# LEDPanel.net
KiCad netlist of a schematic drawn in EAGLE
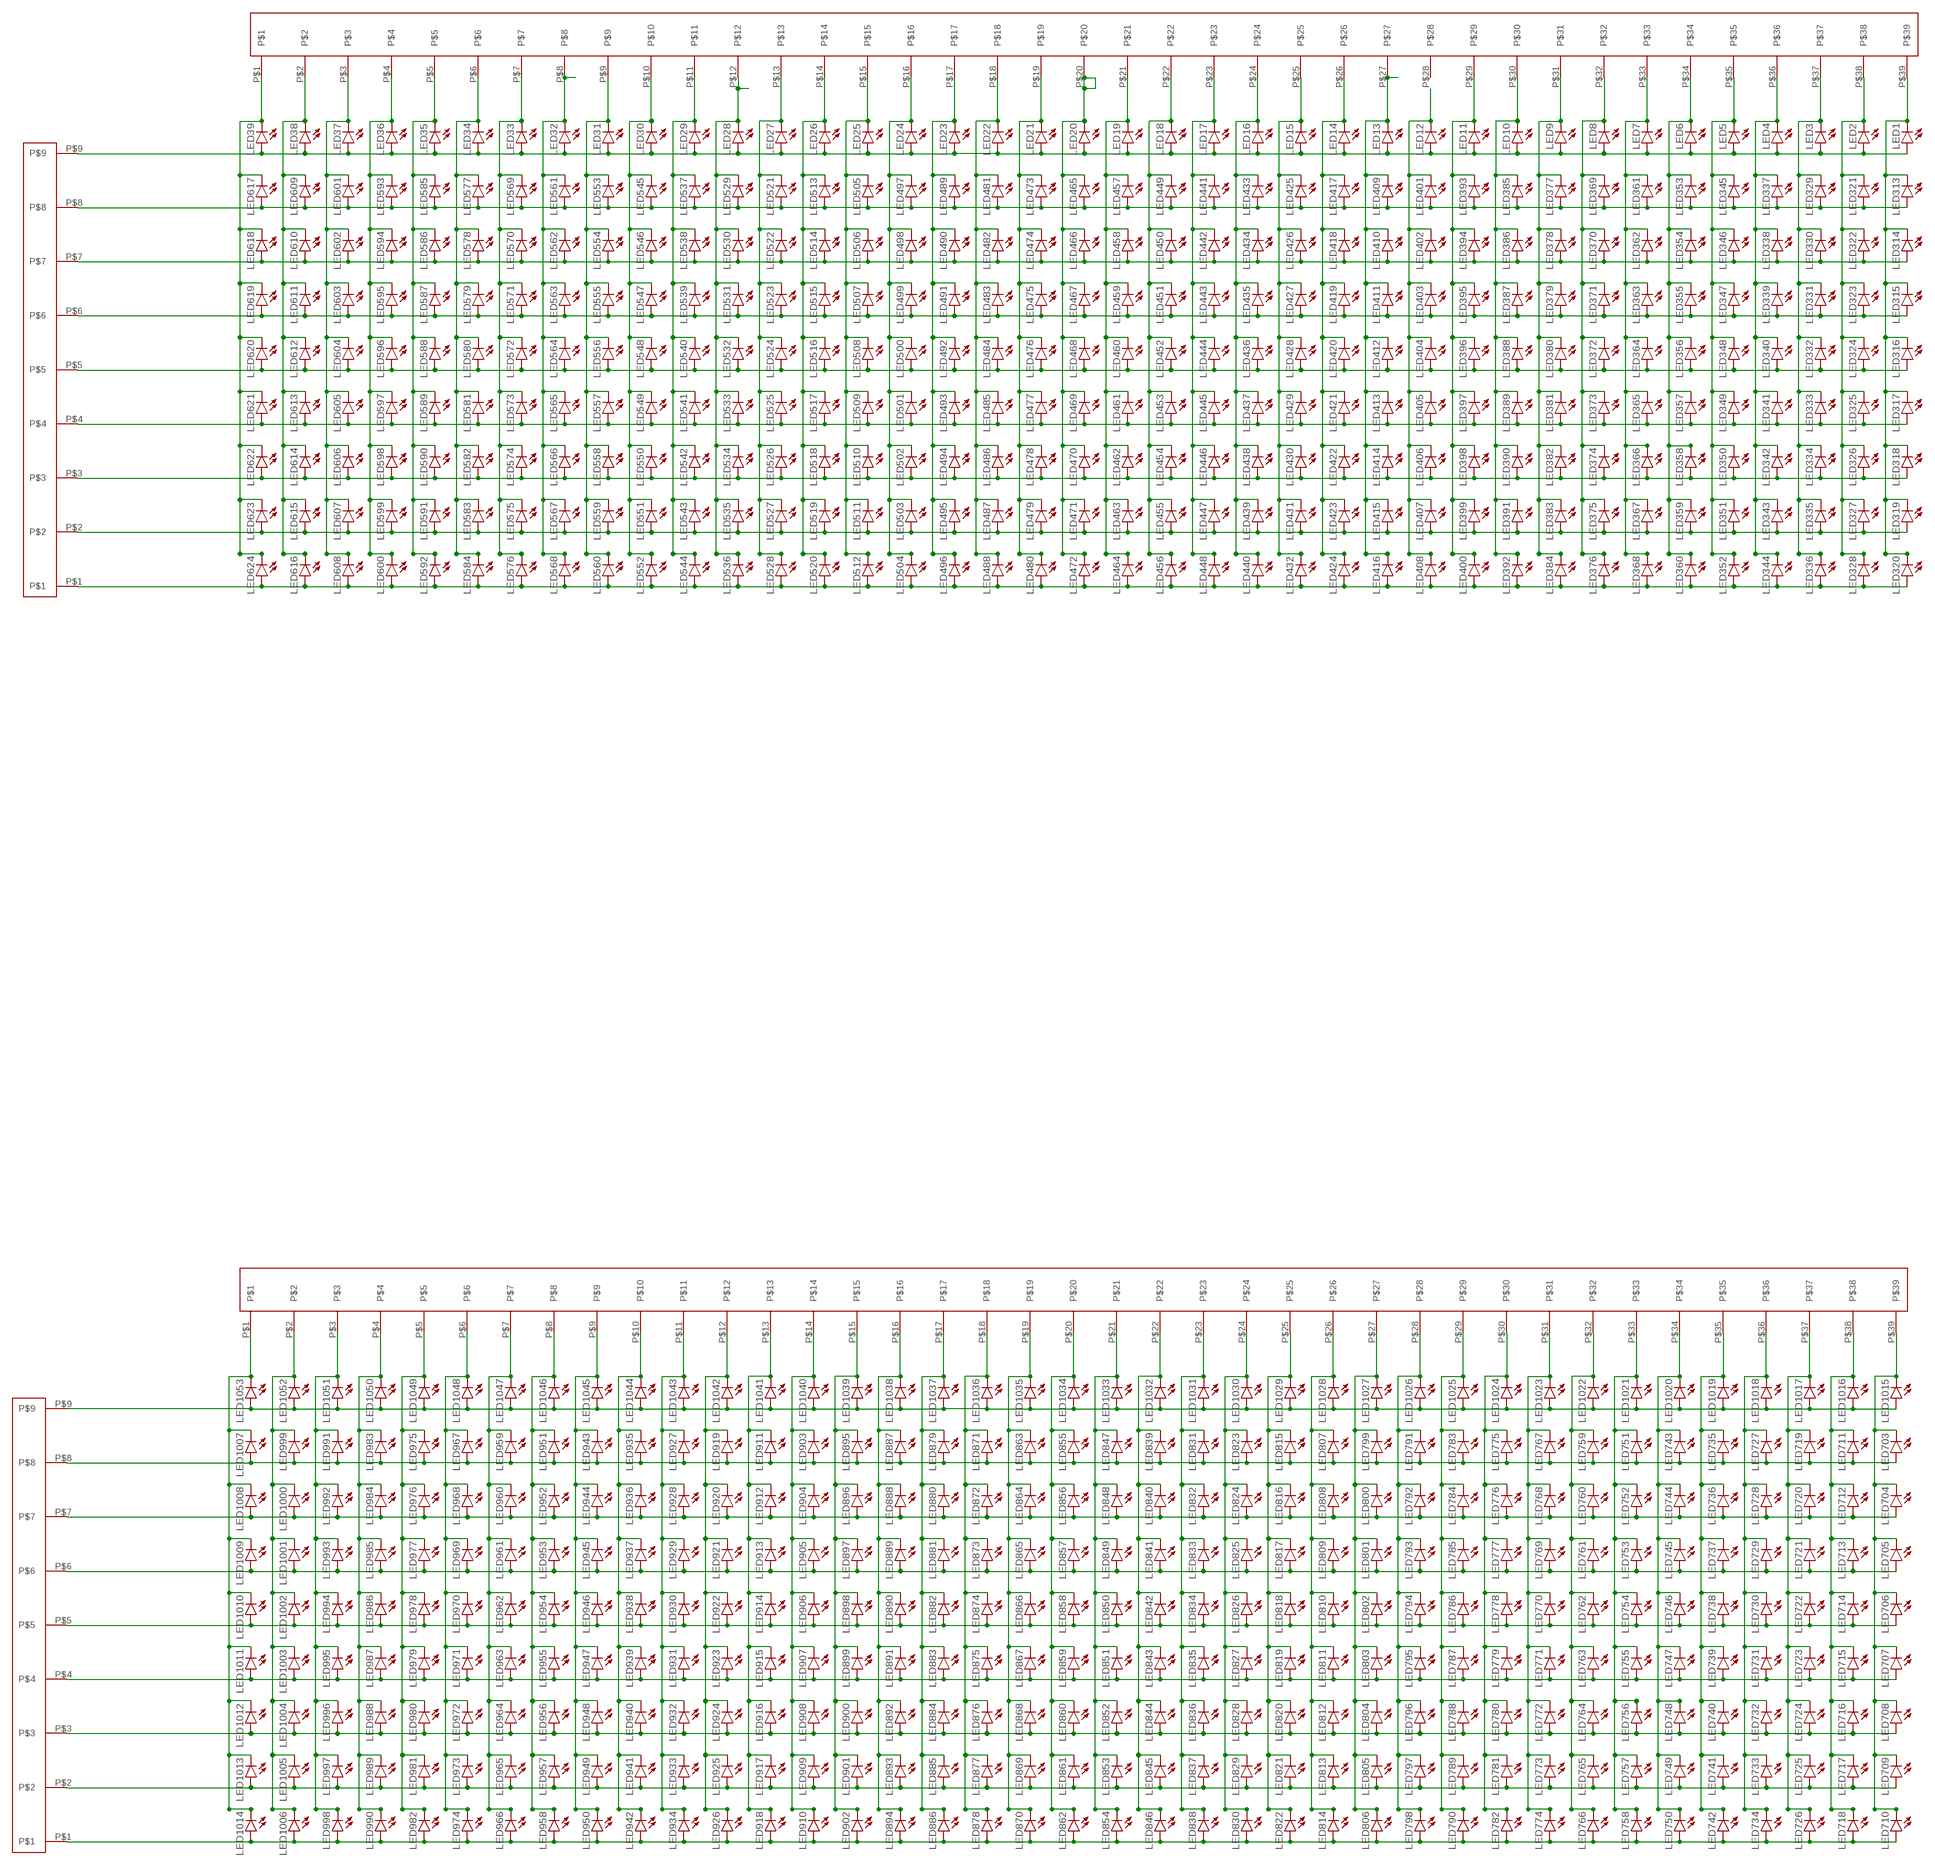
[diagram p0: schematic, sheet 1]

(export (version "E")
  (design (tool "Eeschema 10.0.6"))
  (components
    (comp (ref "LED1")
      (value "LED3MM")
      (footprint "eagle-import:LED_3MM")
      (libsource (lib "eagle-import") (part "LED3MM"))
    )
    (comp (ref "LED2")
      (value "LED3MM")
      (footprint "eagle-import:LED_3MM")
      (libsource (lib "eagle-import") (part "LED3MM"))
    )
    (comp (ref "LED3")
      (value "LED3MM")
      (footprint "eagle-import:LED_3MM")
      (libsource (lib "eagle-import") (part "LED3MM"))
    )
    (comp (ref "LED4")
      (value "LED3MM")
      (footprint "eagle-import:LED_3MM")
      (libsource (lib "eagle-import") (part "LED3MM"))
    )
    (comp (ref "LED5")
      (value "LED3MM")
      (footprint "eagle-import:LED_3MM")
      (libsource (lib "eagle-import") (part "LED3MM"))
    )
    (comp (ref "LED6")
      (value "LED3MM")
      (footprint "eagle-import:LED_3MM")
      (libsource (lib "eagle-import") (part "LED3MM"))
    )
    (comp (ref "LED7")
      (value "LED3MM")
      (footprint "eagle-import:LED_3MM")
      (libsource (lib "eagle-import") (part "LED3MM"))
    )
    (comp (ref "LED8")
      (value "LED3MM")
      (footprint "eagle-import:LED_3MM")
      (libsource (lib "eagle-import") (part "LED3MM"))
    )
    (comp (ref "LED9")
      (value "LED3MM")
      (footprint "eagle-import:LED_3MM")
      (libsource (lib "eagle-import") (part "LED3MM"))
    )
    (comp (ref "LED10")
      (value "LED3MM")
      (footprint "eagle-import:LED_3MM")
      (libsource (lib "eagle-import") (part "LED3MM"))
    )
    (comp (ref "LED11")
      (value "LED3MM")
      (footprint "eagle-import:LED_3MM")
      (libsource (lib "eagle-import") (part "LED3MM"))
    )
    (comp (ref "LED12")
      (value "LED3MM")
      (footprint "eagle-import:LED_3MM")
      (libsource (lib "eagle-import") (part "LED3MM"))
    )
    (comp (ref "LED13")
      (value "LED3MM")
      (footprint "eagle-import:LED_3MM")
      (libsource (lib "eagle-import") (part "LED3MM"))
    )
    (comp (ref "LED14")
      (value "LED3MM")
      (footprint "eagle-import:LED_3MM")
      (libsource (lib "eagle-import") (part "LED3MM"))
    )
    (comp (ref "LED15")
      (value "LED3MM")
      (footprint "eagle-import:LED_3MM")
      (libsource (lib "eagle-import") (part "LED3MM"))
    )
    (comp (ref "LED16")
      (value "LED3MM")
      (footprint "eagle-import:LED_3MM")
      (libsource (lib "eagle-import") (part "LED3MM"))
    )
    (comp (ref "LED17")
      (value "LED3MM")
      (footprint "eagle-import:LED_3MM")
      (libsource (lib "eagle-import") (part "LED3MM"))
    )
    (comp (ref "LED18")
      (value "LED3MM")
      (footprint "eagle-import:LED_3MM")
      (libsource (lib "eagle-import") (part "LED3MM"))
    )
    (comp (ref "LED19")
      (value "LED3MM")
      (footprint "eagle-import:LED_3MM")
      (libsource (lib "eagle-import") (part "LED3MM"))
    )
    (comp (ref "LED20")
      (value "LED3MM")
      (footprint "eagle-import:LED_3MM")
      (libsource (lib "eagle-import") (part "LED3MM"))
    )
    (comp (ref "LED21")
      (value "LED3MM")
      (footprint "eagle-import:LED_3MM")
      (libsource (lib "eagle-import") (part "LED3MM"))
    )
    (comp (ref "LED22")
      (value "LED3MM")
      (footprint "eagle-import:LED_3MM")
      (libsource (lib "eagle-import") (part "LED3MM"))
    )
    (comp (ref "LED23")
      (value "LED3MM")
      (footprint "eagle-import:LED_3MM")
      (libsource (lib "eagle-import") (part "LED3MM"))
    )
    (comp (ref "LED24")
      (value "LED3MM")
      (footprint "eagle-import:LED_3MM")
      (libsource (lib "eagle-import") (part "LED3MM"))
    )
    (comp (ref "LED25")
      (value "LED3MM")
      (footprint "eagle-import:LED_3MM")
      (libsource (lib "eagle-import") (part "LED3MM"))
    )
    (comp (ref "LED26")
      (value "LED3MM")
      (footprint "eagle-import:LED_3MM")
      (libsource (lib "eagle-import") (part "LED3MM"))
    )
    (comp (ref "LED27")
      (value "LED3MM")
      (footprint "eagle-import:LED_3MM")
      (libsource (lib "eagle-import") (part "LED3MM"))
    )
    (comp (ref "LED28")
      (value "LED3MM")
      (footprint "eagle-import:LED_3MM")
      (libsource (lib "eagle-import") (part "LED3MM"))
    )
    (comp (ref "LED29")
      (value "LED3MM")
      (footprint "eagle-import:LED_3MM")
      (libsource (lib "eagle-import") (part "LED3MM"))
    )
    (comp (ref "LED30")
      (value "LED3MM")
      (footprint "eagle-import:LED_3MM")
      (libsource (lib "eagle-import") (part "LED3MM"))
    )
    (comp (ref "LED31")
      (value "LED3MM")
      (footprint "eagle-import:LED_3MM")
      (libsource (lib "eagle-import") (part "LED3MM"))
    )
    (comp (ref "LED32")
      (value "LED3MM")
      (footprint "eagle-import:LED_3MM")
      (libsource (lib "eagle-import") (part "LED3MM"))
    )
    (comp (ref "LED33")
      (value "LED3MM")
      (footprint "eagle-import:LED_3MM")
      (libsource (lib "eagle-import") (part "LED3MM"))
    )
    (comp (ref "LED34")
      (value "LED3MM")
      (footprint "eagle-import:LED_3MM")
      (libsource (lib "eagle-import") (part "LED3MM"))
    )
    (comp (ref "LED35")
      (value "LED3MM")
      (footprint "eagle-import:LED_3MM")
      (libsource (lib "eagle-import") (part "LED3MM"))
    )
    (comp (ref "LED36")
      (value "LED3MM")
      (footprint "eagle-import:LED_3MM")
      (libsource (lib "eagle-import") (part "LED3MM"))
    )
    (comp (ref "LED37")
      (value "LED3MM")
      (footprint "eagle-import:LED_3MM")
      (libsource (lib "eagle-import") (part "LED3MM"))
    )
    (comp (ref "LED38")
      (value "LED3MM")
      (footprint "eagle-import:LED_3MM")
      (libsource (lib "eagle-import") (part "LED3MM"))
    )
    (comp (ref "LED39")
      (value "LED3MM")
      (footprint "eagle-import:LED_3MM")
      (libsource (lib "eagle-import") (part "LED3MM"))
    )
    (comp (ref "LED313")
      (value "LED3MM")
      (footprint "eagle-import:LED_3MM")
      (libsource (lib "eagle-import") (part "LED3MM"))
    )
    (comp (ref "LED314")
      (value "LED3MM")
      (footprint "eagle-import:LED_3MM")
      (libsource (lib "eagle-import") (part "LED3MM"))
    )
    (comp (ref "LED315")
      (value "LED3MM")
      (footprint "eagle-import:LED_3MM")
      (libsource (lib "eagle-import") (part "LED3MM"))
    )
    (comp (ref "LED316")
      (value "LED3MM")
      (footprint "eagle-import:LED_3MM")
      (libsource (lib "eagle-import") (part "LED3MM"))
    )
    (comp (ref "LED317")
      (value "LED3MM")
      (footprint "eagle-import:LED_3MM")
      (libsource (lib "eagle-import") (part "LED3MM"))
    )
    (comp (ref "LED318")
      (value "LED3MM")
      (footprint "eagle-import:LED_3MM")
      (libsource (lib "eagle-import") (part "LED3MM"))
    )
    (comp (ref "LED319")
      (value "LED3MM")
      (footprint "eagle-import:LED_3MM")
      (libsource (lib "eagle-import") (part "LED3MM"))
    )
    (comp (ref "LED320")
      (value "LED3MM")
      (footprint "eagle-import:LED_3MM")
      (libsource (lib "eagle-import") (part "LED3MM"))
    )
    (comp (ref "LED321")
      (value "LED3MM")
      (footprint "eagle-import:LED_3MM")
      (libsource (lib "eagle-import") (part "LED3MM"))
    )
    (comp (ref "LED322")
      (value "LED3MM")
      (footprint "eagle-import:LED_3MM")
      (libsource (lib "eagle-import") (part "LED3MM"))
    )
    (comp (ref "LED323")
      (value "LED3MM")
      (footprint "eagle-import:LED_3MM")
      (libsource (lib "eagle-import") (part "LED3MM"))
    )
    (comp (ref "LED324")
      (value "LED3MM")
      (footprint "eagle-import:LED_3MM")
      (libsource (lib "eagle-import") (part "LED3MM"))
    )
    (comp (ref "LED325")
      (value "LED3MM")
      (footprint "eagle-import:LED_3MM")
      (libsource (lib "eagle-import") (part "LED3MM"))
    )
    (comp (ref "LED326")
      (value "LED3MM")
      (footprint "eagle-import:LED_3MM")
      (libsource (lib "eagle-import") (part "LED3MM"))
    )
    (comp (ref "LED327")
      (value "LED3MM")
      (footprint "eagle-import:LED_3MM")
      (libsource (lib "eagle-import") (part "LED3MM"))
    )
    (comp (ref "LED328")
      (value "LED3MM")
      (footprint "eagle-import:LED_3MM")
      (libsource (lib "eagle-import") (part "LED3MM"))
    )
    (comp (ref "LED329")
      (value "LED3MM")
      (footprint "eagle-import:LED_3MM")
      (libsource (lib "eagle-import") (part "LED3MM"))
    )
    (comp (ref "LED330")
      (value "LED3MM")
      (footprint "eagle-import:LED_3MM")
      (libsource (lib "eagle-import") (part "LED3MM"))
    )
    (comp (ref "LED331")
      (value "LED3MM")
      (footprint "eagle-import:LED_3MM")
      (libsource (lib "eagle-import") (part "LED3MM"))
    )
    (comp (ref "LED332")
      (value "LED3MM")
      (footprint "eagle-import:LED_3MM")
      (libsource (lib "eagle-import") (part "LED3MM"))
    )
    (comp (ref "LED333")
      (value "LED3MM")
      (footprint "eagle-import:LED_3MM")
      (libsource (lib "eagle-import") (part "LED3MM"))
    )
    (comp (ref "LED334")
      (value "LED3MM")
      (footprint "eagle-import:LED_3MM")
      (libsource (lib "eagle-import") (part "LED3MM"))
    )
    (comp (ref "LED335")
      (value "LED3MM")
      (footprint "eagle-import:LED_3MM")
      (libsource (lib "eagle-import") (part "LED3MM"))
    )
    (comp (ref "LED336")
      (value "LED3MM")
      (footprint "eagle-import:LED_3MM")
      (libsource (lib "eagle-import") (part "LED3MM"))
    )
    (comp (ref "LED337")
      (value "LED3MM")
      (footprint "eagle-import:LED_3MM")
      (libsource (lib "eagle-import") (part "LED3MM"))
    )
    (comp (ref "LED338")
      (value "LED3MM")
      (footprint "eagle-import:LED_3MM")
      (libsource (lib "eagle-import") (part "LED3MM"))
    )
    (comp (ref "LED339")
      (value "LED3MM")
      (footprint "eagle-import:LED_3MM")
      (libsource (lib "eagle-import") (part "LED3MM"))
    )
    (comp (ref "LED340")
      (value "LED3MM")
      (footprint "eagle-import:LED_3MM")
      (libsource (lib "eagle-import") (part "LED3MM"))
    )
    (comp (ref "LED341")
      (value "LED3MM")
      (footprint "eagle-import:LED_3MM")
      (libsource (lib "eagle-import") (part "LED3MM"))
    )
    (comp (ref "LED342")
      (value "LED3MM")
      (footprint "eagle-import:LED_3MM")
      (libsource (lib "eagle-import") (part "LED3MM"))
    )
    (comp (ref "LED343")
      (value "LED3MM")
      (footprint "eagle-import:LED_3MM")
      (libsource (lib "eagle-import") (part "LED3MM"))
    )
    (comp (ref "LED344")
      (value "LED3MM")
      (footprint "eagle-import:LED_3MM")
      (libsource (lib "eagle-import") (part "LED3MM"))
    )
    (comp (ref "LED345")
      (value "LED3MM")
      (footprint "eagle-import:LED_3MM")
      (libsource (lib "eagle-import") (part "LED3MM"))
    )
    (comp (ref "LED346")
      (value "LED3MM")
      (footprint "eagle-import:LED_3MM")
      (libsource (lib "eagle-import") (part "LED3MM"))
    )
    (comp (ref "LED347")
      (value "LED3MM")
      (footprint "eagle-import:LED_3MM")
      (libsource (lib "eagle-import") (part "LED3MM"))
    )
    (comp (ref "LED348")
      (value "LED3MM")
      (footprint "eagle-import:LED_3MM")
      (libsource (lib "eagle-import") (part "LED3MM"))
    )
    (comp (ref "LED349")
      (value "LED3MM")
      (footprint "eagle-import:LED_3MM")
      (libsource (lib "eagle-import") (part "LED3MM"))
    )
    (comp (ref "LED350")
      (value "LED3MM")
      (footprint "eagle-import:LED_3MM")
      (libsource (lib "eagle-import") (part "LED3MM"))
    )
    (comp (ref "LED351")
      (value "LED3MM")
      (footprint "eagle-import:LED_3MM")
      (libsource (lib "eagle-import") (part "LED3MM"))
    )
    (comp (ref "LED352")
      (value "LED3MM")
      (footprint "eagle-import:LED_3MM")
      (libsource (lib "eagle-import") (part "LED3MM"))
    )
    (comp (ref "LED353")
      (value "LED3MM")
      (footprint "eagle-import:LED_3MM")
      (libsource (lib "eagle-import") (part "LED3MM"))
    )
    (comp (ref "LED354")
      (value "LED3MM")
      (footprint "eagle-import:LED_3MM")
      (libsource (lib "eagle-import") (part "LED3MM"))
    )
    (comp (ref "LED355")
      (value "LED3MM")
      (footprint "eagle-import:LED_3MM")
      (libsource (lib "eagle-import") (part "LED3MM"))
    )
    (comp (ref "LED356")
      (value "LED3MM")
      (footprint "eagle-import:LED_3MM")
      (libsource (lib "eagle-import") (part "LED3MM"))
    )
    (comp (ref "LED357")
      (value "LED3MM")
      (footprint "eagle-import:LED_3MM")
      (libsource (lib "eagle-import") (part "LED3MM"))
    )
    (comp (ref "LED358")
      (value "LED3MM")
      (footprint "eagle-import:LED_3MM")
      (libsource (lib "eagle-import") (part "LED3MM"))
    )
    (comp (ref "LED359")
      (value "LED3MM")
      (footprint "eagle-import:LED_3MM")
      (libsource (lib "eagle-import") (part "LED3MM"))
    )
    (comp (ref "LED360")
      (value "LED3MM")
      (footprint "eagle-import:LED_3MM")
      (libsource (lib "eagle-import") (part "LED3MM"))
    )
    (comp (ref "LED361")
      (value "LED3MM")
      (footprint "eagle-import:LED_3MM")
      (libsource (lib "eagle-import") (part "LED3MM"))
    )
    (comp (ref "LED362")
      (value "LED3MM")
      (footprint "eagle-import:LED_3MM")
      (libsource (lib "eagle-import") (part "LED3MM"))
    )
    (comp (ref "LED363")
      (value "LED3MM")
      (footprint "eagle-import:LED_3MM")
      (libsource (lib "eagle-import") (part "LED3MM"))
    )
    (comp (ref "LED364")
      (value "LED3MM")
      (footprint "eagle-import:LED_3MM")
      (libsource (lib "eagle-import") (part "LED3MM"))
    )
    (comp (ref "LED365")
      (value "LED3MM")
      (footprint "eagle-import:LED_3MM")
      (libsource (lib "eagle-import") (part "LED3MM"))
    )
    (comp (ref "LED366")
      (value "LED3MM")
      (footprint "eagle-import:LED_3MM")
      (libsource (lib "eagle-import") (part "LED3MM"))
    )
    (comp (ref "LED367")
      (value "LED3MM")
      (footprint "eagle-import:LED_3MM")
      (libsource (lib "eagle-import") (part "LED3MM"))
    )
    (comp (ref "LED368")
      (value "LED3MM")
      (footprint "eagle-import:LED_3MM")
      (libsource (lib "eagle-import") (part "LED3MM"))
    )
    (comp (ref "LED369")
      (value "LED3MM")
      (footprint "eagle-import:LED_3MM")
      (libsource (lib "eagle-import") (part "LED3MM"))
    )
    (comp (ref "LED370")
      (value "LED3MM")
      (footprint "eagle-import:LED_3MM")
      (libsource (lib "eagle-import") (part "LED3MM"))
    )
    (comp (ref "LED371")
      (value "LED3MM")
      (footprint "eagle-import:LED_3MM")
      (libsource (lib "eagle-import") (part "LED3MM"))
    )
    (comp (ref "LED372")
      (value "LED3MM")
      (footprint "eagle-import:LED_3MM")
      (libsource (lib "eagle-import") (part "LED3MM"))
    )
    (comp (ref "LED373")
      (value "LED3MM")
      (footprint "eagle-import:LED_3MM")
      (libsource (lib "eagle-import") (part "LED3MM"))
    )
    (comp (ref "LED374")
      (value "LED3MM")
      (footprint "eagle-import:LED_3MM")
      (libsource (lib "eagle-import") (part "LED3MM"))
    )
    (comp (ref "LED375")
      (value "LED3MM")
      (footprint "eagle-import:LED_3MM")
      (libsource (lib "eagle-import") (part "LED3MM"))
    )
    (comp (ref "LED376")
      (value "LED3MM")
      (footprint "eagle-import:LED_3MM")
      (libsource (lib "eagle-import") (part "LED3MM"))
    )
    (comp (ref "LED377")
      (value "LED3MM")
      (footprint "eagle-import:LED_3MM")
      (libsource (lib "eagle-import") (part "LED3MM"))
    )
    (comp (ref "LED378")
      (value "LED3MM")
      (footprint "eagle-import:LED_3MM")
      (libsource (lib "eagle-import") (part "LED3MM"))
    )
    (comp (ref "LED379")
      (value "LED3MM")
      (footprint "eagle-import:LED_3MM")
      (libsource (lib "eagle-import") (part "LED3MM"))
    )
    (comp (ref "LED380")
      (value "LED3MM")
      (footprint "eagle-import:LED_3MM")
      (libsource (lib "eagle-import") (part "LED3MM"))
    )
    (comp (ref "LED381")
      (value "LED3MM")
      (footprint "eagle-import:LED_3MM")
      (libsource (lib "eagle-import") (part "LED3MM"))
    )
    (comp (ref "LED382")
      (value "LED3MM")
      (footprint "eagle-import:LED_3MM")
      (libsource (lib "eagle-import") (part "LED3MM"))
    )
    (comp (ref "LED383")
      (value "LED3MM")
      (footprint "eagle-import:LED_3MM")
      (libsource (lib "eagle-import") (part "LED3MM"))
    )
    (comp (ref "LED384")
      (value "LED3MM")
      (footprint "eagle-import:LED_3MM")
      (libsource (lib "eagle-import") (part "LED3MM"))
    )
    (comp (ref "LED385")
      (value "LED3MM")
      (footprint "eagle-import:LED_3MM")
      (libsource (lib "eagle-import") (part "LED3MM"))
    )
    (comp (ref "LED386")
      (value "LED3MM")
      (footprint "eagle-import:LED_3MM")
      (libsource (lib "eagle-import") (part "LED3MM"))
    )
    (comp (ref "LED387")
      (value "LED3MM")
      (footprint "eagle-import:LED_3MM")
      (libsource (lib "eagle-import") (part "LED3MM"))
    )
    (comp (ref "LED388")
      (value "LED3MM")
      (footprint "eagle-import:LED_3MM")
      (libsource (lib "eagle-import") (part "LED3MM"))
    )
    (comp (ref "LED389")
      (value "LED3MM")
      (footprint "eagle-import:LED_3MM")
      (libsource (lib "eagle-import") (part "LED3MM"))
    )
    (comp (ref "LED390")
      (value "LED3MM")
      (footprint "eagle-import:LED_3MM")
      (libsource (lib "eagle-import") (part "LED3MM"))
    )
    (comp (ref "LED391")
      (value "LED3MM")
      (footprint "eagle-import:LED_3MM")
      (libsource (lib "eagle-import") (part "LED3MM"))
    )
    (comp (ref "LED392")
      (value "LED3MM")
      (footprint "eagle-import:LED_3MM")
      (libsource (lib "eagle-import") (part "LED3MM"))
    )
    (comp (ref "LED393")
      (value "LED3MM")
      (footprint "eagle-import:LED_3MM")
      (libsource (lib "eagle-import") (part "LED3MM"))
    )
    (comp (ref "LED394")
      (value "LED3MM")
      (footprint "eagle-import:LED_3MM")
      (libsource (lib "eagle-import") (part "LED3MM"))
    )
    (comp (ref "LED395")
      (value "LED3MM")
      (footprint "eagle-import:LED_3MM")
      (libsource (lib "eagle-import") (part "LED3MM"))
    )
    (comp (ref "LED396")
      (value "LED3MM")
      (footprint "eagle-import:LED_3MM")
      (libsource (lib "eagle-import") (part "LED3MM"))
    )
    (comp (ref "LED397")
      (value "LED3MM")
      (footprint "eagle-import:LED_3MM")
      (libsource (lib "eagle-import") (part "LED3MM"))
    )
    (comp (ref "LED398")
      (value "LED3MM")
      (footprint "eagle-import:LED_3MM")
      (libsource (lib "eagle-import") (part "LED3MM"))
    )
    (comp (ref "LED399")
      (value "LED3MM")
      (footprint "eagle-import:LED_3MM")
      (libsource (lib "eagle-import") (part "LED3MM"))
    )
    (comp (ref "LED400")
      (value "LED3MM")
      (footprint "eagle-import:LED_3MM")
      (libsource (lib "eagle-import") (part "LED3MM"))
    )
    (comp (ref "LED401")
      (value "LED3MM")
      (footprint "eagle-import:LED_3MM")
      (libsource (lib "eagle-import") (part "LED3MM"))
    )
    (comp (ref "LED402")
      (value "LED3MM")
      (footprint "eagle-import:LED_3MM")
      (libsource (lib "eagle-import") (part "LED3MM"))
    )
    (comp (ref "LED403")
      (value "LED3MM")
      (footprint "eagle-import:LED_3MM")
      (libsource (lib "eagle-import") (part "LED3MM"))
    )
    (comp (ref "LED404")
      (value "LED3MM")
      (footprint "eagle-import:LED_3MM")
      (libsource (lib "eagle-import") (part "LED3MM"))
    )
    (comp (ref "LED405")
      (value "LED3MM")
      (footprint "eagle-import:LED_3MM")
      (libsource (lib "eagle-import") (part "LED3MM"))
    )
    (comp (ref "LED406")
      (value "LED3MM")
      (footprint "eagle-import:LED_3MM")
      (libsource (lib "eagle-import") (part "LED3MM"))
    )
    (comp (ref "LED407")
      (value "LED3MM")
      (footprint "eagle-import:LED_3MM")
      (libsource (lib "eagle-import") (part "LED3MM"))
    )
    (comp (ref "LED408")
      (value "LED3MM")
      (footprint "eagle-import:LED_3MM")
      (libsource (lib "eagle-import") (part "LED3MM"))
    )
    (comp (ref "LED409")
      (value "LED3MM")
      (footprint "eagle-import:LED_3MM")
      (libsource (lib "eagle-import") (part "LED3MM"))
    )
    (comp (ref "LED410")
      (value "LED3MM")
      (footprint "eagle-import:LED_3MM")
      (libsource (lib "eagle-import") (part "LED3MM"))
    )
    (comp (ref "LED411")
      (value "LED3MM")
      (footprint "eagle-import:LED_3MM")
      (libsource (lib "eagle-import") (part "LED3MM"))
    )
    (comp (ref "LED412")
      (value "LED3MM")
      (footprint "eagle-import:LED_3MM")
      (libsource (lib "eagle-import") (part "LED3MM"))
    )
    (comp (ref "LED413")
      (value "LED3MM")
      (footprint "eagle-import:LED_3MM")
      (libsource (lib "eagle-import") (part "LED3MM"))
    )
    (comp (ref "LED414")
      (value "LED3MM")
      (footprint "eagle-import:LED_3MM")
      (libsource (lib "eagle-import") (part "LED3MM"))
    )
    (comp (ref "LED415")
      (value "LED3MM")
      (footprint "eagle-import:LED_3MM")
      (libsource (lib "eagle-import") (part "LED3MM"))
    )
    (comp (ref "LED416")
      (value "LED3MM")
      (footprint "eagle-import:LED_3MM")
      (libsource (lib "eagle-import") (part "LED3MM"))
    )
    (comp (ref "LED417")
      (value "LED3MM")
      (footprint "eagle-import:LED_3MM")
      (libsource (lib "eagle-import") (part "LED3MM"))
    )
    (comp (ref "LED418")
      (value "LED3MM")
      (footprint "eagle-import:LED_3MM")
      (libsource (lib "eagle-import") (part "LED3MM"))
    )
    (comp (ref "LED419")
      (value "LED3MM")
      (footprint "eagle-import:LED_3MM")
      (libsource (lib "eagle-import") (part "LED3MM"))
    )
    (comp (ref "LED420")
      (value "LED3MM")
      (footprint "eagle-import:LED_3MM")
      (libsource (lib "eagle-import") (part "LED3MM"))
    )
    (comp (ref "LED421")
      (value "LED3MM")
      (footprint "eagle-import:LED_3MM")
      (libsource (lib "eagle-import") (part "LED3MM"))
    )
    (comp (ref "LED422")
      (value "LED3MM")
      (footprint "eagle-import:LED_3MM")
      (libsource (lib "eagle-import") (part "LED3MM"))
    )
    (comp (ref "LED423")
      (value "LED3MM")
      (footprint "eagle-import:LED_3MM")
      (libsource (lib "eagle-import") (part "LED3MM"))
    )
    (comp (ref "LED424")
      (value "LED3MM")
      (footprint "eagle-import:LED_3MM")
      (libsource (lib "eagle-import") (part "LED3MM"))
    )
    (comp (ref "LED425")
      (value "LED3MM")
      (footprint "eagle-import:LED_3MM")
      (libsource (lib "eagle-import") (part "LED3MM"))
    )
    (comp (ref "LED426")
      (value "LED3MM")
      (footprint "eagle-import:LED_3MM")
      (libsource (lib "eagle-import") (part "LED3MM"))
    )
    (comp (ref "LED427")
      (value "LED3MM")
      (footprint "eagle-import:LED_3MM")
      (libsource (lib "eagle-import") (part "LED3MM"))
    )
    (comp (ref "LED428")
      (value "LED3MM")
      (footprint "eagle-import:LED_3MM")
      (libsource (lib "eagle-import") (part "LED3MM"))
    )
    (comp (ref "LED429")
      (value "LED3MM")
      (footprint "eagle-import:LED_3MM")
      (libsource (lib "eagle-import") (part "LED3MM"))
    )
    (comp (ref "LED430")
      (value "LED3MM")
      (footprint "eagle-import:LED_3MM")
      (libsource (lib "eagle-import") (part "LED3MM"))
    )
    (comp (ref "LED431")
      (value "LED3MM")
      (footprint "eagle-import:LED_3MM")
      (libsource (lib "eagle-import") (part "LED3MM"))
    )
    (comp (ref "LED432")
      (value "LED3MM")
      (footprint "eagle-import:LED_3MM")
      (libsource (lib "eagle-import") (part "LED3MM"))
    )
    (comp (ref "LED433")
      (value "LED3MM")
      (footprint "eagle-import:LED_3MM")
      (libsource (lib "eagle-import") (part "LED3MM"))
    )
    (comp (ref "LED434")
      (value "LED3MM")
      (footprint "eagle-import:LED_3MM")
      (libsource (lib "eagle-import") (part "LED3MM"))
    )
    (comp (ref "LED435")
      (value "LED3MM")
      (footprint "eagle-import:LED_3MM")
      (libsource (lib "eagle-import") (part "LED3MM"))
    )
    (comp (ref "LED436")
      (value "LED3MM")
      (footprint "eagle-import:LED_3MM")
      (libsource (lib "eagle-import") (part "LED3MM"))
    )
    (comp (ref "LED437")
      (value "LED3MM")
      (footprint "eagle-import:LED_3MM")
      (libsource (lib "eagle-import") (part "LED3MM"))
    )
    (comp (ref "LED438")
      (value "LED3MM")
      (footprint "eagle-import:LED_3MM")
      (libsource (lib "eagle-import") (part "LED3MM"))
    )
    (comp (ref "LED439")
      (value "LED3MM")
      (footprint "eagle-import:LED_3MM")
      (libsource (lib "eagle-import") (part "LED3MM"))
    )
    (comp (ref "LED440")
      (value "LED3MM")
      (footprint "eagle-import:LED_3MM")
      (libsource (lib "eagle-import") (part "LED3MM"))
    )
    (comp (ref "LED441")
      (value "LED3MM")
      (footprint "eagle-import:LED_3MM")
      (libsource (lib "eagle-import") (part "LED3MM"))
    )
    (comp (ref "LED442")
      (value "LED3MM")
      (footprint "eagle-import:LED_3MM")
      (libsource (lib "eagle-import") (part "LED3MM"))
    )
    (comp (ref "LED443")
      (value "LED3MM")
      (footprint "eagle-import:LED_3MM")
      (libsource (lib "eagle-import") (part "LED3MM"))
    )
    (comp (ref "LED444")
      (value "LED3MM")
      (footprint "eagle-import:LED_3MM")
      (libsource (lib "eagle-import") (part "LED3MM"))
    )
    (comp (ref "LED445")
      (value "LED3MM")
      (footprint "eagle-import:LED_3MM")
      (libsource (lib "eagle-import") (part "LED3MM"))
    )
    (comp (ref "LED446")
      (value "LED3MM")
      (footprint "eagle-import:LED_3MM")
      (libsource (lib "eagle-import") (part "LED3MM"))
    )
    (comp (ref "LED447")
      (value "LED3MM")
      (footprint "eagle-import:LED_3MM")
      (libsource (lib "eagle-import") (part "LED3MM"))
    )
    (comp (ref "LED448")
      (value "LED3MM")
      (footprint "eagle-import:LED_3MM")
      (libsource (lib "eagle-import") (part "LED3MM"))
    )
    (comp (ref "LED449")
      (value "LED3MM")
      (footprint "eagle-import:LED_3MM")
      (libsource (lib "eagle-import") (part "LED3MM"))
    )
    (comp (ref "LED450")
      (value "LED3MM")
      (footprint "eagle-import:LED_3MM")
      (libsource (lib "eagle-import") (part "LED3MM"))
    )
    (comp (ref "LED451")
      (value "LED3MM")
      (footprint "eagle-import:LED_3MM")
      (libsource (lib "eagle-import") (part "LED3MM"))
    )
    (comp (ref "LED452")
      (value "LED3MM")
      (footprint "eagle-import:LED_3MM")
      (libsource (lib "eagle-import") (part "LED3MM"))
    )
    (comp (ref "LED453")
      (value "LED3MM")
      (footprint "eagle-import:LED_3MM")
      (libsource (lib "eagle-import") (part "LED3MM"))
    )
    (comp (ref "LED454")
      (value "LED3MM")
      (footprint "eagle-import:LED_3MM")
      (libsource (lib "eagle-import") (part "LED3MM"))
    )
    (comp (ref "LED455")
      (value "LED3MM")
      (footprint "eagle-import:LED_3MM")
      (libsource (lib "eagle-import") (part "LED3MM"))
    )
    (comp (ref "LED456")
      (value "LED3MM")
      (footprint "eagle-import:LED_3MM")
      (libsource (lib "eagle-import") (part "LED3MM"))
    )
    (comp (ref "LED457")
      (value "LED3MM")
      (footprint "eagle-import:LED_3MM")
      (libsource (lib "eagle-import") (part "LED3MM"))
    )
    (comp (ref "LED458")
      (value "LED3MM")
      (footprint "eagle-import:LED_3MM")
      (libsource (lib "eagle-import") (part "LED3MM"))
    )
    (comp (ref "LED459")
      (value "LED3MM")
      (footprint "eagle-import:LED_3MM")
      (libsource (lib "eagle-import") (part "LED3MM"))
    )
    (comp (ref "LED460")
      (value "LED3MM")
      (footprint "eagle-import:LED_3MM")
      (libsource (lib "eagle-import") (part "LED3MM"))
    )
    (comp (ref "LED461")
      (value "LED3MM")
      (footprint "eagle-import:LED_3MM")
      (libsource (lib "eagle-import") (part "LED3MM"))
    )
    (comp (ref "LED462")
      (value "LED3MM")
      (footprint "eagle-import:LED_3MM")
      (libsource (lib "eagle-import") (part "LED3MM"))
    )
    (comp (ref "LED463")
      (value "LED3MM")
      (footprint "eagle-import:LED_3MM")
      (libsource (lib "eagle-import") (part "LED3MM"))
    )
    (comp (ref "LED464")
      (value "LED3MM")
      (footprint "eagle-import:LED_3MM")
      (libsource (lib "eagle-import") (part "LED3MM"))
    )
    (comp (ref "LED465")
      (value "LED3MM")
      (footprint "eagle-import:LED_3MM")
      (libsource (lib "eagle-import") (part "LED3MM"))
    )
    (comp (ref "LED466")
      (value "LED3MM")
      (footprint "eagle-import:LED_3MM")
      (libsource (lib "eagle-import") (part "LED3MM"))
    )
    (comp (ref "LED467")
      (value "LED3MM")
      (footprint "eagle-import:LED_3MM")
      (libsource (lib "eagle-import") (part "LED3MM"))
    )
    (comp (ref "LED468")
      (value "LED3MM")
      (footprint "eagle-import:LED_3MM")
      (libsource (lib "eagle-import") (part "LED3MM"))
    )
    (comp (ref "LED469")
      (value "LED3MM")
      (footprint "eagle-import:LED_3MM")
      (libsource (lib "eagle-import") (part "LED3MM"))
    )
    (comp (ref "LED470")
      (value "LED3MM")
      (footprint "eagle-import:LED_3MM")
      (libsource (lib "eagle-import") (part "LED3MM"))
    )
    (comp (ref "LED471")
      (value "LED3MM")
      (footprint "eagle-import:LED_3MM")
      (libsource (lib "eagle-import") (part "LED3MM"))
    )
    (comp (ref "LED472")
      (value "LED3MM")
      (footprint "eagle-import:LED_3MM")
      (libsource (lib "eagle-import") (part "LED3MM"))
    )
    (comp (ref "LED473")
      (value "LED3MM")
      (footprint "eagle-import:LED_3MM")
      (libsource (lib "eagle-import") (part "LED3MM"))
    )
    (comp (ref "LED474")
      (value "LED3MM")
      (footprint "eagle-import:LED_3MM")
      (libsource (lib "eagle-import") (part "LED3MM"))
    )
    (comp (ref "LED475")
      (value "LED3MM")
      (footprint "eagle-import:LED_3MM")
      (libsource (lib "eagle-import") (part "LED3MM"))
    )
    (comp (ref "LED476")
      (value "LED3MM")
      (footprint "eagle-import:LED_3MM")
      (libsource (lib "eagle-import") (part "LED3MM"))
    )
    (comp (ref "LED477")
      (value "LED3MM")
      (footprint "eagle-import:LED_3MM")
      (libsource (lib "eagle-import") (part "LED3MM"))
    )
    (comp (ref "LED478")
      (value "LED3MM")
      (footprint "eagle-import:LED_3MM")
      (libsource (lib "eagle-import") (part "LED3MM"))
    )
    (comp (ref "LED479")
      (value "LED3MM")
      (footprint "eagle-import:LED_3MM")
      (libsource (lib "eagle-import") (part "LED3MM"))
    )
    (comp (ref "LED480")
      (value "LED3MM")
      (footprint "eagle-import:LED_3MM")
      (libsource (lib "eagle-import") (part "LED3MM"))
    )
    (comp (ref "LED481")
      (value "LED3MM")
      (footprint "eagle-import:LED_3MM")
      (libsource (lib "eagle-import") (part "LED3MM"))
    )
    (comp (ref "LED482")
      (value "LED3MM")
      (footprint "eagle-import:LED_3MM")
      (libsource (lib "eagle-import") (part "LED3MM"))
    )
    (comp (ref "LED483")
      (value "LED3MM")
      (footprint "eagle-import:LED_3MM")
      (libsource (lib "eagle-import") (part "LED3MM"))
    )
    (comp (ref "LED484")
      (value "LED3MM")
      (footprint "eagle-import:LED_3MM")
      (libsource (lib "eagle-import") (part "LED3MM"))
    )
    (comp (ref "LED485")
      (value "LED3MM")
      (footprint "eagle-import:LED_3MM")
      (libsource (lib "eagle-import") (part "LED3MM"))
    )
    (comp (ref "LED486")
      (value "LED3MM")
      (footprint "eagle-import:LED_3MM")
      (libsource (lib "eagle-import") (part "LED3MM"))
    )
    (comp (ref "LED487")
      (value "LED3MM")
      (footprint "eagle-import:LED_3MM")
      (libsource (lib "eagle-import") (part "LED3MM"))
    )
    (comp (ref "LED488")
      (value "LED3MM")
      (footprint "eagle-import:LED_3MM")
      (libsource (lib "eagle-import") (part "LED3MM"))
    )
    (comp (ref "LED489")
      (value "LED3MM")
      (footprint "eagle-import:LED_3MM")
      (libsource (lib "eagle-import") (part "LED3MM"))
    )
    (comp (ref "LED490")
      (value "LED3MM")
      (footprint "eagle-import:LED_3MM")
      (libsource (lib "eagle-import") (part "LED3MM"))
    )
    (comp (ref "LED491")
      (value "LED3MM")
      (footprint "eagle-import:LED_3MM")
      (libsource (lib "eagle-import") (part "LED3MM"))
    )
    (comp (ref "LED492")
      (value "LED3MM")
      (footprint "eagle-import:LED_3MM")
      (libsource (lib "eagle-import") (part "LED3MM"))
    )
    (comp (ref "LED493")
      (value "LED3MM")
      (footprint "eagle-import:LED_3MM")
      (libsource (lib "eagle-import") (part "LED3MM"))
    )
    (comp (ref "LED494")
      (value "LED3MM")
      (footprint "eagle-import:LED_3MM")
      (libsource (lib "eagle-import") (part "LED3MM"))
    )
    (comp (ref "LED495")
      (value "LED3MM")
      (footprint "eagle-import:LED_3MM")
      (libsource (lib "eagle-import") (part "LED3MM"))
    )
    (comp (ref "LED496")
      (value "LED3MM")
      (footprint "eagle-import:LED_3MM")
      (libsource (lib "eagle-import") (part "LED3MM"))
    )
    (comp (ref "LED497")
      (value "LED3MM")
      (footprint "eagle-import:LED_3MM")
      (libsource (lib "eagle-import") (part "LED3MM"))
    )
    (comp (ref "LED498")
      (value "LED3MM")
      (footprint "eagle-import:LED_3MM")
      (libsource (lib "eagle-import") (part "LED3MM"))
    )
    (comp (ref "LED499")
      (value "LED3MM")
      (footprint "eagle-import:LED_3MM")
      (libsource (lib "eagle-import") (part "LED3MM"))
    )
    (comp (ref "LED500")
      (value "LED3MM")
      (footprint "eagle-import:LED_3MM")
      (libsource (lib "eagle-import") (part "LED3MM"))
    )
    (comp (ref "LED501")
      (value "LED3MM")
      (footprint "eagle-import:LED_3MM")
      (libsource (lib "eagle-import") (part "LED3MM"))
    )
    (comp (ref "LED502")
      (value "LED3MM")
      (footprint "eagle-import:LED_3MM")
      (libsource (lib "eagle-import") (part "LED3MM"))
    )
    (comp (ref "LED503")
      (value "LED3MM")
      (footprint "eagle-import:LED_3MM")
      (libsource (lib "eagle-import") (part "LED3MM"))
    )
    (comp (ref "LED504")
      (value "LED3MM")
      (footprint "eagle-import:LED_3MM")
      (libsource (lib "eagle-import") (part "LED3MM"))
    )
    (comp (ref "LED505")
      (value "LED3MM")
      (footprint "eagle-import:LED_3MM")
      (libsource (lib "eagle-import") (part "LED3MM"))
    )
    (comp (ref "LED506")
      (value "LED3MM")
      (footprint "eagle-import:LED_3MM")
      (libsource (lib "eagle-import") (part "LED3MM"))
    )
    (comp (ref "LED507")
      (value "LED3MM")
      (footprint "eagle-import:LED_3MM")
      (libsource (lib "eagle-import") (part "LED3MM"))
    )
    (comp (ref "LED508")
      (value "LED3MM")
      (footprint "eagle-import:LED_3MM")
      (libsource (lib "eagle-import") (part "LED3MM"))
    )
    (comp (ref "LED509")
      (value "LED3MM")
      (footprint "eagle-import:LED_3MM")
      (libsource (lib "eagle-import") (part "LED3MM"))
    )
    (comp (ref "LED510")
      (value "LED3MM")
      (footprint "eagle-import:LED_3MM")
      (libsource (lib "eagle-import") (part "LED3MM"))
    )
    (comp (ref "LED511")
      (value "LED3MM")
      (footprint "eagle-import:LED_3MM")
      (libsource (lib "eagle-import") (part "LED3MM"))
    )
    (comp (ref "LED512")
      (value "LED3MM")
      (footprint "eagle-import:LED_3MM")
      (libsource (lib "eagle-import") (part "LED3MM"))
    )
    (comp (ref "LED513")
      (value "LED3MM")
      (footprint "eagle-import:LED_3MM")
      (libsource (lib "eagle-import") (part "LED3MM"))
    )
    (comp (ref "LED514")
      (value "LED3MM")
      (footprint "eagle-import:LED_3MM")
      (libsource (lib "eagle-import") (part "LED3MM"))
    )
    (comp (ref "LED515")
      (value "LED3MM")
      (footprint "eagle-import:LED_3MM")
      (libsource (lib "eagle-import") (part "LED3MM"))
    )
    (comp (ref "LED516")
      (value "LED3MM")
      (footprint "eagle-import:LED_3MM")
      (libsource (lib "eagle-import") (part "LED3MM"))
    )
    (comp (ref "LED517")
      (value "LED3MM")
      (footprint "eagle-import:LED_3MM")
      (libsource (lib "eagle-import") (part "LED3MM"))
    )
    (comp (ref "LED518")
      (value "LED3MM")
      (footprint "eagle-import:LED_3MM")
      (libsource (lib "eagle-import") (part "LED3MM"))
    )
    (comp (ref "LED519")
      (value "LED3MM")
      (footprint "eagle-import:LED_3MM")
      (libsource (lib "eagle-import") (part "LED3MM"))
    )
    (comp (ref "LED520")
      (value "LED3MM")
      (footprint "eagle-import:LED_3MM")
      (libsource (lib "eagle-import") (part "LED3MM"))
    )
    (comp (ref "LED521")
      (value "LED3MM")
      (footprint "eagle-import:LED_3MM")
      (libsource (lib "eagle-import") (part "LED3MM"))
    )
    (comp (ref "LED522")
      (value "LED3MM")
      (footprint "eagle-import:LED_3MM")
      (libsource (lib "eagle-import") (part "LED3MM"))
    )
    (comp (ref "LED523")
      (value "LED3MM")
      (footprint "eagle-import:LED_3MM")
      (libsource (lib "eagle-import") (part "LED3MM"))
    )
    (comp (ref "LED524")
      (value "LED3MM")
      (footprint "eagle-import:LED_3MM")
      (libsource (lib "eagle-import") (part "LED3MM"))
    )
    (comp (ref "LED525")
      (value "LED3MM")
      (footprint "eagle-import:LED_3MM")
      (libsource (lib "eagle-import") (part "LED3MM"))
    )
    (comp (ref "LED526")
      (value "LED3MM")
      (footprint "eagle-import:LED_3MM")
      (libsource (lib "eagle-import") (part "LED3MM"))
    )
    (comp (ref "LED527")
      (value "LED3MM")
      (footprint "eagle-import:LED_3MM")
      (libsource (lib "eagle-import") (part "LED3MM"))
    )
    (comp (ref "LED528")
      (value "LED3MM")
      (footprint "eagle-import:LED_3MM")
      (libsource (lib "eagle-import") (part "LED3MM"))
    )
    (comp (ref "LED529")
      (value "LED3MM")
      (footprint "eagle-import:LED_3MM")
      (libsource (lib "eagle-import") (part "LED3MM"))
    )
    (comp (ref "LED530")
      (value "LED3MM")
      (footprint "eagle-import:LED_3MM")
      (libsource (lib "eagle-import") (part "LED3MM"))
    )
    (comp (ref "LED531")
      (value "LED3MM")
      (footprint "eagle-import:LED_3MM")
      (libsource (lib "eagle-import") (part "LED3MM"))
    )
    (comp (ref "LED532")
      (value "LED3MM")
      (footprint "eagle-import:LED_3MM")
      (libsource (lib "eagle-import") (part "LED3MM"))
    )
    (comp (ref "LED533")
      (value "LED3MM")
      (footprint "eagle-import:LED_3MM")
      (libsource (lib "eagle-import") (part "LED3MM"))
    )
    (comp (ref "LED534")
      (value "LED3MM")
      (footprint "eagle-import:LED_3MM")
      (libsource (lib "eagle-import") (part "LED3MM"))
    )
    (comp (ref "LED535")
      (value "LED3MM")
      (footprint "eagle-import:LED_3MM")
      (libsource (lib "eagle-import") (part "LED3MM"))
    )
    (comp (ref "LED536")
      (value "LED3MM")
      (footprint "eagle-import:LED_3MM")
      (libsource (lib "eagle-import") (part "LED3MM"))
    )
    (comp (ref "LED537")
      (value "LED3MM")
      (footprint "eagle-import:LED_3MM")
      (libsource (lib "eagle-import") (part "LED3MM"))
    )
    (comp (ref "LED538")
      (value "LED3MM")
      (footprint "eagle-import:LED_3MM")
      (libsource (lib "eagle-import") (part "LED3MM"))
    )
    (comp (ref "LED539")
      (value "LED3MM")
      (footprint "eagle-import:LED_3MM")
      (libsource (lib "eagle-import") (part "LED3MM"))
    )
    (comp (ref "LED540")
      (value "LED3MM")
      (footprint "eagle-import:LED_3MM")
      (libsource (lib "eagle-import") (part "LED3MM"))
    )
    (comp (ref "LED541")
      (value "LED3MM")
      (footprint "eagle-import:LED_3MM")
      (libsource (lib "eagle-import") (part "LED3MM"))
    )
    (comp (ref "LED542")
      (value "LED3MM")
      (footprint "eagle-import:LED_3MM")
      (libsource (lib "eagle-import") (part "LED3MM"))
    )
    (comp (ref "LED543")
      (value "LED3MM")
      (footprint "eagle-import:LED_3MM")
      (libsource (lib "eagle-import") (part "LED3MM"))
    )
    (comp (ref "LED544")
      (value "LED3MM")
      (footprint "eagle-import:LED_3MM")
      (libsource (lib "eagle-import") (part "LED3MM"))
    )
    (comp (ref "LED545")
      (value "LED3MM")
      (footprint "eagle-import:LED_3MM")
      (libsource (lib "eagle-import") (part "LED3MM"))
    )
    (comp (ref "LED546")
      (value "LED3MM")
      (footprint "eagle-import:LED_3MM")
      (libsource (lib "eagle-import") (part "LED3MM"))
    )
    (comp (ref "LED547")
      (value "LED3MM")
      (footprint "eagle-import:LED_3MM")
      (libsource (lib "eagle-import") (part "LED3MM"))
    )
    (comp (ref "LED548")
      (value "LED3MM")
      (footprint "eagle-import:LED_3MM")
      (libsource (lib "eagle-import") (part "LED3MM"))
    )
    (comp (ref "LED549")
      (value "LED3MM")
      (footprint "eagle-import:LED_3MM")
      (libsource (lib "eagle-import") (part "LED3MM"))
    )
    (comp (ref "LED550")
      (value "LED3MM")
      (footprint "eagle-import:LED_3MM")
      (libsource (lib "eagle-import") (part "LED3MM"))
    )
    (comp (ref "LED551")
      (value "LED3MM")
      (footprint "eagle-import:LED_3MM")
      (libsource (lib "eagle-import") (part "LED3MM"))
    )
    (comp (ref "LED552")
      (value "LED3MM")
      (footprint "eagle-import:LED_3MM")
      (libsource (lib "eagle-import") (part "LED3MM"))
    )
    (comp (ref "LED553")
      (value "LED3MM")
      (footprint "eagle-import:LED_3MM")
      (libsource (lib "eagle-import") (part "LED3MM"))
    )
    (comp (ref "LED554")
      (value "LED3MM")
      (footprint "eagle-import:LED_3MM")
      (libsource (lib "eagle-import") (part "LED3MM"))
    )
    (comp (ref "LED555")
      (value "LED3MM")
      (footprint "eagle-import:LED_3MM")
      (libsource (lib "eagle-import") (part "LED3MM"))
    )
    (comp (ref "LED556")
      (value "LED3MM")
      (footprint "eagle-import:LED_3MM")
      (libsource (lib "eagle-import") (part "LED3MM"))
    )
    (comp (ref "LED557")
      (value "LED3MM")
      (footprint "eagle-import:LED_3MM")
      (libsource (lib "eagle-import") (part "LED3MM"))
    )
    (comp (ref "LED558")
      (value "LED3MM")
      (footprint "eagle-import:LED_3MM")
      (libsource (lib "eagle-import") (part "LED3MM"))
    )
    (comp (ref "LED559")
      (value "LED3MM")
      (footprint "eagle-import:LED_3MM")
      (libsource (lib "eagle-import") (part "LED3MM"))
    )
    (comp (ref "LED560")
      (value "LED3MM")
      (footprint "eagle-import:LED_3MM")
      (libsource (lib "eagle-import") (part "LED3MM"))
    )
    (comp (ref "LED561")
      (value "LED3MM")
      (footprint "eagle-import:LED_3MM")
      (libsource (lib "eagle-import") (part "LED3MM"))
    )
    (comp (ref "LED562")
      (value "LED3MM")
      (footprint "eagle-import:LED_3MM")
      (libsource (lib "eagle-import") (part "LED3MM"))
    )
    (comp (ref "LED563")
      (value "LED3MM")
      (footprint "eagle-import:LED_3MM")
      (libsource (lib "eagle-import") (part "LED3MM"))
    )
    (comp (ref "LED564")
      (value "LED3MM")
      (footprint "eagle-import:LED_3MM")
      (libsource (lib "eagle-import") (part "LED3MM"))
    )
    (comp (ref "LED565")
      (value "LED3MM")
      (footprint "eagle-import:LED_3MM")
      (libsource (lib "eagle-import") (part "LED3MM"))
    )
    (comp (ref "LED566")
      (value "LED3MM")
      (footprint "eagle-import:LED_3MM")
      (libsource (lib "eagle-import") (part "LED3MM"))
    )
    (comp (ref "LED567")
      (value "LED3MM")
      (footprint "eagle-import:LED_3MM")
      (libsource (lib "eagle-import") (part "LED3MM"))
    )
    (comp (ref "LED568")
      (value "LED3MM")
      (footprint "eagle-import:LED_3MM")
      (libsource (lib "eagle-import") (part "LED3MM"))
    )
    (comp (ref "LED569")
      (value "LED3MM")
      (footprint "eagle-import:LED_3MM")
      (libsource (lib "eagle-import") (part "LED3MM"))
    )
    (comp (ref "LED570")
      (value "LED3MM")
      (footprint "eagle-import:LED_3MM")
      (libsource (lib "eagle-import") (part "LED3MM"))
    )
    (comp (ref "LED571")
      (value "LED3MM")
      (footprint "eagle-import:LED_3MM")
      (libsource (lib "eagle-import") (part "LED3MM"))
    )
    (comp (ref "LED572")
      (value "LED3MM")
      (footprint "eagle-import:LED_3MM")
      (libsource (lib "eagle-import") (part "LED3MM"))
    )
    (comp (ref "LED573")
      (value "LED3MM")
      (footprint "eagle-import:LED_3MM")
      (libsource (lib "eagle-import") (part "LED3MM"))
    )
    (comp (ref "LED574")
      (value "LED3MM")
      (footprint "eagle-import:LED_3MM")
      (libsource (lib "eagle-import") (part "LED3MM"))
    )
    (comp (ref "LED575")
      (value "LED3MM")
      (footprint "eagle-import:LED_3MM")
      (libsource (lib "eagle-import") (part "LED3MM"))
    )
    (comp (ref "LED576")
      (value "LED3MM")
      (footprint "eagle-import:LED_3MM")
      (libsource (lib "eagle-import") (part "LED3MM"))
    )
    (comp (ref "LED577")
      (value "LED3MM")
      (footprint "eagle-import:LED_3MM")
      (libsource (lib "eagle-import") (part "LED3MM"))
    )
    (comp (ref "LED578")
      (value "LED3MM")
      (footprint "eagle-import:LED_3MM")
      (libsource (lib "eagle-import") (part "LED3MM"))
    )
    (comp (ref "LED579")
      (value "LED3MM")
      (footprint "eagle-import:LED_3MM")
      (libsource (lib "eagle-import") (part "LED3MM"))
    )
    (comp (ref "LED580")
      (value "LED3MM")
      (footprint "eagle-import:LED_3MM")
      (libsource (lib "eagle-import") (part "LED3MM"))
    )
    (comp (ref "LED581")
      (value "LED3MM")
      (footprint "eagle-import:LED_3MM")
      (libsource (lib "eagle-import") (part "LED3MM"))
    )
    (comp (ref "LED582")
      (value "LED3MM")
      (footprint "eagle-import:LED_3MM")
      (libsource (lib "eagle-import") (part "LED3MM"))
    )
    (comp (ref "LED583")
      (value "LED3MM")
      (footprint "eagle-import:LED_3MM")
      (libsource (lib "eagle-import") (part "LED3MM"))
    )
    (comp (ref "LED584")
      (value "LED3MM")
      (footprint "eagle-import:LED_3MM")
      (libsource (lib "eagle-import") (part "LED3MM"))
    )
    (comp (ref "LED585")
      (value "LED3MM")
      (footprint "eagle-import:LED_3MM")
      (libsource (lib "eagle-import") (part "LED3MM"))
    )
    (comp (ref "LED586")
      (value "LED3MM")
      (footprint "eagle-import:LED_3MM")
      (libsource (lib "eagle-import") (part "LED3MM"))
    )
    (comp (ref "LED587")
      (value "LED3MM")
      (footprint "eagle-import:LED_3MM")
      (libsource (lib "eagle-import") (part "LED3MM"))
    )
    (comp (ref "LED588")
      (value "LED3MM")
      (footprint "eagle-import:LED_3MM")
      (libsource (lib "eagle-import") (part "LED3MM"))
    )
    (comp (ref "LED589")
      (value "LED3MM")
      (footprint "eagle-import:LED_3MM")
      (libsource (lib "eagle-import") (part "LED3MM"))
    )
    (comp (ref "LED590")
      (value "LED3MM")
      (footprint "eagle-import:LED_3MM")
      (libsource (lib "eagle-import") (part "LED3MM"))
    )
    (comp (ref "LED591")
      (value "LED3MM")
      (footprint "eagle-import:LED_3MM")
      (libsource (lib "eagle-import") (part "LED3MM"))
    )
    (comp (ref "LED592")
      (value "LED3MM")
      (footprint "eagle-import:LED_3MM")
      (libsource (lib "eagle-import") (part "LED3MM"))
    )
    (comp (ref "LED593")
      (value "LED3MM")
      (footprint "eagle-import:LED_3MM")
      (libsource (lib "eagle-import") (part "LED3MM"))
    )
    (comp (ref "LED594")
      (value "LED3MM")
      (footprint "eagle-import:LED_3MM")
      (libsource (lib "eagle-import") (part "LED3MM"))
    )
    (comp (ref "LED595")
      (value "LED3MM")
      (footprint "eagle-import:LED_3MM")
      (libsource (lib "eagle-import") (part "LED3MM"))
    )
    (comp (ref "LED596")
      (value "LED3MM")
      (footprint "eagle-import:LED_3MM")
      (libsource (lib "eagle-import") (part "LED3MM"))
    )
    (comp (ref "LED597")
      (value "LED3MM")
      (footprint "eagle-import:LED_3MM")
      (libsource (lib "eagle-import") (part "LED3MM"))
    )
    (comp (ref "LED598")
      (value "LED3MM")
      (footprint "eagle-import:LED_3MM")
      (libsource (lib "eagle-import") (part "LED3MM"))
    )
    (comp (ref "LED599")
      (value "LED3MM")
      (footprint "eagle-import:LED_3MM")
      (libsource (lib "eagle-import") (part "LED3MM"))
    )
    (comp (ref "LED600")
      (value "LED3MM")
      (footprint "eagle-import:LED_3MM")
      (libsource (lib "eagle-import") (part "LED3MM"))
    )
    (comp (ref "LED601")
      (value "LED3MM")
      (footprint "eagle-import:LED_3MM")
      (libsource (lib "eagle-import") (part "LED3MM"))
    )
    (comp (ref "LED602")
      (value "LED3MM")
      (footprint "eagle-import:LED_3MM")
      (libsource (lib "eagle-import") (part "LED3MM"))
    )
    (comp (ref "LED603")
      (value "LED3MM")
      (footprint "eagle-import:LED_3MM")
      (libsource (lib "eagle-import") (part "LED3MM"))
    )
    (comp (ref "LED604")
      (value "LED3MM")
      (footprint "eagle-import:LED_3MM")
      (libsource (lib "eagle-import") (part "LED3MM"))
    )
    (comp (ref "LED605")
      (value "LED3MM")
      (footprint "eagle-import:LED_3MM")
      (libsource (lib "eagle-import") (part "LED3MM"))
    )
    (comp (ref "LED606")
      (value "LED3MM")
      (footprint "eagle-import:LED_3MM")
      (libsource (lib "eagle-import") (part "LED3MM"))
    )
    (comp (ref "LED607")
      (value "LED3MM")
      (footprint "eagle-import:LED_3MM")
      (libsource (lib "eagle-import") (part "LED3MM"))
    )
    (comp (ref "LED608")
      (value "LED3MM")
      (footprint "eagle-import:LED_3MM")
      (libsource (lib "eagle-import") (part "LED3MM"))
    )
    (comp (ref "LED609")
      (value "LED3MM")
      (footprint "eagle-import:LED_3MM")
      (libsource (lib "eagle-import") (part "LED3MM"))
    )
    (comp (ref "LED610")
      (value "LED3MM")
      (footprint "eagle-import:LED_3MM")
      (libsource (lib "eagle-import") (part "LED3MM"))
    )
    (comp (ref "LED611")
      (value "LED3MM")
      (footprint "eagle-import:LED_3MM")
      (libsource (lib "eagle-import") (part "LED3MM"))
    )
    (comp (ref "LED612")
      (value "LED3MM")
      (footprint "eagle-import:LED_3MM")
      (libsource (lib "eagle-import") (part "LED3MM"))
    )
    (comp (ref "LED613")
      (value "LED3MM")
      (footprint "eagle-import:LED_3MM")
      (libsource (lib "eagle-import") (part "LED3MM"))
    )
    (comp (ref "LED614")
      (value "LED3MM")
      (footprint "eagle-import:LED_3MM")
      (libsource (lib "eagle-import") (part "LED3MM"))
    )
    (comp (ref "LED615")
      (value "LED3MM")
      (footprint "eagle-import:LED_3MM")
      (libsource (lib "eagle-import") (part "LED3MM"))
    )
    (comp (ref "LED616")
      (value "LED3MM")
      (footprint "eagle-import:LED_3MM")
      (libsource (lib "eagle-import") (part "LED3MM"))
    )
    (comp (ref "LED617")
      (value "LED3MM")
      (footprint "eagle-import:LED_3MM")
      (libsource (lib "eagle-import") (part "LED3MM"))
    )
    (comp (ref "LED618")
      (value "LED3MM")
      (footprint "eagle-import:LED_3MM")
      (libsource (lib "eagle-import") (part "LED3MM"))
    )
    (comp (ref "LED619")
      (value "LED3MM")
      (footprint "eagle-import:LED_3MM")
      (libsource (lib "eagle-import") (part "LED3MM"))
    )
    (comp (ref "LED620")
      (value "LED3MM")
      (footprint "eagle-import:LED_3MM")
      (libsource (lib "eagle-import") (part "LED3MM"))
    )
    (comp (ref "LED621")
      (value "LED3MM")
      (footprint "eagle-import:LED_3MM")
      (libsource (lib "eagle-import") (part "LED3MM"))
    )
    (comp (ref "LED622")
      (value "LED3MM")
      (footprint "eagle-import:LED_3MM")
      (libsource (lib "eagle-import") (part "LED3MM"))
    )
    (comp (ref "LED623")
      (value "LED3MM")
      (footprint "eagle-import:LED_3MM")
      (libsource (lib "eagle-import") (part "LED3MM"))
    )
    (comp (ref "LED624")
      (value "LED3MM")
      (footprint "eagle-import:LED_3MM")
      (libsource (lib "eagle-import") (part "LED3MM"))
    )
    (comp (ref "LED703")
      (value "LED3MM")
      (footprint "eagle-import:LED_3MM")
      (libsource (lib "eagle-import") (part "LED3MM"))
    )
    (comp (ref "LED704")
      (value "LED3MM")
      (footprint "eagle-import:LED_3MM")
      (libsource (lib "eagle-import") (part "LED3MM"))
    )
    (comp (ref "LED705")
      (value "LED3MM")
      (footprint "eagle-import:LED_3MM")
      (libsource (lib "eagle-import") (part "LED3MM"))
    )
    (comp (ref "LED706")
      (value "LED3MM")
      (footprint "eagle-import:LED_3MM")
      (libsource (lib "eagle-import") (part "LED3MM"))
    )
    (comp (ref "LED707")
      (value "LED3MM")
      (footprint "eagle-import:LED_3MM")
      (libsource (lib "eagle-import") (part "LED3MM"))
    )
    (comp (ref "LED708")
      (value "LED3MM")
      (footprint "eagle-import:LED_3MM")
      (libsource (lib "eagle-import") (part "LED3MM"))
    )
    (comp (ref "LED709")
      (value "LED3MM")
      (footprint "eagle-import:LED_3MM")
      (libsource (lib "eagle-import") (part "LED3MM"))
    )
    (comp (ref "LED710")
      (value "LED3MM")
      (footprint "eagle-import:LED_3MM")
      (libsource (lib "eagle-import") (part "LED3MM"))
    )
    (comp (ref "LED711")
      (value "LED3MM")
      (footprint "eagle-import:LED_3MM")
      (libsource (lib "eagle-import") (part "LED3MM"))
    )
    (comp (ref "LED712")
      (value "LED3MM")
      (footprint "eagle-import:LED_3MM")
      (libsource (lib "eagle-import") (part "LED3MM"))
    )
    (comp (ref "LED713")
      (value "LED3MM")
      (footprint "eagle-import:LED_3MM")
      (libsource (lib "eagle-import") (part "LED3MM"))
    )
    (comp (ref "LED714")
      (value "LED3MM")
      (footprint "eagle-import:LED_3MM")
      (libsource (lib "eagle-import") (part "LED3MM"))
    )
    (comp (ref "LED715")
      (value "LED3MM")
      (footprint "eagle-import:LED_3MM")
      (libsource (lib "eagle-import") (part "LED3MM"))
    )
    (comp (ref "LED716")
      (value "LED3MM")
      (footprint "eagle-import:LED_3MM")
      (libsource (lib "eagle-import") (part "LED3MM"))
    )
    (comp (ref "LED717")
      (value "LED3MM")
      (footprint "eagle-import:LED_3MM")
      (libsource (lib "eagle-import") (part "LED3MM"))
    )
    (comp (ref "LED718")
      (value "LED3MM")
      (footprint "eagle-import:LED_3MM")
      (libsource (lib "eagle-import") (part "LED3MM"))
    )
    (comp (ref "LED719")
      (value "LED3MM")
      (footprint "eagle-import:LED_3MM")
      (libsource (lib "eagle-import") (part "LED3MM"))
    )
    (comp (ref "LED720")
      (value "LED3MM")
      (footprint "eagle-import:LED_3MM")
      (libsource (lib "eagle-import") (part "LED3MM"))
    )
    (comp (ref "LED721")
      (value "LED3MM")
      (footprint "eagle-import:LED_3MM")
      (libsource (lib "eagle-import") (part "LED3MM"))
    )
    (comp (ref "LED722")
      (value "LED3MM")
      (footprint "eagle-import:LED_3MM")
      (libsource (lib "eagle-import") (part "LED3MM"))
    )
    (comp (ref "LED723")
      (value "LED3MM")
      (footprint "eagle-import:LED_3MM")
      (libsource (lib "eagle-import") (part "LED3MM"))
    )
    (comp (ref "LED724")
      (value "LED3MM")
      (footprint "eagle-import:LED_3MM")
      (libsource (lib "eagle-import") (part "LED3MM"))
    )
    (comp (ref "LED725")
      (value "LED3MM")
      (footprint "eagle-import:LED_3MM")
      (libsource (lib "eagle-import") (part "LED3MM"))
    )
    (comp (ref "LED726")
      (value "LED3MM")
      (footprint "eagle-import:LED_3MM")
      (libsource (lib "eagle-import") (part "LED3MM"))
    )
    (comp (ref "LED727")
      (value "LED3MM")
      (footprint "eagle-import:LED_3MM")
      (libsource (lib "eagle-import") (part "LED3MM"))
    )
    (comp (ref "LED728")
      (value "LED3MM")
      (footprint "eagle-import:LED_3MM")
      (libsource (lib "eagle-import") (part "LED3MM"))
    )
    (comp (ref "LED729")
      (value "LED3MM")
      (footprint "eagle-import:LED_3MM")
      (libsource (lib "eagle-import") (part "LED3MM"))
    )
    (comp (ref "LED730")
      (value "LED3MM")
      (footprint "eagle-import:LED_3MM")
      (libsource (lib "eagle-import") (part "LED3MM"))
    )
    (comp (ref "LED731")
      (value "LED3MM")
      (footprint "eagle-import:LED_3MM")
      (libsource (lib "eagle-import") (part "LED3MM"))
    )
    (comp (ref "LED732")
      (value "LED3MM")
      (footprint "eagle-import:LED_3MM")
      (libsource (lib "eagle-import") (part "LED3MM"))
    )
    (comp (ref "LED733")
      (value "LED3MM")
      (footprint "eagle-import:LED_3MM")
      (libsource (lib "eagle-import") (part "LED3MM"))
    )
    (comp (ref "LED734")
      (value "LED3MM")
      (footprint "eagle-import:LED_3MM")
      (libsource (lib "eagle-import") (part "LED3MM"))
    )
    (comp (ref "LED735")
      (value "LED3MM")
      (footprint "eagle-import:LED_3MM")
      (libsource (lib "eagle-import") (part "LED3MM"))
    )
    (comp (ref "LED736")
      (value "LED3MM")
      (footprint "eagle-import:LED_3MM")
      (libsource (lib "eagle-import") (part "LED3MM"))
    )
    (comp (ref "LED737")
      (value "LED3MM")
      (footprint "eagle-import:LED_3MM")
      (libsource (lib "eagle-import") (part "LED3MM"))
    )
    (comp (ref "LED738")
      (value "LED3MM")
      (footprint "eagle-import:LED_3MM")
      (libsource (lib "eagle-import") (part "LED3MM"))
    )
    (comp (ref "LED739")
      (value "LED3MM")
      (footprint "eagle-import:LED_3MM")
      (libsource (lib "eagle-import") (part "LED3MM"))
    )
    (comp (ref "LED740")
      (value "LED3MM")
      (footprint "eagle-import:LED_3MM")
      (libsource (lib "eagle-import") (part "LED3MM"))
    )
    (comp (ref "LED741")
      (value "LED3MM")
      (footprint "eagle-import:LED_3MM")
      (libsource (lib "eagle-import") (part "LED3MM"))
    )
    (comp (ref "LED742")
      (value "LED3MM")
      (footprint "eagle-import:LED_3MM")
      (libsource (lib "eagle-import") (part "LED3MM"))
    )
    (comp (ref "LED743")
      (value "LED3MM")
      (footprint "eagle-import:LED_3MM")
      (libsource (lib "eagle-import") (part "LED3MM"))
    )
    (comp (ref "LED744")
      (value "LED3MM")
      (footprint "eagle-import:LED_3MM")
      (libsource (lib "eagle-import") (part "LED3MM"))
    )
    (comp (ref "LED745")
      (value "LED3MM")
      (footprint "eagle-import:LED_3MM")
      (libsource (lib "eagle-import") (part "LED3MM"))
    )
    (comp (ref "LED746")
      (value "LED3MM")
      (footprint "eagle-import:LED_3MM")
      (libsource (lib "eagle-import") (part "LED3MM"))
    )
    (comp (ref "LED747")
      (value "LED3MM")
      (footprint "eagle-import:LED_3MM")
      (libsource (lib "eagle-import") (part "LED3MM"))
    )
    (comp (ref "LED748")
      (value "LED3MM")
      (footprint "eagle-import:LED_3MM")
      (libsource (lib "eagle-import") (part "LED3MM"))
    )
    (comp (ref "LED749")
      (value "LED3MM")
      (footprint "eagle-import:LED_3MM")
      (libsource (lib "eagle-import") (part "LED3MM"))
    )
    (comp (ref "LED750")
      (value "LED3MM")
      (footprint "eagle-import:LED_3MM")
      (libsource (lib "eagle-import") (part "LED3MM"))
    )
    (comp (ref "LED751")
      (value "LED3MM")
      (footprint "eagle-import:LED_3MM")
      (libsource (lib "eagle-import") (part "LED3MM"))
    )
    (comp (ref "LED752")
      (value "LED3MM")
      (footprint "eagle-import:LED_3MM")
      (libsource (lib "eagle-import") (part "LED3MM"))
    )
    (comp (ref "LED753")
      (value "LED3MM")
      (footprint "eagle-import:LED_3MM")
      (libsource (lib "eagle-import") (part "LED3MM"))
    )
    (comp (ref "LED754")
      (value "LED3MM")
      (footprint "eagle-import:LED_3MM")
      (libsource (lib "eagle-import") (part "LED3MM"))
    )
    (comp (ref "LED755")
      (value "LED3MM")
      (footprint "eagle-import:LED_3MM")
      (libsource (lib "eagle-import") (part "LED3MM"))
    )
    (comp (ref "LED756")
      (value "LED3MM")
      (footprint "eagle-import:LED_3MM")
      (libsource (lib "eagle-import") (part "LED3MM"))
    )
    (comp (ref "LED757")
      (value "LED3MM")
      (footprint "eagle-import:LED_3MM")
      (libsource (lib "eagle-import") (part "LED3MM"))
    )
    (comp (ref "LED758")
      (value "LED3MM")
      (footprint "eagle-import:LED_3MM")
      (libsource (lib "eagle-import") (part "LED3MM"))
    )
    (comp (ref "LED759")
      (value "LED3MM")
      (footprint "eagle-import:LED_3MM")
      (libsource (lib "eagle-import") (part "LED3MM"))
    )
    (comp (ref "LED760")
      (value "LED3MM")
      (footprint "eagle-import:LED_3MM")
      (libsource (lib "eagle-import") (part "LED3MM"))
    )
    (comp (ref "LED761")
      (value "LED3MM")
      (footprint "eagle-import:LED_3MM")
      (libsource (lib "eagle-import") (part "LED3MM"))
    )
    (comp (ref "LED762")
      (value "LED3MM")
      (footprint "eagle-import:LED_3MM")
      (libsource (lib "eagle-import") (part "LED3MM"))
    )
    (comp (ref "LED763")
      (value "LED3MM")
      (footprint "eagle-import:LED_3MM")
      (libsource (lib "eagle-import") (part "LED3MM"))
    )
    (comp (ref "LED764")
      (value "LED3MM")
      (footprint "eagle-import:LED_3MM")
      (libsource (lib "eagle-import") (part "LED3MM"))
    )
    (comp (ref "LED765")
      (value "LED3MM")
      (footprint "eagle-import:LED_3MM")
      (libsource (lib "eagle-import") (part "LED3MM"))
    )
    (comp (ref "LED766")
      (value "LED3MM")
      (footprint "eagle-import:LED_3MM")
      (libsource (lib "eagle-import") (part "LED3MM"))
    )
    (comp (ref "LED767")
      (value "LED3MM")
      (footprint "eagle-import:LED_3MM")
      (libsource (lib "eagle-import") (part "LED3MM"))
    )
    (comp (ref "LED768")
      (value "LED3MM")
      (footprint "eagle-import:LED_3MM")
      (libsource (lib "eagle-import") (part "LED3MM"))
    )
    (comp (ref "LED769")
      (value "LED3MM")
      (footprint "eagle-import:LED_3MM")
      (libsource (lib "eagle-import") (part "LED3MM"))
    )
    (comp (ref "LED770")
      (value "LED3MM")
      (footprint "eagle-import:LED_3MM")
      (libsource (lib "eagle-import") (part "LED3MM"))
    )
    (comp (ref "LED771")
      (value "LED3MM")
      (footprint "eagle-import:LED_3MM")
      (libsource (lib "eagle-import") (part "LED3MM"))
    )
    (comp (ref "LED772")
      (value "LED3MM")
      (footprint "eagle-import:LED_3MM")
      (libsource (lib "eagle-import") (part "LED3MM"))
    )
    (comp (ref "LED773")
      (value "LED3MM")
      (footprint "eagle-import:LED_3MM")
      (libsource (lib "eagle-import") (part "LED3MM"))
    )
    (comp (ref "LED774")
      (value "LED3MM")
      (footprint "eagle-import:LED_3MM")
      (libsource (lib "eagle-import") (part "LED3MM"))
    )
    (comp (ref "LED775")
      (value "LED3MM")
      (footprint "eagle-import:LED_3MM")
      (libsource (lib "eagle-import") (part "LED3MM"))
    )
    (comp (ref "LED776")
      (value "LED3MM")
      (footprint "eagle-import:LED_3MM")
      (libsource (lib "eagle-import") (part "LED3MM"))
    )
    (comp (ref "LED777")
      (value "LED3MM")
      (footprint "eagle-import:LED_3MM")
      (libsource (lib "eagle-import") (part "LED3MM"))
    )
    (comp (ref "LED778")
      (value "LED3MM")
      (footprint "eagle-import:LED_3MM")
      (libsource (lib "eagle-import") (part "LED3MM"))
    )
    (comp (ref "LED779")
      (value "LED3MM")
      (footprint "eagle-import:LED_3MM")
      (libsource (lib "eagle-import") (part "LED3MM"))
    )
    (comp (ref "LED780")
      (value "LED3MM")
      (footprint "eagle-import:LED_3MM")
      (libsource (lib "eagle-import") (part "LED3MM"))
    )
    (comp (ref "LED781")
      (value "LED3MM")
      (footprint "eagle-import:LED_3MM")
      (libsource (lib "eagle-import") (part "LED3MM"))
    )
    (comp (ref "LED782")
      (value "LED3MM")
      (footprint "eagle-import:LED_3MM")
      (libsource (lib "eagle-import") (part "LED3MM"))
    )
    (comp (ref "LED783")
      (value "LED3MM")
      (footprint "eagle-import:LED_3MM")
      (libsource (lib "eagle-import") (part "LED3MM"))
    )
    (comp (ref "LED784")
      (value "LED3MM")
      (footprint "eagle-import:LED_3MM")
      (libsource (lib "eagle-import") (part "LED3MM"))
    )
    (comp (ref "LED785")
      (value "LED3MM")
      (footprint "eagle-import:LED_3MM")
      (libsource (lib "eagle-import") (part "LED3MM"))
    )
    (comp (ref "LED786")
      (value "LED3MM")
      (footprint "eagle-import:LED_3MM")
      (libsource (lib "eagle-import") (part "LED3MM"))
    )
    (comp (ref "LED787")
      (value "LED3MM")
      (footprint "eagle-import:LED_3MM")
      (libsource (lib "eagle-import") (part "LED3MM"))
    )
    (comp (ref "LED788")
      (value "LED3MM")
      (footprint "eagle-import:LED_3MM")
      (libsource (lib "eagle-import") (part "LED3MM"))
    )
    (comp (ref "LED789")
      (value "LED3MM")
      (footprint "eagle-import:LED_3MM")
      (libsource (lib "eagle-import") (part "LED3MM"))
    )
    (comp (ref "LED790")
      (value "LED3MM")
      (footprint "eagle-import:LED_3MM")
      (libsource (lib "eagle-import") (part "LED3MM"))
    )
    (comp (ref "LED791")
      (value "LED3MM")
      (footprint "eagle-import:LED_3MM")
      (libsource (lib "eagle-import") (part "LED3MM"))
    )
    (comp (ref "LED792")
      (value "LED3MM")
      (footprint "eagle-import:LED_3MM")
      (libsource (lib "eagle-import") (part "LED3MM"))
    )
    (comp (ref "LED793")
      (value "LED3MM")
      (footprint "eagle-import:LED_3MM")
      (libsource (lib "eagle-import") (part "LED3MM"))
    )
    (comp (ref "LED794")
      (value "LED3MM")
      (footprint "eagle-import:LED_3MM")
      (libsource (lib "eagle-import") (part "LED3MM"))
    )
    (comp (ref "LED795")
      (value "LED3MM")
      (footprint "eagle-import:LED_3MM")
      (libsource (lib "eagle-import") (part "LED3MM"))
    )
    (comp (ref "LED796")
      (value "LED3MM")
      (footprint "eagle-import:LED_3MM")
      (libsource (lib "eagle-import") (part "LED3MM"))
    )
    (comp (ref "LED797")
      (value "LED3MM")
      (footprint "eagle-import:LED_3MM")
      (libsource (lib "eagle-import") (part "LED3MM"))
    )
    (comp (ref "LED798")
      (value "LED3MM")
      (footprint "eagle-import:LED_3MM")
      (libsource (lib "eagle-import") (part "LED3MM"))
    )
    (comp (ref "LED799")
      (value "LED3MM")
      (footprint "eagle-import:LED_3MM")
      (libsource (lib "eagle-import") (part "LED3MM"))
    )
    (comp (ref "LED800")
      (value "LED3MM")
      (footprint "eagle-import:LED_3MM")
      (libsource (lib "eagle-import") (part "LED3MM"))
    )
    (comp (ref "LED801")
      (value "LED3MM")
      (footprint "eagle-import:LED_3MM")
      (libsource (lib "eagle-import") (part "LED3MM"))
    )
    (comp (ref "LED802")
      (value "LED3MM")
      (footprint "eagle-import:LED_3MM")
      (libsource (lib "eagle-import") (part "LED3MM"))
    )
    (comp (ref "LED803")
      (value "LED3MM")
      (footprint "eagle-import:LED_3MM")
      (libsource (lib "eagle-import") (part "LED3MM"))
    )
    (comp (ref "LED804")
      (value "LED3MM")
      (footprint "eagle-import:LED_3MM")
      (libsource (lib "eagle-import") (part "LED3MM"))
    )
    (comp (ref "LED805")
      (value "LED3MM")
      (footprint "eagle-import:LED_3MM")
      (libsource (lib "eagle-import") (part "LED3MM"))
    )
    (comp (ref "LED806")
      (value "LED3MM")
      (footprint "eagle-import:LED_3MM")
      (libsource (lib "eagle-import") (part "LED3MM"))
    )
    (comp (ref "LED807")
      (value "LED3MM")
      (footprint "eagle-import:LED_3MM")
      (libsource (lib "eagle-import") (part "LED3MM"))
    )
    (comp (ref "LED808")
      (value "LED3MM")
      (footprint "eagle-import:LED_3MM")
      (libsource (lib "eagle-import") (part "LED3MM"))
    )
    (comp (ref "LED809")
      (value "LED3MM")
      (footprint "eagle-import:LED_3MM")
      (libsource (lib "eagle-import") (part "LED3MM"))
    )
    (comp (ref "LED810")
      (value "LED3MM")
      (footprint "eagle-import:LED_3MM")
      (libsource (lib "eagle-import") (part "LED3MM"))
    )
    (comp (ref "LED811")
      (value "LED3MM")
      (footprint "eagle-import:LED_3MM")
      (libsource (lib "eagle-import") (part "LED3MM"))
    )
    (comp (ref "LED812")
      (value "LED3MM")
      (footprint "eagle-import:LED_3MM")
      (libsource (lib "eagle-import") (part "LED3MM"))
    )
    (comp (ref "LED813")
      (value "LED3MM")
      (footprint "eagle-import:LED_3MM")
      (libsource (lib "eagle-import") (part "LED3MM"))
    )
    (comp (ref "LED814")
      (value "LED3MM")
      (footprint "eagle-import:LED_3MM")
      (libsource (lib "eagle-import") (part "LED3MM"))
    )
    (comp (ref "LED815")
      (value "LED3MM")
      (footprint "eagle-import:LED_3MM")
      (libsource (lib "eagle-import") (part "LED3MM"))
    )
    (comp (ref "LED816")
      (value "LED3MM")
      (footprint "eagle-import:LED_3MM")
      (libsource (lib "eagle-import") (part "LED3MM"))
    )
    (comp (ref "LED817")
      (value "LED3MM")
      (footprint "eagle-import:LED_3MM")
      (libsource (lib "eagle-import") (part "LED3MM"))
    )
    (comp (ref "LED818")
      (value "LED3MM")
      (footprint "eagle-import:LED_3MM")
      (libsource (lib "eagle-import") (part "LED3MM"))
    )
    (comp (ref "LED819")
      (value "LED3MM")
      (footprint "eagle-import:LED_3MM")
      (libsource (lib "eagle-import") (part "LED3MM"))
    )
    (comp (ref "LED820")
      (value "LED3MM")
      (footprint "eagle-import:LED_3MM")
      (libsource (lib "eagle-import") (part "LED3MM"))
    )
    (comp (ref "LED821")
      (value "LED3MM")
      (footprint "eagle-import:LED_3MM")
      (libsource (lib "eagle-import") (part "LED3MM"))
    )
    (comp (ref "LED822")
      (value "LED3MM")
      (footprint "eagle-import:LED_3MM")
      (libsource (lib "eagle-import") (part "LED3MM"))
    )
    (comp (ref "LED823")
      (value "LED3MM")
      (footprint "eagle-import:LED_3MM")
      (libsource (lib "eagle-import") (part "LED3MM"))
    )
    (comp (ref "LED824")
      (value "LED3MM")
      (footprint "eagle-import:LED_3MM")
      (libsource (lib "eagle-import") (part "LED3MM"))
    )
    (comp (ref "LED825")
      (value "LED3MM")
      (footprint "eagle-import:LED_3MM")
      (libsource (lib "eagle-import") (part "LED3MM"))
    )
    (comp (ref "LED826")
      (value "LED3MM")
      (footprint "eagle-import:LED_3MM")
      (libsource (lib "eagle-import") (part "LED3MM"))
    )
    (comp (ref "LED827")
      (value "LED3MM")
      (footprint "eagle-import:LED_3MM")
      (libsource (lib "eagle-import") (part "LED3MM"))
    )
    (comp (ref "LED828")
      (value "LED3MM")
      (footprint "eagle-import:LED_3MM")
      (libsource (lib "eagle-import") (part "LED3MM"))
    )
    (comp (ref "LED829")
      (value "LED3MM")
      (footprint "eagle-import:LED_3MM")
      (libsource (lib "eagle-import") (part "LED3MM"))
    )
    (comp (ref "LED830")
      (value "LED3MM")
      (footprint "eagle-import:LED_3MM")
      (libsource (lib "eagle-import") (part "LED3MM"))
    )
    (comp (ref "LED831")
      (value "LED3MM")
      (footprint "eagle-import:LED_3MM")
      (libsource (lib "eagle-import") (part "LED3MM"))
    )
    (comp (ref "LED832")
      (value "LED3MM")
      (footprint "eagle-import:LED_3MM")
      (libsource (lib "eagle-import") (part "LED3MM"))
    )
    (comp (ref "LED833")
      (value "LED3MM")
      (footprint "eagle-import:LED_3MM")
      (libsource (lib "eagle-import") (part "LED3MM"))
    )
    (comp (ref "LED834")
      (value "LED3MM")
      (footprint "eagle-import:LED_3MM")
      (libsource (lib "eagle-import") (part "LED3MM"))
    )
    (comp (ref "LED835")
      (value "LED3MM")
      (footprint "eagle-import:LED_3MM")
      (libsource (lib "eagle-import") (part "LED3MM"))
    )
    (comp (ref "LED836")
      (value "LED3MM")
      (footprint "eagle-import:LED_3MM")
      (libsource (lib "eagle-import") (part "LED3MM"))
    )
    (comp (ref "LED837")
      (value "LED3MM")
      (footprint "eagle-import:LED_3MM")
      (libsource (lib "eagle-import") (part "LED3MM"))
    )
    (comp (ref "LED838")
      (value "LED3MM")
      (footprint "eagle-import:LED_3MM")
      (libsource (lib "eagle-import") (part "LED3MM"))
    )
    (comp (ref "LED839")
      (value "LED3MM")
      (footprint "eagle-import:LED_3MM")
      (libsource (lib "eagle-import") (part "LED3MM"))
    )
    (comp (ref "LED840")
      (value "LED3MM")
      (footprint "eagle-import:LED_3MM")
      (libsource (lib "eagle-import") (part "LED3MM"))
    )
    (comp (ref "LED841")
      (value "LED3MM")
      (footprint "eagle-import:LED_3MM")
      (libsource (lib "eagle-import") (part "LED3MM"))
    )
    (comp (ref "LED842")
      (value "LED3MM")
      (footprint "eagle-import:LED_3MM")
      (libsource (lib "eagle-import") (part "LED3MM"))
    )
    (comp (ref "LED843")
      (value "LED3MM")
      (footprint "eagle-import:LED_3MM")
      (libsource (lib "eagle-import") (part "LED3MM"))
    )
    (comp (ref "LED844")
      (value "LED3MM")
      (footprint "eagle-import:LED_3MM")
      (libsource (lib "eagle-import") (part "LED3MM"))
    )
    (comp (ref "LED845")
      (value "LED3MM")
      (footprint "eagle-import:LED_3MM")
      (libsource (lib "eagle-import") (part "LED3MM"))
    )
    (comp (ref "LED846")
      (value "LED3MM")
      (footprint "eagle-import:LED_3MM")
      (libsource (lib "eagle-import") (part "LED3MM"))
    )
    (comp (ref "LED847")
      (value "LED3MM")
      (footprint "eagle-import:LED_3MM")
      (libsource (lib "eagle-import") (part "LED3MM"))
    )
    (comp (ref "LED848")
      (value "LED3MM")
      (footprint "eagle-import:LED_3MM")
      (libsource (lib "eagle-import") (part "LED3MM"))
    )
    (comp (ref "LED849")
      (value "LED3MM")
      (footprint "eagle-import:LED_3MM")
      (libsource (lib "eagle-import") (part "LED3MM"))
    )
    (comp (ref "LED850")
      (value "LED3MM")
      (footprint "eagle-import:LED_3MM")
      (libsource (lib "eagle-import") (part "LED3MM"))
    )
    (comp (ref "LED851")
      (value "LED3MM")
      (footprint "eagle-import:LED_3MM")
      (libsource (lib "eagle-import") (part "LED3MM"))
    )
    (comp (ref "LED852")
      (value "LED3MM")
      (footprint "eagle-import:LED_3MM")
      (libsource (lib "eagle-import") (part "LED3MM"))
    )
    (comp (ref "LED853")
      (value "LED3MM")
      (footprint "eagle-import:LED_3MM")
      (libsource (lib "eagle-import") (part "LED3MM"))
    )
    (comp (ref "LED854")
      (value "LED3MM")
      (footprint "eagle-import:LED_3MM")
      (libsource (lib "eagle-import") (part "LED3MM"))
    )
    (comp (ref "LED855")
      (value "LED3MM")
      (footprint "eagle-import:LED_3MM")
      (libsource (lib "eagle-import") (part "LED3MM"))
    )
    (comp (ref "LED856")
      (value "LED3MM")
      (footprint "eagle-import:LED_3MM")
      (libsource (lib "eagle-import") (part "LED3MM"))
    )
    (comp (ref "LED857")
      (value "LED3MM")
      (footprint "eagle-import:LED_3MM")
      (libsource (lib "eagle-import") (part "LED3MM"))
    )
    (comp (ref "LED858")
      (value "LED3MM")
      (footprint "eagle-import:LED_3MM")
      (libsource (lib "eagle-import") (part "LED3MM"))
    )
    (comp (ref "LED859")
      (value "LED3MM")
      (footprint "eagle-import:LED_3MM")
      (libsource (lib "eagle-import") (part "LED3MM"))
    )
    (comp (ref "LED860")
      (value "LED3MM")
      (footprint "eagle-import:LED_3MM")
      (libsource (lib "eagle-import") (part "LED3MM"))
    )
    (comp (ref "LED861")
      (value "LED3MM")
      (footprint "eagle-import:LED_3MM")
      (libsource (lib "eagle-import") (part "LED3MM"))
    )
    (comp (ref "LED862")
      (value "LED3MM")
      (footprint "eagle-import:LED_3MM")
      (libsource (lib "eagle-import") (part "LED3MM"))
    )
    (comp (ref "LED863")
      (value "LED3MM")
      (footprint "eagle-import:LED_3MM")
      (libsource (lib "eagle-import") (part "LED3MM"))
    )
    (comp (ref "LED864")
      (value "LED3MM")
      (footprint "eagle-import:LED_3MM")
      (libsource (lib "eagle-import") (part "LED3MM"))
    )
    (comp (ref "LED865")
      (value "LED3MM")
      (footprint "eagle-import:LED_3MM")
      (libsource (lib "eagle-import") (part "LED3MM"))
    )
    (comp (ref "LED866")
      (value "LED3MM")
      (footprint "eagle-import:LED_3MM")
      (libsource (lib "eagle-import") (part "LED3MM"))
    )
    (comp (ref "LED867")
      (value "LED3MM")
      (footprint "eagle-import:LED_3MM")
      (libsource (lib "eagle-import") (part "LED3MM"))
    )
    (comp (ref "LED868")
      (value "LED3MM")
      (footprint "eagle-import:LED_3MM")
      (libsource (lib "eagle-import") (part "LED3MM"))
    )
    (comp (ref "LED869")
      (value "LED3MM")
      (footprint "eagle-import:LED_3MM")
      (libsource (lib "eagle-import") (part "LED3MM"))
    )
    (comp (ref "LED870")
      (value "LED3MM")
      (footprint "eagle-import:LED_3MM")
      (libsource (lib "eagle-import") (part "LED3MM"))
    )
    (comp (ref "LED871")
      (value "LED3MM")
      (footprint "eagle-import:LED_3MM")
      (libsource (lib "eagle-import") (part "LED3MM"))
    )
    (comp (ref "LED872")
      (value "LED3MM")
      (footprint "eagle-import:LED_3MM")
      (libsource (lib "eagle-import") (part "LED3MM"))
    )
    (comp (ref "LED873")
      (value "LED3MM")
      (footprint "eagle-import:LED_3MM")
      (libsource (lib "eagle-import") (part "LED3MM"))
    )
    (comp (ref "LED874")
      (value "LED3MM")
      (footprint "eagle-import:LED_3MM")
      (libsource (lib "eagle-import") (part "LED3MM"))
    )
    (comp (ref "LED875")
      (value "LED3MM")
      (footprint "eagle-import:LED_3MM")
      (libsource (lib "eagle-import") (part "LED3MM"))
    )
    (comp (ref "LED876")
      (value "LED3MM")
      (footprint "eagle-import:LED_3MM")
      (libsource (lib "eagle-import") (part "LED3MM"))
    )
    (comp (ref "LED877")
      (value "LED3MM")
      (footprint "eagle-import:LED_3MM")
      (libsource (lib "eagle-import") (part "LED3MM"))
    )
    (comp (ref "LED878")
      (value "LED3MM")
      (footprint "eagle-import:LED_3MM")
      (libsource (lib "eagle-import") (part "LED3MM"))
    )
    (comp (ref "LED879")
      (value "LED3MM")
      (footprint "eagle-import:LED_3MM")
      (libsource (lib "eagle-import") (part "LED3MM"))
    )
    (comp (ref "LED880")
      (value "LED3MM")
      (footprint "eagle-import:LED_3MM")
      (libsource (lib "eagle-import") (part "LED3MM"))
    )
    (comp (ref "LED881")
      (value "LED3MM")
      (footprint "eagle-import:LED_3MM")
      (libsource (lib "eagle-import") (part "LED3MM"))
    )
    (comp (ref "LED882")
      (value "LED3MM")
      (footprint "eagle-import:LED_3MM")
      (libsource (lib "eagle-import") (part "LED3MM"))
    )
    (comp (ref "LED883")
      (value "LED3MM")
      (footprint "eagle-import:LED_3MM")
      (libsource (lib "eagle-import") (part "LED3MM"))
    )
    (comp (ref "LED884")
      (value "LED3MM")
      (footprint "eagle-import:LED_3MM")
      (libsource (lib "eagle-import") (part "LED3MM"))
    )
    (comp (ref "LED885")
      (value "LED3MM")
      (footprint "eagle-import:LED_3MM")
      (libsource (lib "eagle-import") (part "LED3MM"))
    )
    (comp (ref "LED886")
      (value "LED3MM")
      (footprint "eagle-import:LED_3MM")
      (libsource (lib "eagle-import") (part "LED3MM"))
    )
    (comp (ref "LED887")
      (value "LED3MM")
      (footprint "eagle-import:LED_3MM")
      (libsource (lib "eagle-import") (part "LED3MM"))
    )
    (comp (ref "LED888")
      (value "LED3MM")
      (footprint "eagle-import:LED_3MM")
      (libsource (lib "eagle-import") (part "LED3MM"))
    )
    (comp (ref "LED889")
      (value "LED3MM")
      (footprint "eagle-import:LED_3MM")
      (libsource (lib "eagle-import") (part "LED3MM"))
    )
    (comp (ref "LED890")
      (value "LED3MM")
      (footprint "eagle-import:LED_3MM")
      (libsource (lib "eagle-import") (part "LED3MM"))
    )
    (comp (ref "LED891")
      (value "LED3MM")
      (footprint "eagle-import:LED_3MM")
      (libsource (lib "eagle-import") (part "LED3MM"))
    )
    (comp (ref "LED892")
      (value "LED3MM")
      (footprint "eagle-import:LED_3MM")
      (libsource (lib "eagle-import") (part "LED3MM"))
    )
    (comp (ref "LED893")
      (value "LED3MM")
      (footprint "eagle-import:LED_3MM")
      (libsource (lib "eagle-import") (part "LED3MM"))
    )
    (comp (ref "LED894")
      (value "LED3MM")
      (footprint "eagle-import:LED_3MM")
      (libsource (lib "eagle-import") (part "LED3MM"))
    )
    (comp (ref "LED895")
      (value "LED3MM")
      (footprint "eagle-import:LED_3MM")
      (libsource (lib "eagle-import") (part "LED3MM"))
    )
    (comp (ref "LED896")
      (value "LED3MM")
      (footprint "eagle-import:LED_3MM")
      (libsource (lib "eagle-import") (part "LED3MM"))
    )
    (comp (ref "LED897")
      (value "LED3MM")
      (footprint "eagle-import:LED_3MM")
      (libsource (lib "eagle-import") (part "LED3MM"))
    )
    (comp (ref "LED898")
      (value "LED3MM")
      (footprint "eagle-import:LED_3MM")
      (libsource (lib "eagle-import") (part "LED3MM"))
    )
    (comp (ref "LED899")
      (value "LED3MM")
      (footprint "eagle-import:LED_3MM")
      (libsource (lib "eagle-import") (part "LED3MM"))
    )
    (comp (ref "LED900")
      (value "LED3MM")
      (footprint "eagle-import:LED_3MM")
      (libsource (lib "eagle-import") (part "LED3MM"))
    )
    (comp (ref "LED901")
      (value "LED3MM")
      (footprint "eagle-import:LED_3MM")
      (libsource (lib "eagle-import") (part "LED3MM"))
    )
    (comp (ref "LED902")
      (value "LED3MM")
      (footprint "eagle-import:LED_3MM")
      (libsource (lib "eagle-import") (part "LED3MM"))
    )
    (comp (ref "LED903")
      (value "LED3MM")
      (footprint "eagle-import:LED_3MM")
      (libsource (lib "eagle-import") (part "LED3MM"))
    )
    (comp (ref "LED904")
      (value "LED3MM")
      (footprint "eagle-import:LED_3MM")
      (libsource (lib "eagle-import") (part "LED3MM"))
    )
    (comp (ref "LED905")
      (value "LED3MM")
      (footprint "eagle-import:LED_3MM")
      (libsource (lib "eagle-import") (part "LED3MM"))
    )
    (comp (ref "LED906")
      (value "LED3MM")
      (footprint "eagle-import:LED_3MM")
      (libsource (lib "eagle-import") (part "LED3MM"))
    )
    (comp (ref "LED907")
      (value "LED3MM")
      (footprint "eagle-import:LED_3MM")
      (libsource (lib "eagle-import") (part "LED3MM"))
    )
    (comp (ref "LED908")
      (value "LED3MM")
      (footprint "eagle-import:LED_3MM")
      (libsource (lib "eagle-import") (part "LED3MM"))
    )
    (comp (ref "LED909")
      (value "LED3MM")
      (footprint "eagle-import:LED_3MM")
      (libsource (lib "eagle-import") (part "LED3MM"))
    )
    (comp (ref "LED910")
      (value "LED3MM")
      (footprint "eagle-import:LED_3MM")
      (libsource (lib "eagle-import") (part "LED3MM"))
    )
    (comp (ref "LED911")
      (value "LED3MM")
      (footprint "eagle-import:LED_3MM")
      (libsource (lib "eagle-import") (part "LED3MM"))
    )
    (comp (ref "LED912")
      (value "LED3MM")
      (footprint "eagle-import:LED_3MM")
      (libsource (lib "eagle-import") (part "LED3MM"))
    )
    (comp (ref "LED913")
      (value "LED3MM")
      (footprint "eagle-import:LED_3MM")
      (libsource (lib "eagle-import") (part "LED3MM"))
    )
    (comp (ref "LED914")
      (value "LED3MM")
      (footprint "eagle-import:LED_3MM")
      (libsource (lib "eagle-import") (part "LED3MM"))
    )
    (comp (ref "LED915")
      (value "LED3MM")
      (footprint "eagle-import:LED_3MM")
      (libsource (lib "eagle-import") (part "LED3MM"))
    )
    (comp (ref "LED916")
      (value "LED3MM")
      (footprint "eagle-import:LED_3MM")
      (libsource (lib "eagle-import") (part "LED3MM"))
    )
    (comp (ref "LED917")
      (value "LED3MM")
      (footprint "eagle-import:LED_3MM")
      (libsource (lib "eagle-import") (part "LED3MM"))
    )
    (comp (ref "LED918")
      (value "LED3MM")
      (footprint "eagle-import:LED_3MM")
      (libsource (lib "eagle-import") (part "LED3MM"))
    )
    (comp (ref "LED919")
      (value "LED3MM")
      (footprint "eagle-import:LED_3MM")
      (libsource (lib "eagle-import") (part "LED3MM"))
    )
    (comp (ref "LED920")
      (value "LED3MM")
      (footprint "eagle-import:LED_3MM")
      (libsource (lib "eagle-import") (part "LED3MM"))
    )
    (comp (ref "LED921")
      (value "LED3MM")
      (footprint "eagle-import:LED_3MM")
      (libsource (lib "eagle-import") (part "LED3MM"))
    )
    (comp (ref "LED922")
      (value "LED3MM")
      (footprint "eagle-import:LED_3MM")
      (libsource (lib "eagle-import") (part "LED3MM"))
    )
    (comp (ref "LED923")
      (value "LED3MM")
      (footprint "eagle-import:LED_3MM")
      (libsource (lib "eagle-import") (part "LED3MM"))
    )
    (comp (ref "LED924")
      (value "LED3MM")
      (footprint "eagle-import:LED_3MM")
      (libsource (lib "eagle-import") (part "LED3MM"))
    )
    (comp (ref "LED925")
      (value "LED3MM")
      (footprint "eagle-import:LED_3MM")
      (libsource (lib "eagle-import") (part "LED3MM"))
    )
    (comp (ref "LED926")
      (value "LED3MM")
      (footprint "eagle-import:LED_3MM")
      (libsource (lib "eagle-import") (part "LED3MM"))
    )
    (comp (ref "LED927")
      (value "LED3MM")
      (footprint "eagle-import:LED_3MM")
      (libsource (lib "eagle-import") (part "LED3MM"))
    )
    (comp (ref "LED928")
      (value "LED3MM")
      (footprint "eagle-import:LED_3MM")
      (libsource (lib "eagle-import") (part "LED3MM"))
    )
    (comp (ref "LED929")
      (value "LED3MM")
      (footprint "eagle-import:LED_3MM")
      (libsource (lib "eagle-import") (part "LED3MM"))
    )
    (comp (ref "LED930")
      (value "LED3MM")
      (footprint "eagle-import:LED_3MM")
      (libsource (lib "eagle-import") (part "LED3MM"))
    )
    (comp (ref "LED931")
      (value "LED3MM")
      (footprint "eagle-import:LED_3MM")
      (libsource (lib "eagle-import") (part "LED3MM"))
    )
    (comp (ref "LED932")
      (value "LED3MM")
      (footprint "eagle-import:LED_3MM")
      (libsource (lib "eagle-import") (part "LED3MM"))
    )
    (comp (ref "LED933")
      (value "LED3MM")
      (footprint "eagle-import:LED_3MM")
      (libsource (lib "eagle-import") (part "LED3MM"))
    )
    (comp (ref "LED934")
      (value "LED3MM")
      (footprint "eagle-import:LED_3MM")
      (libsource (lib "eagle-import") (part "LED3MM"))
    )
    (comp (ref "LED935")
      (value "LED3MM")
      (footprint "eagle-import:LED_3MM")
      (libsource (lib "eagle-import") (part "LED3MM"))
    )
    (comp (ref "LED936")
      (value "LED3MM")
      (footprint "eagle-import:LED_3MM")
      (libsource (lib "eagle-import") (part "LED3MM"))
    )
    (comp (ref "LED937")
      (value "LED3MM")
      (footprint "eagle-import:LED_3MM")
      (libsource (lib "eagle-import") (part "LED3MM"))
    )
    (comp (ref "LED938")
      (value "LED3MM")
      (footprint "eagle-import:LED_3MM")
      (libsource (lib "eagle-import") (part "LED3MM"))
    )
    (comp (ref "LED939")
      (value "LED3MM")
      (footprint "eagle-import:LED_3MM")
      (libsource (lib "eagle-import") (part "LED3MM"))
    )
    (comp (ref "LED940")
      (value "LED3MM")
      (footprint "eagle-import:LED_3MM")
      (libsource (lib "eagle-import") (part "LED3MM"))
    )
    (comp (ref "LED941")
      (value "LED3MM")
      (footprint "eagle-import:LED_3MM")
      (libsource (lib "eagle-import") (part "LED3MM"))
    )
    (comp (ref "LED942")
      (value "LED3MM")
      (footprint "eagle-import:LED_3MM")
      (libsource (lib "eagle-import") (part "LED3MM"))
    )
    (comp (ref "LED943")
      (value "LED3MM")
      (footprint "eagle-import:LED_3MM")
      (libsource (lib "eagle-import") (part "LED3MM"))
    )
    (comp (ref "LED944")
      (value "LED3MM")
      (footprint "eagle-import:LED_3MM")
      (libsource (lib "eagle-import") (part "LED3MM"))
    )
    (comp (ref "LED945")
      (value "LED3MM")
      (footprint "eagle-import:LED_3MM")
      (libsource (lib "eagle-import") (part "LED3MM"))
    )
    (comp (ref "LED946")
      (value "LED3MM")
      (footprint "eagle-import:LED_3MM")
      (libsource (lib "eagle-import") (part "LED3MM"))
    )
    (comp (ref "LED947")
      (value "LED3MM")
      (footprint "eagle-import:LED_3MM")
      (libsource (lib "eagle-import") (part "LED3MM"))
    )
    (comp (ref "LED948")
      (value "LED3MM")
      (footprint "eagle-import:LED_3MM")
      (libsource (lib "eagle-import") (part "LED3MM"))
    )
    (comp (ref "LED949")
      (value "LED3MM")
      (footprint "eagle-import:LED_3MM")
      (libsource (lib "eagle-import") (part "LED3MM"))
    )
    (comp (ref "LED950")
      (value "LED3MM")
      (footprint "eagle-import:LED_3MM")
      (libsource (lib "eagle-import") (part "LED3MM"))
    )
    (comp (ref "LED951")
      (value "LED3MM")
      (footprint "eagle-import:LED_3MM")
      (libsource (lib "eagle-import") (part "LED3MM"))
    )
    (comp (ref "LED952")
      (value "LED3MM")
      (footprint "eagle-import:LED_3MM")
      (libsource (lib "eagle-import") (part "LED3MM"))
    )
    (comp (ref "LED953")
      (value "LED3MM")
      (footprint "eagle-import:LED_3MM")
      (libsource (lib "eagle-import") (part "LED3MM"))
    )
    (comp (ref "LED954")
      (value "LED3MM")
      (footprint "eagle-import:LED_3MM")
      (libsource (lib "eagle-import") (part "LED3MM"))
    )
    (comp (ref "LED955")
      (value "LED3MM")
      (footprint "eagle-import:LED_3MM")
      (libsource (lib "eagle-import") (part "LED3MM"))
    )
    (comp (ref "LED956")
      (value "LED3MM")
      (footprint "eagle-import:LED_3MM")
      (libsource (lib "eagle-import") (part "LED3MM"))
    )
    (comp (ref "LED957")
      (value "LED3MM")
      (footprint "eagle-import:LED_3MM")
      (libsource (lib "eagle-import") (part "LED3MM"))
    )
    (comp (ref "LED958")
      (value "LED3MM")
      (footprint "eagle-import:LED_3MM")
      (libsource (lib "eagle-import") (part "LED3MM"))
    )
    (comp (ref "LED959")
      (value "LED3MM")
      (footprint "eagle-import:LED_3MM")
      (libsource (lib "eagle-import") (part "LED3MM"))
    )
    (comp (ref "LED960")
      (value "LED3MM")
      (footprint "eagle-import:LED_3MM")
      (libsource (lib "eagle-import") (part "LED3MM"))
    )
    (comp (ref "LED961")
      (value "LED3MM")
      (footprint "eagle-import:LED_3MM")
      (libsource (lib "eagle-import") (part "LED3MM"))
    )
    (comp (ref "LED962")
      (value "LED3MM")
      (footprint "eagle-import:LED_3MM")
      (libsource (lib "eagle-import") (part "LED3MM"))
    )
    (comp (ref "LED963")
      (value "LED3MM")
      (footprint "eagle-import:LED_3MM")
      (libsource (lib "eagle-import") (part "LED3MM"))
    )
    (comp (ref "LED964")
      (value "LED3MM")
      (footprint "eagle-import:LED_3MM")
      (libsource (lib "eagle-import") (part "LED3MM"))
    )
    (comp (ref "LED965")
      (value "LED3MM")
      (footprint "eagle-import:LED_3MM")
      (libsource (lib "eagle-import") (part "LED3MM"))
    )
    (comp (ref "LED966")
      (value "LED3MM")
      (footprint "eagle-import:LED_3MM")
      (libsource (lib "eagle-import") (part "LED3MM"))
    )
    (comp (ref "LED967")
      (value "LED3MM")
      (footprint "eagle-import:LED_3MM")
      (libsource (lib "eagle-import") (part "LED3MM"))
    )
    (comp (ref "LED968")
      (value "LED3MM")
      (footprint "eagle-import:LED_3MM")
      (libsource (lib "eagle-import") (part "LED3MM"))
    )
    (comp (ref "LED969")
      (value "LED3MM")
      (footprint "eagle-import:LED_3MM")
      (libsource (lib "eagle-import") (part "LED3MM"))
    )
    (comp (ref "LED970")
      (value "LED3MM")
      (footprint "eagle-import:LED_3MM")
      (libsource (lib "eagle-import") (part "LED3MM"))
    )
    (comp (ref "LED971")
      (value "LED3MM")
      (footprint "eagle-import:LED_3MM")
      (libsource (lib "eagle-import") (part "LED3MM"))
    )
    (comp (ref "LED972")
      (value "LED3MM")
      (footprint "eagle-import:LED_3MM")
      (libsource (lib "eagle-import") (part "LED3MM"))
    )
    (comp (ref "LED973")
      (value "LED3MM")
      (footprint "eagle-import:LED_3MM")
      (libsource (lib "eagle-import") (part "LED3MM"))
    )
    (comp (ref "LED974")
      (value "LED3MM")
      (footprint "eagle-import:LED_3MM")
      (libsource (lib "eagle-import") (part "LED3MM"))
    )
    (comp (ref "LED975")
      (value "LED3MM")
      (footprint "eagle-import:LED_3MM")
      (libsource (lib "eagle-import") (part "LED3MM"))
    )
    (comp (ref "LED976")
      (value "LED3MM")
      (footprint "eagle-import:LED_3MM")
      (libsource (lib "eagle-import") (part "LED3MM"))
    )
    (comp (ref "LED977")
      (value "LED3MM")
      (footprint "eagle-import:LED_3MM")
      (libsource (lib "eagle-import") (part "LED3MM"))
    )
    (comp (ref "LED978")
      (value "LED3MM")
      (footprint "eagle-import:LED_3MM")
      (libsource (lib "eagle-import") (part "LED3MM"))
    )
    (comp (ref "LED979")
      (value "LED3MM")
      (footprint "eagle-import:LED_3MM")
      (libsource (lib "eagle-import") (part "LED3MM"))
    )
    (comp (ref "LED980")
      (value "LED3MM")
      (footprint "eagle-import:LED_3MM")
      (libsource (lib "eagle-import") (part "LED3MM"))
    )
    (comp (ref "LED981")
      (value "LED3MM")
      (footprint "eagle-import:LED_3MM")
      (libsource (lib "eagle-import") (part "LED3MM"))
    )
    (comp (ref "LED982")
      (value "LED3MM")
      (footprint "eagle-import:LED_3MM")
      (libsource (lib "eagle-import") (part "LED3MM"))
    )
    (comp (ref "LED983")
      (value "LED3MM")
      (footprint "eagle-import:LED_3MM")
      (libsource (lib "eagle-import") (part "LED3MM"))
    )
    (comp (ref "LED984")
      (value "LED3MM")
      (footprint "eagle-import:LED_3MM")
      (libsource (lib "eagle-import") (part "LED3MM"))
    )
    (comp (ref "LED985")
      (value "LED3MM")
      (footprint "eagle-import:LED_3MM")
      (libsource (lib "eagle-import") (part "LED3MM"))
    )
    (comp (ref "LED986")
      (value "LED3MM")
      (footprint "eagle-import:LED_3MM")
      (libsource (lib "eagle-import") (part "LED3MM"))
    )
    (comp (ref "LED987")
      (value "LED3MM")
      (footprint "eagle-import:LED_3MM")
      (libsource (lib "eagle-import") (part "LED3MM"))
    )
    (comp (ref "LED988")
      (value "LED3MM")
      (footprint "eagle-import:LED_3MM")
      (libsource (lib "eagle-import") (part "LED3MM"))
    )
    (comp (ref "LED989")
      (value "LED3MM")
      (footprint "eagle-import:LED_3MM")
      (libsource (lib "eagle-import") (part "LED3MM"))
    )
    (comp (ref "LED990")
      (value "LED3MM")
      (footprint "eagle-import:LED_3MM")
      (libsource (lib "eagle-import") (part "LED3MM"))
    )
    (comp (ref "LED991")
      (value "LED3MM")
      (footprint "eagle-import:LED_3MM")
      (libsource (lib "eagle-import") (part "LED3MM"))
    )
    (comp (ref "LED992")
      (value "LED3MM")
      (footprint "eagle-import:LED_3MM")
      (libsource (lib "eagle-import") (part "LED3MM"))
    )
    (comp (ref "LED993")
      (value "LED3MM")
      (footprint "eagle-import:LED_3MM")
      (libsource (lib "eagle-import") (part "LED3MM"))
    )
    (comp (ref "LED994")
      (value "LED3MM")
      (footprint "eagle-import:LED_3MM")
      (libsource (lib "eagle-import") (part "LED3MM"))
    )
    (comp (ref "LED995")
      (value "LED3MM")
      (footprint "eagle-import:LED_3MM")
      (libsource (lib "eagle-import") (part "LED3MM"))
    )
    (comp (ref "LED996")
      (value "LED3MM")
      (footprint "eagle-import:LED_3MM")
      (libsource (lib "eagle-import") (part "LED3MM"))
    )
    (comp (ref "LED997")
      (value "LED3MM")
      (footprint "eagle-import:LED_3MM")
      (libsource (lib "eagle-import") (part "LED3MM"))
    )
    (comp (ref "LED998")
      (value "LED3MM")
      (footprint "eagle-import:LED_3MM")
      (libsource (lib "eagle-import") (part "LED3MM"))
    )
    (comp (ref "LED999")
      (value "LED3MM")
      (footprint "eagle-import:LED_3MM")
      (libsource (lib "eagle-import") (part "LED3MM"))
    )
    (comp (ref "LED1000")
      (value "LED3MM")
      (footprint "eagle-import:LED_3MM")
      (libsource (lib "eagle-import") (part "LED3MM"))
    )
    (comp (ref "LED1001")
      (value "LED3MM")
      (footprint "eagle-import:LED_3MM")
      (libsource (lib "eagle-import") (part "LED3MM"))
    )
    (comp (ref "LED1002")
      (value "LED3MM")
      (footprint "eagle-import:LED_3MM")
      (libsource (lib "eagle-import") (part "LED3MM"))
    )
    (comp (ref "LED1003")
      (value "LED3MM")
      (footprint "eagle-import:LED_3MM")
      (libsource (lib "eagle-import") (part "LED3MM"))
    )
    (comp (ref "LED1004")
      (value "LED3MM")
      (footprint "eagle-import:LED_3MM")
      (libsource (lib "eagle-import") (part "LED3MM"))
    )
    (comp (ref "LED1005")
      (value "LED3MM")
      (footprint "eagle-import:LED_3MM")
      (libsource (lib "eagle-import") (part "LED3MM"))
    )
    (comp (ref "LED1006")
      (value "LED3MM")
      (footprint "eagle-import:LED_3MM")
      (libsource (lib "eagle-import") (part "LED3MM"))
    )
    (comp (ref "LED1007")
      (value "LED3MM")
      (footprint "eagle-import:LED_3MM")
      (libsource (lib "eagle-import") (part "LED3MM"))
    )
    (comp (ref "LED1008")
      (value "LED3MM")
      (footprint "eagle-import:LED_3MM")
      (libsource (lib "eagle-import") (part "LED3MM"))
    )
    (comp (ref "LED1009")
      (value "LED3MM")
      (footprint "eagle-import:LED_3MM")
      (libsource (lib "eagle-import") (part "LED3MM"))
    )
    (comp (ref "LED1010")
      (value "LED3MM")
      (footprint "eagle-import:LED_3MM")
      (libsource (lib "eagle-import") (part "LED3MM"))
    )
    (comp (ref "LED1011")
      (value "LED3MM")
      (footprint "eagle-import:LED_3MM")
      (libsource (lib "eagle-import") (part "LED3MM"))
    )
    (comp (ref "LED1012")
      (value "LED3MM")
      (footprint "eagle-import:LED_3MM")
      (libsource (lib "eagle-import") (part "LED3MM"))
    )
    (comp (ref "LED1013")
      (value "LED3MM")
      (footprint "eagle-import:LED_3MM")
      (libsource (lib "eagle-import") (part "LED3MM"))
    )
    (comp (ref "LED1014")
      (value "LED3MM")
      (footprint "eagle-import:LED_3MM")
      (libsource (lib "eagle-import") (part "LED3MM"))
    )
    (comp (ref "LED1015")
      (value "LED3MM")
      (footprint "eagle-import:LED_3MM")
      (libsource (lib "eagle-import") (part "LED3MM"))
    )
    (comp (ref "LED1016")
      (value "LED3MM")
      (footprint "eagle-import:LED_3MM")
      (libsource (lib "eagle-import") (part "LED3MM"))
    )
    (comp (ref "LED1017")
      (value "LED3MM")
      (footprint "eagle-import:LED_3MM")
      (libsource (lib "eagle-import") (part "LED3MM"))
    )
    (comp (ref "LED1018")
      (value "LED3MM")
      (footprint "eagle-import:LED_3MM")
      (libsource (lib "eagle-import") (part "LED3MM"))
    )
    (comp (ref "LED1019")
      (value "LED3MM")
      (footprint "eagle-import:LED_3MM")
      (libsource (lib "eagle-import") (part "LED3MM"))
    )
    (comp (ref "LED1020")
      (value "LED3MM")
      (footprint "eagle-import:LED_3MM")
      (libsource (lib "eagle-import") (part "LED3MM"))
    )
    (comp (ref "LED1021")
      (value "LED3MM")
      (footprint "eagle-import:LED_3MM")
      (libsource (lib "eagle-import") (part "LED3MM"))
    )
    (comp (ref "LED1022")
      (value "LED3MM")
      (footprint "eagle-import:LED_3MM")
      (libsource (lib "eagle-import") (part "LED3MM"))
    )
    (comp (ref "LED1023")
      (value "LED3MM")
      (footprint "eagle-import:LED_3MM")
      (libsource (lib "eagle-import") (part "LED3MM"))
    )
    (comp (ref "LED1024")
      (value "LED3MM")
      (footprint "eagle-import:LED_3MM")
      (libsource (lib "eagle-import") (part "LED3MM"))
    )
    (comp (ref "LED1025")
      (value "LED3MM")
      (footprint "eagle-import:LED_3MM")
      (libsource (lib "eagle-import") (part "LED3MM"))
    )
    (comp (ref "LED1026")
      (value "LED3MM")
      (footprint "eagle-import:LED_3MM")
      (libsource (lib "eagle-import") (part "LED3MM"))
    )
    (comp (ref "LED1027")
      (value "LED3MM")
      (footprint "eagle-import:LED_3MM")
      (libsource (lib "eagle-import") (part "LED3MM"))
    )
    (comp (ref "LED1028")
      (value "LED3MM")
      (footprint "eagle-import:LED_3MM")
      (libsource (lib "eagle-import") (part "LED3MM"))
    )
    (comp (ref "LED1029")
      (value "LED3MM")
      (footprint "eagle-import:LED_3MM")
      (libsource (lib "eagle-import") (part "LED3MM"))
    )
    (comp (ref "LED1030")
      (value "LED3MM")
      (footprint "eagle-import:LED_3MM")
      (libsource (lib "eagle-import") (part "LED3MM"))
    )
    (comp (ref "LED1031")
      (value "LED3MM")
      (footprint "eagle-import:LED_3MM")
      (libsource (lib "eagle-import") (part "LED3MM"))
    )
    (comp (ref "LED1032")
      (value "LED3MM")
      (footprint "eagle-import:LED_3MM")
      (libsource (lib "eagle-import") (part "LED3MM"))
    )
    (comp (ref "LED1033")
      (value "LED3MM")
      (footprint "eagle-import:LED_3MM")
      (libsource (lib "eagle-import") (part "LED3MM"))
    )
    (comp (ref "LED1034")
      (value "LED3MM")
      (footprint "eagle-import:LED_3MM")
      (libsource (lib "eagle-import") (part "LED3MM"))
    )
    (comp (ref "LED1035")
      (value "LED3MM")
      (footprint "eagle-import:LED_3MM")
      (libsource (lib "eagle-import") (part "LED3MM"))
    )
    (comp (ref "LED1036")
      (value "LED3MM")
      (footprint "eagle-import:LED_3MM")
      (libsource (lib "eagle-import") (part "LED3MM"))
    )
    (comp (ref "LED1037")
      (value "LED3MM")
      (footprint "eagle-import:LED_3MM")
      (libsource (lib "eagle-import") (part "LED3MM"))
    )
    (comp (ref "LED1038")
      (value "LED3MM")
      (footprint "eagle-import:LED_3MM")
      (libsource (lib "eagle-import") (part "LED3MM"))
    )
    (comp (ref "LED1039")
      (value "LED3MM")
      (footprint "eagle-import:LED_3MM")
      (libsource (lib "eagle-import") (part "LED3MM"))
    )
    (comp (ref "LED1040")
      (value "LED3MM")
      (footprint "eagle-import:LED_3MM")
      (libsource (lib "eagle-import") (part "LED3MM"))
    )
    (comp (ref "LED1041")
      (value "LED3MM")
      (footprint "eagle-import:LED_3MM")
      (libsource (lib "eagle-import") (part "LED3MM"))
    )
    (comp (ref "LED1042")
      (value "LED3MM")
      (footprint "eagle-import:LED_3MM")
      (libsource (lib "eagle-import") (part "LED3MM"))
    )
    (comp (ref "LED1043")
      (value "LED3MM")
      (footprint "eagle-import:LED_3MM")
      (libsource (lib "eagle-import") (part "LED3MM"))
    )
    (comp (ref "LED1044")
      (value "LED3MM")
      (footprint "eagle-import:LED_3MM")
      (libsource (lib "eagle-import") (part "LED3MM"))
    )
    (comp (ref "LED1045")
      (value "LED3MM")
      (footprint "eagle-import:LED_3MM")
      (libsource (lib "eagle-import") (part "LED3MM"))
    )
    (comp (ref "LED1046")
      (value "LED3MM")
      (footprint "eagle-import:LED_3MM")
      (libsource (lib "eagle-import") (part "LED3MM"))
    )
    (comp (ref "LED1047")
      (value "LED3MM")
      (footprint "eagle-import:LED_3MM")
      (libsource (lib "eagle-import") (part "LED3MM"))
    )
    (comp (ref "LED1048")
      (value "LED3MM")
      (footprint "eagle-import:LED_3MM")
      (libsource (lib "eagle-import") (part "LED3MM"))
    )
    (comp (ref "LED1049")
      (value "LED3MM")
      (footprint "eagle-import:LED_3MM")
      (libsource (lib "eagle-import") (part "LED3MM"))
    )
    (comp (ref "LED1050")
      (value "LED3MM")
      (footprint "eagle-import:LED_3MM")
      (libsource (lib "eagle-import") (part "LED3MM"))
    )
    (comp (ref "LED1051")
      (value "LED3MM")
      (footprint "eagle-import:LED_3MM")
      (libsource (lib "eagle-import") (part "LED3MM"))
    )
    (comp (ref "LED1052")
      (value "LED3MM")
      (footprint "eagle-import:LED_3MM")
      (libsource (lib "eagle-import") (part "LED3MM"))
    )
    (comp (ref "LED1053")
      (value "LED3MM")
      (footprint "eagle-import:LED_3MM")
      (libsource (lib "eagle-import") (part "LED3MM"))
    )
    (comp (ref "U$1")
      (value "39COLUMN")
      (footprint "eagle-import:COLUMNS")
      (libsource (lib "eagle-import") (part "39COLUMN"))
    )
    (comp (ref "U$2")
      (value "39COLUMN")
      (footprint "eagle-import:COLUMNS")
      (libsource (lib "eagle-import") (part "39COLUMN"))
    )
    (comp (ref "U$3")
      (value "9ROW")
      (footprint "eagle-import:ROWS")
      (libsource (lib "eagle-import") (part "9ROW"))
    )
    (comp (ref "U$4")
      (value "9ROW")
      (footprint "eagle-import:ROWS")
      (libsource (lib "eagle-import") (part "9ROW"))
    )
  )
  (nets
    (net (code "1") (name "Net-(LED1-C)") (class "Default")
      (node (ref "LED1") (pin "K") (pinfunction "C_K") (pintype "passive"))
      (node (ref "LED313") (pin "K") (pinfunction "C_K") (pintype "passive"))
      (node (ref "LED314") (pin "K") (pinfunction "C_K") (pintype "passive"))
      (node (ref "LED315") (pin "K") (pinfunction "C_K") (pintype "passive"))
      (node (ref "LED316") (pin "K") (pinfunction "C_K") (pintype "passive"))
      (node (ref "LED317") (pin "K") (pinfunction "C_K") (pintype "passive"))
      (node (ref "LED318") (pin "K") (pinfunction "C_K") (pintype "passive"))
      (node (ref "LED319") (pin "K") (pinfunction "C_K") (pintype "passive"))
      (node (ref "LED320") (pin "K") (pinfunction "C_K") (pintype "passive"))
      (node (ref "U$1") (pin "P$39") (pinfunction "P$39_P$39") (pintype "bidirectional"))
    )
    (net (code "2") (name "Net-(LED1-PadA)") (class "Default")
      (node (ref "LED1") (pin "A") (pinfunction "A_A") (pintype "passive"))
      (node (ref "LED10") (pin "A") (pinfunction "A_A") (pintype "passive"))
      (node (ref "LED11") (pin "A") (pinfunction "A_A") (pintype "passive"))
      (node (ref "LED12") (pin "A") (pinfunction "A_A") (pintype "passive"))
      (node (ref "LED13") (pin "A") (pinfunction "A_A") (pintype "passive"))
      (node (ref "LED14") (pin "A") (pinfunction "A_A") (pintype "passive"))
      (node (ref "LED15") (pin "A") (pinfunction "A_A") (pintype "passive"))
      (node (ref "LED16") (pin "A") (pinfunction "A_A") (pintype "passive"))
      (node (ref "LED17") (pin "A") (pinfunction "A_A") (pintype "passive"))
      (node (ref "LED18") (pin "A") (pinfunction "A_A") (pintype "passive"))
      (node (ref "LED19") (pin "A") (pinfunction "A_A") (pintype "passive"))
      (node (ref "LED2") (pin "A") (pinfunction "A_A") (pintype "passive"))
      (node (ref "LED20") (pin "A") (pinfunction "A_A") (pintype "passive"))
      (node (ref "LED21") (pin "A") (pinfunction "A_A") (pintype "passive"))
      (node (ref "LED22") (pin "A") (pinfunction "A_A") (pintype "passive"))
      (node (ref "LED23") (pin "A") (pinfunction "A_A") (pintype "passive"))
      (node (ref "LED24") (pin "A") (pinfunction "A_A") (pintype "passive"))
      (node (ref "LED25") (pin "A") (pinfunction "A_A") (pintype "passive"))
      (node (ref "LED26") (pin "A") (pinfunction "A_A") (pintype "passive"))
      (node (ref "LED27") (pin "A") (pinfunction "A_A") (pintype "passive"))
      (node (ref "LED28") (pin "A") (pinfunction "A_A") (pintype "passive"))
      (node (ref "LED29") (pin "A") (pinfunction "A_A") (pintype "passive"))
      (node (ref "LED3") (pin "A") (pinfunction "A_A") (pintype "passive"))
      (node (ref "LED30") (pin "A") (pinfunction "A_A") (pintype "passive"))
      (node (ref "LED31") (pin "A") (pinfunction "A_A") (pintype "passive"))
      (node (ref "LED32") (pin "A") (pinfunction "A_A") (pintype "passive"))
      (node (ref "LED33") (pin "A") (pinfunction "A_A") (pintype "passive"))
      (node (ref "LED34") (pin "A") (pinfunction "A_A") (pintype "passive"))
      (node (ref "LED35") (pin "A") (pinfunction "A_A") (pintype "passive"))
      (node (ref "LED36") (pin "A") (pinfunction "A_A") (pintype "passive"))
      (node (ref "LED37") (pin "A") (pinfunction "A_A") (pintype "passive"))
      (node (ref "LED38") (pin "A") (pinfunction "A_A") (pintype "passive"))
      (node (ref "LED39") (pin "A") (pinfunction "A_A") (pintype "passive"))
      (node (ref "LED4") (pin "A") (pinfunction "A_A") (pintype "passive"))
      (node (ref "LED5") (pin "A") (pinfunction "A_A") (pintype "passive"))
      (node (ref "LED6") (pin "A") (pinfunction "A_A") (pintype "passive"))
      (node (ref "LED7") (pin "A") (pinfunction "A_A") (pintype "passive"))
      (node (ref "LED8") (pin "A") (pinfunction "A_A") (pintype "passive"))
      (node (ref "LED9") (pin "A") (pinfunction "A_A") (pintype "passive"))
      (node (ref "U$4") (pin "P$9") (pinfunction "P$9_P$9") (pintype "bidirectional"))
    )
    (net (code "3") (name "Net-(LED2-C)") (class "Default")
      (node (ref "LED2") (pin "K") (pinfunction "C_K") (pintype "passive"))
      (node (ref "LED321") (pin "K") (pinfunction "C_K") (pintype "passive"))
      (node (ref "LED322") (pin "K") (pinfunction "C_K") (pintype "passive"))
      (node (ref "LED323") (pin "K") (pinfunction "C_K") (pintype "passive"))
      (node (ref "LED324") (pin "K") (pinfunction "C_K") (pintype "passive"))
      (node (ref "LED325") (pin "K") (pinfunction "C_K") (pintype "passive"))
      (node (ref "LED326") (pin "K") (pinfunction "C_K") (pintype "passive"))
      (node (ref "LED327") (pin "K") (pinfunction "C_K") (pintype "passive"))
      (node (ref "LED328") (pin "K") (pinfunction "C_K") (pintype "passive"))
      (node (ref "U$1") (pin "P$38") (pinfunction "P$38_P$38") (pintype "bidirectional"))
    )
    (net (code "4") (name "Net-(LED3-C)") (class "Default")
      (node (ref "LED3") (pin "K") (pinfunction "C_K") (pintype "passive"))
      (node (ref "LED329") (pin "K") (pinfunction "C_K") (pintype "passive"))
      (node (ref "LED330") (pin "K") (pinfunction "C_K") (pintype "passive"))
      (node (ref "LED331") (pin "K") (pinfunction "C_K") (pintype "passive"))
      (node (ref "LED332") (pin "K") (pinfunction "C_K") (pintype "passive"))
      (node (ref "LED333") (pin "K") (pinfunction "C_K") (pintype "passive"))
      (node (ref "LED334") (pin "K") (pinfunction "C_K") (pintype "passive"))
      (node (ref "LED335") (pin "K") (pinfunction "C_K") (pintype "passive"))
      (node (ref "LED336") (pin "K") (pinfunction "C_K") (pintype "passive"))
      (node (ref "U$1") (pin "P$37") (pinfunction "P$37_P$37") (pintype "bidirectional"))
    )
    (net (code "5") (name "Net-(LED10-C)") (class "Default")
      (node (ref "LED10") (pin "K") (pinfunction "C_K") (pintype "passive"))
      (node (ref "LED385") (pin "K") (pinfunction "C_K") (pintype "passive"))
      (node (ref "LED386") (pin "K") (pinfunction "C_K") (pintype "passive"))
      (node (ref "LED387") (pin "K") (pinfunction "C_K") (pintype "passive"))
      (node (ref "LED388") (pin "K") (pinfunction "C_K") (pintype "passive"))
      (node (ref "LED389") (pin "K") (pinfunction "C_K") (pintype "passive"))
      (node (ref "LED390") (pin "K") (pinfunction "C_K") (pintype "passive"))
      (node (ref "LED391") (pin "K") (pinfunction "C_K") (pintype "passive"))
      (node (ref "LED392") (pin "K") (pinfunction "C_K") (pintype "passive"))
      (node (ref "U$1") (pin "P$30") (pinfunction "P$30_P$30") (pintype "bidirectional"))
    )
    (net (code "6") (name "Net-(LED11-C)") (class "Default")
      (node (ref "LED11") (pin "K") (pinfunction "C_K") (pintype "passive"))
      (node (ref "LED393") (pin "K") (pinfunction "C_K") (pintype "passive"))
      (node (ref "LED394") (pin "K") (pinfunction "C_K") (pintype "passive"))
      (node (ref "LED395") (pin "K") (pinfunction "C_K") (pintype "passive"))
      (node (ref "LED396") (pin "K") (pinfunction "C_K") (pintype "passive"))
      (node (ref "LED397") (pin "K") (pinfunction "C_K") (pintype "passive"))
      (node (ref "LED398") (pin "K") (pinfunction "C_K") (pintype "passive"))
      (node (ref "LED399") (pin "K") (pinfunction "C_K") (pintype "passive"))
      (node (ref "LED400") (pin "K") (pinfunction "C_K") (pintype "passive"))
      (node (ref "U$1") (pin "P$29") (pinfunction "P$29_P$29") (pintype "bidirectional"))
    )
    (net (code "7") (name "Net-(LED12-C)") (class "Default")
      (node (ref "LED12") (pin "K") (pinfunction "C_K") (pintype "passive"))
      (node (ref "LED401") (pin "K") (pinfunction "C_K") (pintype "passive"))
      (node (ref "LED402") (pin "K") (pinfunction "C_K") (pintype "passive"))
      (node (ref "LED403") (pin "K") (pinfunction "C_K") (pintype "passive"))
      (node (ref "LED404") (pin "K") (pinfunction "C_K") (pintype "passive"))
      (node (ref "LED405") (pin "K") (pinfunction "C_K") (pintype "passive"))
      (node (ref "LED406") (pin "K") (pinfunction "C_K") (pintype "passive"))
      (node (ref "LED407") (pin "K") (pinfunction "C_K") (pintype "passive"))
      (node (ref "LED408") (pin "K") (pinfunction "C_K") (pintype "passive"))
    )
    (net (code "8") (name "Net-(LED13-C)") (class "Default")
      (node (ref "LED13") (pin "K") (pinfunction "C_K") (pintype "passive"))
      (node (ref "LED409") (pin "K") (pinfunction "C_K") (pintype "passive"))
      (node (ref "LED410") (pin "K") (pinfunction "C_K") (pintype "passive"))
      (node (ref "LED411") (pin "K") (pinfunction "C_K") (pintype "passive"))
      (node (ref "LED412") (pin "K") (pinfunction "C_K") (pintype "passive"))
      (node (ref "LED413") (pin "K") (pinfunction "C_K") (pintype "passive"))
      (node (ref "LED414") (pin "K") (pinfunction "C_K") (pintype "passive"))
      (node (ref "LED415") (pin "K") (pinfunction "C_K") (pintype "passive"))
      (node (ref "LED416") (pin "K") (pinfunction "C_K") (pintype "passive"))
      (node (ref "U$1") (pin "P$27") (pinfunction "P$27_P$27") (pintype "bidirectional"))
    )
    (net (code "9") (name "Net-(LED14-C)") (class "Default")
      (node (ref "LED14") (pin "K") (pinfunction "C_K") (pintype "passive"))
      (node (ref "LED417") (pin "K") (pinfunction "C_K") (pintype "passive"))
      (node (ref "LED418") (pin "K") (pinfunction "C_K") (pintype "passive"))
      (node (ref "LED419") (pin "K") (pinfunction "C_K") (pintype "passive"))
      (node (ref "LED420") (pin "K") (pinfunction "C_K") (pintype "passive"))
      (node (ref "LED421") (pin "K") (pinfunction "C_K") (pintype "passive"))
      (node (ref "LED422") (pin "K") (pinfunction "C_K") (pintype "passive"))
      (node (ref "LED423") (pin "K") (pinfunction "C_K") (pintype "passive"))
      (node (ref "LED424") (pin "K") (pinfunction "C_K") (pintype "passive"))
      (node (ref "U$1") (pin "P$26") (pinfunction "P$26_P$26") (pintype "bidirectional"))
    )
    (net (code "10") (name "Net-(LED15-C)") (class "Default")
      (node (ref "LED15") (pin "K") (pinfunction "C_K") (pintype "passive"))
      (node (ref "LED425") (pin "K") (pinfunction "C_K") (pintype "passive"))
      (node (ref "LED426") (pin "K") (pinfunction "C_K") (pintype "passive"))
      (node (ref "LED427") (pin "K") (pinfunction "C_K") (pintype "passive"))
      (node (ref "LED428") (pin "K") (pinfunction "C_K") (pintype "passive"))
      (node (ref "LED429") (pin "K") (pinfunction "C_K") (pintype "passive"))
      (node (ref "LED430") (pin "K") (pinfunction "C_K") (pintype "passive"))
      (node (ref "LED431") (pin "K") (pinfunction "C_K") (pintype "passive"))
      (node (ref "LED432") (pin "K") (pinfunction "C_K") (pintype "passive"))
      (node (ref "U$1") (pin "P$25") (pinfunction "P$25_P$25") (pintype "bidirectional"))
    )
    (net (code "11") (name "Net-(LED16-C)") (class "Default")
      (node (ref "LED16") (pin "K") (pinfunction "C_K") (pintype "passive"))
      (node (ref "LED433") (pin "K") (pinfunction "C_K") (pintype "passive"))
      (node (ref "LED434") (pin "K") (pinfunction "C_K") (pintype "passive"))
      (node (ref "LED435") (pin "K") (pinfunction "C_K") (pintype "passive"))
      (node (ref "LED436") (pin "K") (pinfunction "C_K") (pintype "passive"))
      (node (ref "LED437") (pin "K") (pinfunction "C_K") (pintype "passive"))
      (node (ref "LED438") (pin "K") (pinfunction "C_K") (pintype "passive"))
      (node (ref "LED439") (pin "K") (pinfunction "C_K") (pintype "passive"))
      (node (ref "LED440") (pin "K") (pinfunction "C_K") (pintype "passive"))
      (node (ref "U$1") (pin "P$24") (pinfunction "P$24_P$24") (pintype "bidirectional"))
    )
    (net (code "12") (name "Net-(LED17-C)") (class "Default")
      (node (ref "LED17") (pin "K") (pinfunction "C_K") (pintype "passive"))
      (node (ref "LED441") (pin "K") (pinfunction "C_K") (pintype "passive"))
      (node (ref "LED442") (pin "K") (pinfunction "C_K") (pintype "passive"))
      (node (ref "LED443") (pin "K") (pinfunction "C_K") (pintype "passive"))
      (node (ref "LED444") (pin "K") (pinfunction "C_K") (pintype "passive"))
      (node (ref "LED445") (pin "K") (pinfunction "C_K") (pintype "passive"))
      (node (ref "LED446") (pin "K") (pinfunction "C_K") (pintype "passive"))
      (node (ref "LED447") (pin "K") (pinfunction "C_K") (pintype "passive"))
      (node (ref "LED448") (pin "K") (pinfunction "C_K") (pintype "passive"))
      (node (ref "U$1") (pin "P$23") (pinfunction "P$23_P$23") (pintype "bidirectional"))
    )
    (net (code "13") (name "Net-(LED18-C)") (class "Default")
      (node (ref "LED18") (pin "K") (pinfunction "C_K") (pintype "passive"))
      (node (ref "LED449") (pin "K") (pinfunction "C_K") (pintype "passive"))
      (node (ref "LED450") (pin "K") (pinfunction "C_K") (pintype "passive"))
      (node (ref "LED451") (pin "K") (pinfunction "C_K") (pintype "passive"))
      (node (ref "LED452") (pin "K") (pinfunction "C_K") (pintype "passive"))
      (node (ref "LED453") (pin "K") (pinfunction "C_K") (pintype "passive"))
      (node (ref "LED454") (pin "K") (pinfunction "C_K") (pintype "passive"))
      (node (ref "LED455") (pin "K") (pinfunction "C_K") (pintype "passive"))
      (node (ref "LED456") (pin "K") (pinfunction "C_K") (pintype "passive"))
      (node (ref "U$1") (pin "P$22") (pinfunction "P$22_P$22") (pintype "bidirectional"))
    )
    (net (code "14") (name "Net-(LED19-C)") (class "Default")
      (node (ref "LED19") (pin "K") (pinfunction "C_K") (pintype "passive"))
      (node (ref "LED457") (pin "K") (pinfunction "C_K") (pintype "passive"))
      (node (ref "LED458") (pin "K") (pinfunction "C_K") (pintype "passive"))
      (node (ref "LED459") (pin "K") (pinfunction "C_K") (pintype "passive"))
      (node (ref "LED460") (pin "K") (pinfunction "C_K") (pintype "passive"))
      (node (ref "LED461") (pin "K") (pinfunction "C_K") (pintype "passive"))
      (node (ref "LED462") (pin "K") (pinfunction "C_K") (pintype "passive"))
      (node (ref "LED463") (pin "K") (pinfunction "C_K") (pintype "passive"))
      (node (ref "LED464") (pin "K") (pinfunction "C_K") (pintype "passive"))
      (node (ref "U$1") (pin "P$21") (pinfunction "P$21_P$21") (pintype "bidirectional"))
    )
    (net (code "15") (name "Net-(LED20-C)") (class "Default")
      (node (ref "LED20") (pin "K") (pinfunction "C_K") (pintype "passive"))
      (node (ref "LED465") (pin "K") (pinfunction "C_K") (pintype "passive"))
      (node (ref "LED466") (pin "K") (pinfunction "C_K") (pintype "passive"))
      (node (ref "LED467") (pin "K") (pinfunction "C_K") (pintype "passive"))
      (node (ref "LED468") (pin "K") (pinfunction "C_K") (pintype "passive"))
      (node (ref "LED469") (pin "K") (pinfunction "C_K") (pintype "passive"))
      (node (ref "LED470") (pin "K") (pinfunction "C_K") (pintype "passive"))
      (node (ref "LED471") (pin "K") (pinfunction "C_K") (pintype "passive"))
      (node (ref "LED472") (pin "K") (pinfunction "C_K") (pintype "passive"))
      (node (ref "U$1") (pin "P$20") (pinfunction "P$20_P$20") (pintype "bidirectional"))
    )
    (net (code "16") (name "Net-(LED21-C)") (class "Default")
      (node (ref "LED21") (pin "K") (pinfunction "C_K") (pintype "passive"))
      (node (ref "LED473") (pin "K") (pinfunction "C_K") (pintype "passive"))
      (node (ref "LED474") (pin "K") (pinfunction "C_K") (pintype "passive"))
      (node (ref "LED475") (pin "K") (pinfunction "C_K") (pintype "passive"))
      (node (ref "LED476") (pin "K") (pinfunction "C_K") (pintype "passive"))
      (node (ref "LED477") (pin "K") (pinfunction "C_K") (pintype "passive"))
      (node (ref "LED478") (pin "K") (pinfunction "C_K") (pintype "passive"))
      (node (ref "LED479") (pin "K") (pinfunction "C_K") (pintype "passive"))
      (node (ref "LED480") (pin "K") (pinfunction "C_K") (pintype "passive"))
      (node (ref "U$1") (pin "P$19") (pinfunction "P$19_P$19") (pintype "bidirectional"))
    )
    (net (code "17") (name "Net-(LED22-C)") (class "Default")
      (node (ref "LED22") (pin "K") (pinfunction "C_K") (pintype "passive"))
      (node (ref "LED481") (pin "K") (pinfunction "C_K") (pintype "passive"))
      (node (ref "LED482") (pin "K") (pinfunction "C_K") (pintype "passive"))
      (node (ref "LED483") (pin "K") (pinfunction "C_K") (pintype "passive"))
      (node (ref "LED484") (pin "K") (pinfunction "C_K") (pintype "passive"))
      (node (ref "LED485") (pin "K") (pinfunction "C_K") (pintype "passive"))
      (node (ref "LED486") (pin "K") (pinfunction "C_K") (pintype "passive"))
      (node (ref "LED487") (pin "K") (pinfunction "C_K") (pintype "passive"))
      (node (ref "LED488") (pin "K") (pinfunction "C_K") (pintype "passive"))
      (node (ref "U$1") (pin "P$18") (pinfunction "P$18_P$18") (pintype "bidirectional"))
    )
    (net (code "18") (name "Net-(LED23-C)") (class "Default")
      (node (ref "LED23") (pin "K") (pinfunction "C_K") (pintype "passive"))
      (node (ref "LED489") (pin "K") (pinfunction "C_K") (pintype "passive"))
      (node (ref "LED490") (pin "K") (pinfunction "C_K") (pintype "passive"))
      (node (ref "LED491") (pin "K") (pinfunction "C_K") (pintype "passive"))
      (node (ref "LED492") (pin "K") (pinfunction "C_K") (pintype "passive"))
      (node (ref "LED493") (pin "K") (pinfunction "C_K") (pintype "passive"))
      (node (ref "LED494") (pin "K") (pinfunction "C_K") (pintype "passive"))
      (node (ref "LED495") (pin "K") (pinfunction "C_K") (pintype "passive"))
      (node (ref "LED496") (pin "K") (pinfunction "C_K") (pintype "passive"))
      (node (ref "U$1") (pin "P$17") (pinfunction "P$17_P$17") (pintype "bidirectional"))
    )
    (net (code "19") (name "Net-(LED24-C)") (class "Default")
      (node (ref "LED24") (pin "K") (pinfunction "C_K") (pintype "passive"))
      (node (ref "LED497") (pin "K") (pinfunction "C_K") (pintype "passive"))
      (node (ref "LED498") (pin "K") (pinfunction "C_K") (pintype "passive"))
      (node (ref "LED499") (pin "K") (pinfunction "C_K") (pintype "passive"))
      (node (ref "LED500") (pin "K") (pinfunction "C_K") (pintype "passive"))
      (node (ref "LED501") (pin "K") (pinfunction "C_K") (pintype "passive"))
      (node (ref "LED502") (pin "K") (pinfunction "C_K") (pintype "passive"))
      (node (ref "LED503") (pin "K") (pinfunction "C_K") (pintype "passive"))
      (node (ref "LED504") (pin "K") (pinfunction "C_K") (pintype "passive"))
      (node (ref "U$1") (pin "P$16") (pinfunction "P$16_P$16") (pintype "bidirectional"))
    )
    (net (code "20") (name "Net-(LED25-C)") (class "Default")
      (node (ref "LED25") (pin "K") (pinfunction "C_K") (pintype "passive"))
      (node (ref "LED505") (pin "K") (pinfunction "C_K") (pintype "passive"))
      (node (ref "LED506") (pin "K") (pinfunction "C_K") (pintype "passive"))
      (node (ref "LED507") (pin "K") (pinfunction "C_K") (pintype "passive"))
      (node (ref "LED508") (pin "K") (pinfunction "C_K") (pintype "passive"))
      (node (ref "LED509") (pin "K") (pinfunction "C_K") (pintype "passive"))
      (node (ref "LED510") (pin "K") (pinfunction "C_K") (pintype "passive"))
      (node (ref "LED511") (pin "K") (pinfunction "C_K") (pintype "passive"))
      (node (ref "LED512") (pin "K") (pinfunction "C_K") (pintype "passive"))
      (node (ref "U$1") (pin "P$15") (pinfunction "P$15_P$15") (pintype "bidirectional"))
    )
    (net (code "21") (name "Net-(LED26-C)") (class "Default")
      (node (ref "LED26") (pin "K") (pinfunction "C_K") (pintype "passive"))
      (node (ref "LED513") (pin "K") (pinfunction "C_K") (pintype "passive"))
      (node (ref "LED514") (pin "K") (pinfunction "C_K") (pintype "passive"))
      (node (ref "LED515") (pin "K") (pinfunction "C_K") (pintype "passive"))
      (node (ref "LED516") (pin "K") (pinfunction "C_K") (pintype "passive"))
      (node (ref "LED517") (pin "K") (pinfunction "C_K") (pintype "passive"))
      (node (ref "LED518") (pin "K") (pinfunction "C_K") (pintype "passive"))
      (node (ref "LED519") (pin "K") (pinfunction "C_K") (pintype "passive"))
      (node (ref "LED520") (pin "K") (pinfunction "C_K") (pintype "passive"))
      (node (ref "U$1") (pin "P$14") (pinfunction "P$14_P$14") (pintype "bidirectional"))
    )
    (net (code "22") (name "Net-(LED27-C)") (class "Default")
      (node (ref "LED27") (pin "K") (pinfunction "C_K") (pintype "passive"))
      (node (ref "LED521") (pin "K") (pinfunction "C_K") (pintype "passive"))
      (node (ref "LED522") (pin "K") (pinfunction "C_K") (pintype "passive"))
      (node (ref "LED523") (pin "K") (pinfunction "C_K") (pintype "passive"))
      (node (ref "LED524") (pin "K") (pinfunction "C_K") (pintype "passive"))
      (node (ref "LED525") (pin "K") (pinfunction "C_K") (pintype "passive"))
      (node (ref "LED526") (pin "K") (pinfunction "C_K") (pintype "passive"))
      (node (ref "LED527") (pin "K") (pinfunction "C_K") (pintype "passive"))
      (node (ref "LED528") (pin "K") (pinfunction "C_K") (pintype "passive"))
      (node (ref "U$1") (pin "P$13") (pinfunction "P$13_P$13") (pintype "bidirectional"))
    )
    (net (code "23") (name "Net-(LED28-C)") (class "Default")
      (node (ref "LED28") (pin "K") (pinfunction "C_K") (pintype "passive"))
      (node (ref "LED529") (pin "K") (pinfunction "C_K") (pintype "passive"))
      (node (ref "LED530") (pin "K") (pinfunction "C_K") (pintype "passive"))
      (node (ref "LED531") (pin "K") (pinfunction "C_K") (pintype "passive"))
      (node (ref "LED532") (pin "K") (pinfunction "C_K") (pintype "passive"))
      (node (ref "LED533") (pin "K") (pinfunction "C_K") (pintype "passive"))
      (node (ref "LED534") (pin "K") (pinfunction "C_K") (pintype "passive"))
      (node (ref "LED535") (pin "K") (pinfunction "C_K") (pintype "passive"))
      (node (ref "LED536") (pin "K") (pinfunction "C_K") (pintype "passive"))
      (node (ref "U$1") (pin "P$12") (pinfunction "P$12_P$12") (pintype "bidirectional"))
    )
    (net (code "24") (name "Net-(LED29-C)") (class "Default")
      (node (ref "LED29") (pin "K") (pinfunction "C_K") (pintype "passive"))
      (node (ref "LED537") (pin "K") (pinfunction "C_K") (pintype "passive"))
      (node (ref "LED538") (pin "K") (pinfunction "C_K") (pintype "passive"))
      (node (ref "LED539") (pin "K") (pinfunction "C_K") (pintype "passive"))
      (node (ref "LED540") (pin "K") (pinfunction "C_K") (pintype "passive"))
      (node (ref "LED541") (pin "K") (pinfunction "C_K") (pintype "passive"))
      (node (ref "LED542") (pin "K") (pinfunction "C_K") (pintype "passive"))
      (node (ref "LED543") (pin "K") (pinfunction "C_K") (pintype "passive"))
      (node (ref "LED544") (pin "K") (pinfunction "C_K") (pintype "passive"))
      (node (ref "U$1") (pin "P$11") (pinfunction "P$11_P$11") (pintype "bidirectional"))
    )
    (net (code "25") (name "Net-(LED30-C)") (class "Default")
      (node (ref "LED30") (pin "K") (pinfunction "C_K") (pintype "passive"))
      (node (ref "LED545") (pin "K") (pinfunction "C_K") (pintype "passive"))
      (node (ref "LED546") (pin "K") (pinfunction "C_K") (pintype "passive"))
      (node (ref "LED547") (pin "K") (pinfunction "C_K") (pintype "passive"))
      (node (ref "LED548") (pin "K") (pinfunction "C_K") (pintype "passive"))
      (node (ref "LED549") (pin "K") (pinfunction "C_K") (pintype "passive"))
      (node (ref "LED550") (pin "K") (pinfunction "C_K") (pintype "passive"))
      (node (ref "LED551") (pin "K") (pinfunction "C_K") (pintype "passive"))
      (node (ref "LED552") (pin "K") (pinfunction "C_K") (pintype "passive"))
      (node (ref "U$1") (pin "P$10") (pinfunction "P$10_P$10") (pintype "bidirectional"))
    )
    (net (code "26") (name "Net-(LED31-C)") (class "Default")
      (node (ref "LED31") (pin "K") (pinfunction "C_K") (pintype "passive"))
      (node (ref "LED553") (pin "K") (pinfunction "C_K") (pintype "passive"))
      (node (ref "LED554") (pin "K") (pinfunction "C_K") (pintype "passive"))
      (node (ref "LED555") (pin "K") (pinfunction "C_K") (pintype "passive"))
      (node (ref "LED556") (pin "K") (pinfunction "C_K") (pintype "passive"))
      (node (ref "LED557") (pin "K") (pinfunction "C_K") (pintype "passive"))
      (node (ref "LED558") (pin "K") (pinfunction "C_K") (pintype "passive"))
      (node (ref "LED559") (pin "K") (pinfunction "C_K") (pintype "passive"))
      (node (ref "LED560") (pin "K") (pinfunction "C_K") (pintype "passive"))
      (node (ref "U$1") (pin "P$9") (pinfunction "P$9_P$9") (pintype "bidirectional"))
    )
    (net (code "27") (name "Net-(LED32-C)") (class "Default")
      (node (ref "LED32") (pin "K") (pinfunction "C_K") (pintype "passive"))
      (node (ref "LED561") (pin "K") (pinfunction "C_K") (pintype "passive"))
      (node (ref "LED562") (pin "K") (pinfunction "C_K") (pintype "passive"))
      (node (ref "LED563") (pin "K") (pinfunction "C_K") (pintype "passive"))
      (node (ref "LED564") (pin "K") (pinfunction "C_K") (pintype "passive"))
      (node (ref "LED565") (pin "K") (pinfunction "C_K") (pintype "passive"))
      (node (ref "LED566") (pin "K") (pinfunction "C_K") (pintype "passive"))
      (node (ref "LED567") (pin "K") (pinfunction "C_K") (pintype "passive"))
      (node (ref "LED568") (pin "K") (pinfunction "C_K") (pintype "passive"))
      (node (ref "U$1") (pin "P$8") (pinfunction "P$8_P$8") (pintype "bidirectional"))
    )
    (net (code "28") (name "Net-(LED33-C)") (class "Default")
      (node (ref "LED33") (pin "K") (pinfunction "C_K") (pintype "passive"))
      (node (ref "LED569") (pin "K") (pinfunction "C_K") (pintype "passive"))
      (node (ref "LED570") (pin "K") (pinfunction "C_K") (pintype "passive"))
      (node (ref "LED571") (pin "K") (pinfunction "C_K") (pintype "passive"))
      (node (ref "LED572") (pin "K") (pinfunction "C_K") (pintype "passive"))
      (node (ref "LED573") (pin "K") (pinfunction "C_K") (pintype "passive"))
      (node (ref "LED574") (pin "K") (pinfunction "C_K") (pintype "passive"))
      (node (ref "LED575") (pin "K") (pinfunction "C_K") (pintype "passive"))
      (node (ref "LED576") (pin "K") (pinfunction "C_K") (pintype "passive"))
      (node (ref "U$1") (pin "P$7") (pinfunction "P$7_P$7") (pintype "bidirectional"))
    )
    (net (code "29") (name "Net-(LED34-C)") (class "Default")
      (node (ref "LED34") (pin "K") (pinfunction "C_K") (pintype "passive"))
      (node (ref "LED577") (pin "K") (pinfunction "C_K") (pintype "passive"))
      (node (ref "LED578") (pin "K") (pinfunction "C_K") (pintype "passive"))
      (node (ref "LED579") (pin "K") (pinfunction "C_K") (pintype "passive"))
      (node (ref "LED580") (pin "K") (pinfunction "C_K") (pintype "passive"))
      (node (ref "LED581") (pin "K") (pinfunction "C_K") (pintype "passive"))
      (node (ref "LED582") (pin "K") (pinfunction "C_K") (pintype "passive"))
      (node (ref "LED583") (pin "K") (pinfunction "C_K") (pintype "passive"))
      (node (ref "LED584") (pin "K") (pinfunction "C_K") (pintype "passive"))
      (node (ref "U$1") (pin "P$6") (pinfunction "P$6_P$6") (pintype "bidirectional"))
    )
    (net (code "30") (name "Net-(LED35-C)") (class "Default")
      (node (ref "LED35") (pin "K") (pinfunction "C_K") (pintype "passive"))
      (node (ref "LED585") (pin "K") (pinfunction "C_K") (pintype "passive"))
      (node (ref "LED586") (pin "K") (pinfunction "C_K") (pintype "passive"))
      (node (ref "LED587") (pin "K") (pinfunction "C_K") (pintype "passive"))
      (node (ref "LED588") (pin "K") (pinfunction "C_K") (pintype "passive"))
      (node (ref "LED589") (pin "K") (pinfunction "C_K") (pintype "passive"))
      (node (ref "LED590") (pin "K") (pinfunction "C_K") (pintype "passive"))
      (node (ref "LED591") (pin "K") (pinfunction "C_K") (pintype "passive"))
      (node (ref "LED592") (pin "K") (pinfunction "C_K") (pintype "passive"))
      (node (ref "U$1") (pin "P$5") (pinfunction "P$5_P$5") (pintype "bidirectional"))
    )
    (net (code "31") (name "Net-(LED36-C)") (class "Default")
      (node (ref "LED36") (pin "K") (pinfunction "C_K") (pintype "passive"))
      (node (ref "LED593") (pin "K") (pinfunction "C_K") (pintype "passive"))
      (node (ref "LED594") (pin "K") (pinfunction "C_K") (pintype "passive"))
      (node (ref "LED595") (pin "K") (pinfunction "C_K") (pintype "passive"))
      (node (ref "LED596") (pin "K") (pinfunction "C_K") (pintype "passive"))
      (node (ref "LED597") (pin "K") (pinfunction "C_K") (pintype "passive"))
      (node (ref "LED598") (pin "K") (pinfunction "C_K") (pintype "passive"))
      (node (ref "LED599") (pin "K") (pinfunction "C_K") (pintype "passive"))
      (node (ref "LED600") (pin "K") (pinfunction "C_K") (pintype "passive"))
      (node (ref "U$1") (pin "P$4") (pinfunction "P$4_P$4") (pintype "bidirectional"))
    )
    (net (code "32") (name "Net-(LED37-C)") (class "Default")
      (node (ref "LED37") (pin "K") (pinfunction "C_K") (pintype "passive"))
      (node (ref "LED601") (pin "K") (pinfunction "C_K") (pintype "passive"))
      (node (ref "LED602") (pin "K") (pinfunction "C_K") (pintype "passive"))
      (node (ref "LED603") (pin "K") (pinfunction "C_K") (pintype "passive"))
      (node (ref "LED604") (pin "K") (pinfunction "C_K") (pintype "passive"))
      (node (ref "LED605") (pin "K") (pinfunction "C_K") (pintype "passive"))
      (node (ref "LED606") (pin "K") (pinfunction "C_K") (pintype "passive"))
      (node (ref "LED607") (pin "K") (pinfunction "C_K") (pintype "passive"))
      (node (ref "LED608") (pin "K") (pinfunction "C_K") (pintype "passive"))
      (node (ref "U$1") (pin "P$3") (pinfunction "P$3_P$3") (pintype "bidirectional"))
    )
    (net (code "33") (name "Net-(LED38-C)") (class "Default")
      (node (ref "LED38") (pin "K") (pinfunction "C_K") (pintype "passive"))
      (node (ref "LED609") (pin "K") (pinfunction "C_K") (pintype "passive"))
      (node (ref "LED610") (pin "K") (pinfunction "C_K") (pintype "passive"))
      (node (ref "LED611") (pin "K") (pinfunction "C_K") (pintype "passive"))
      (node (ref "LED612") (pin "K") (pinfunction "C_K") (pintype "passive"))
      (node (ref "LED613") (pin "K") (pinfunction "C_K") (pintype "passive"))
      (node (ref "LED614") (pin "K") (pinfunction "C_K") (pintype "passive"))
      (node (ref "LED615") (pin "K") (pinfunction "C_K") (pintype "passive"))
      (node (ref "LED616") (pin "K") (pinfunction "C_K") (pintype "passive"))
      (node (ref "U$1") (pin "P$2") (pinfunction "P$2_P$2") (pintype "bidirectional"))
    )
    (net (code "34") (name "Net-(LED39-C)") (class "Default")
      (node (ref "LED39") (pin "K") (pinfunction "C_K") (pintype "passive"))
      (node (ref "LED617") (pin "K") (pinfunction "C_K") (pintype "passive"))
      (node (ref "LED618") (pin "K") (pinfunction "C_K") (pintype "passive"))
      (node (ref "LED619") (pin "K") (pinfunction "C_K") (pintype "passive"))
      (node (ref "LED620") (pin "K") (pinfunction "C_K") (pintype "passive"))
      (node (ref "LED621") (pin "K") (pinfunction "C_K") (pintype "passive"))
      (node (ref "LED622") (pin "K") (pinfunction "C_K") (pintype "passive"))
      (node (ref "LED623") (pin "K") (pinfunction "C_K") (pintype "passive"))
      (node (ref "LED624") (pin "K") (pinfunction "C_K") (pintype "passive"))
      (node (ref "U$1") (pin "P$1") (pinfunction "P$1_P$1") (pintype "bidirectional"))
    )
    (net (code "35") (name "Net-(LED313-PadA)") (class "Default")
      (node (ref "LED313") (pin "A") (pinfunction "A_A") (pintype "passive"))
      (node (ref "LED321") (pin "A") (pinfunction "A_A") (pintype "passive"))
      (node (ref "LED329") (pin "A") (pinfunction "A_A") (pintype "passive"))
      (node (ref "LED337") (pin "A") (pinfunction "A_A") (pintype "passive"))
      (node (ref "LED345") (pin "A") (pinfunction "A_A") (pintype "passive"))
      (node (ref "LED353") (pin "A") (pinfunction "A_A") (pintype "passive"))
      (node (ref "LED361") (pin "A") (pinfunction "A_A") (pintype "passive"))
      (node (ref "LED369") (pin "A") (pinfunction "A_A") (pintype "passive"))
      (node (ref "LED377") (pin "A") (pinfunction "A_A") (pintype "passive"))
      (node (ref "LED385") (pin "A") (pinfunction "A_A") (pintype "passive"))
      (node (ref "LED393") (pin "A") (pinfunction "A_A") (pintype "passive"))
      (node (ref "LED401") (pin "A") (pinfunction "A_A") (pintype "passive"))
      (node (ref "LED409") (pin "A") (pinfunction "A_A") (pintype "passive"))
      (node (ref "LED417") (pin "A") (pinfunction "A_A") (pintype "passive"))
      (node (ref "LED425") (pin "A") (pinfunction "A_A") (pintype "passive"))
      (node (ref "LED433") (pin "A") (pinfunction "A_A") (pintype "passive"))
      (node (ref "LED441") (pin "A") (pinfunction "A_A") (pintype "passive"))
      (node (ref "LED449") (pin "A") (pinfunction "A_A") (pintype "passive"))
      (node (ref "LED457") (pin "A") (pinfunction "A_A") (pintype "passive"))
      (node (ref "LED465") (pin "A") (pinfunction "A_A") (pintype "passive"))
      (node (ref "LED473") (pin "A") (pinfunction "A_A") (pintype "passive"))
      (node (ref "LED481") (pin "A") (pinfunction "A_A") (pintype "passive"))
      (node (ref "LED489") (pin "A") (pinfunction "A_A") (pintype "passive"))
      (node (ref "LED497") (pin "A") (pinfunction "A_A") (pintype "passive"))
      (node (ref "LED505") (pin "A") (pinfunction "A_A") (pintype "passive"))
      (node (ref "LED513") (pin "A") (pinfunction "A_A") (pintype "passive"))
      (node (ref "LED521") (pin "A") (pinfunction "A_A") (pintype "passive"))
      (node (ref "LED529") (pin "A") (pinfunction "A_A") (pintype "passive"))
      (node (ref "LED537") (pin "A") (pinfunction "A_A") (pintype "passive"))
      (node (ref "LED545") (pin "A") (pinfunction "A_A") (pintype "passive"))
      (node (ref "LED553") (pin "A") (pinfunction "A_A") (pintype "passive"))
      (node (ref "LED561") (pin "A") (pinfunction "A_A") (pintype "passive"))
      (node (ref "LED569") (pin "A") (pinfunction "A_A") (pintype "passive"))
      (node (ref "LED577") (pin "A") (pinfunction "A_A") (pintype "passive"))
      (node (ref "LED585") (pin "A") (pinfunction "A_A") (pintype "passive"))
      (node (ref "LED593") (pin "A") (pinfunction "A_A") (pintype "passive"))
      (node (ref "LED601") (pin "A") (pinfunction "A_A") (pintype "passive"))
      (node (ref "LED609") (pin "A") (pinfunction "A_A") (pintype "passive"))
      (node (ref "LED617") (pin "A") (pinfunction "A_A") (pintype "passive"))
      (node (ref "U$4") (pin "P$8") (pinfunction "P$8_P$8") (pintype "bidirectional"))
    )
    (net (code "36") (name "Net-(LED314-PadA)") (class "Default")
      (node (ref "LED314") (pin "A") (pinfunction "A_A") (pintype "passive"))
      (node (ref "LED322") (pin "A") (pinfunction "A_A") (pintype "passive"))
      (node (ref "LED330") (pin "A") (pinfunction "A_A") (pintype "passive"))
      (node (ref "LED338") (pin "A") (pinfunction "A_A") (pintype "passive"))
      (node (ref "LED346") (pin "A") (pinfunction "A_A") (pintype "passive"))
      (node (ref "LED354") (pin "A") (pinfunction "A_A") (pintype "passive"))
      (node (ref "LED362") (pin "A") (pinfunction "A_A") (pintype "passive"))
      (node (ref "LED370") (pin "A") (pinfunction "A_A") (pintype "passive"))
      (node (ref "LED378") (pin "A") (pinfunction "A_A") (pintype "passive"))
      (node (ref "LED386") (pin "A") (pinfunction "A_A") (pintype "passive"))
      (node (ref "LED394") (pin "A") (pinfunction "A_A") (pintype "passive"))
      (node (ref "LED402") (pin "A") (pinfunction "A_A") (pintype "passive"))
      (node (ref "LED410") (pin "A") (pinfunction "A_A") (pintype "passive"))
      (node (ref "LED418") (pin "A") (pinfunction "A_A") (pintype "passive"))
      (node (ref "LED426") (pin "A") (pinfunction "A_A") (pintype "passive"))
      (node (ref "LED434") (pin "A") (pinfunction "A_A") (pintype "passive"))
      (node (ref "LED442") (pin "A") (pinfunction "A_A") (pintype "passive"))
      (node (ref "LED450") (pin "A") (pinfunction "A_A") (pintype "passive"))
      (node (ref "LED458") (pin "A") (pinfunction "A_A") (pintype "passive"))
      (node (ref "LED466") (pin "A") (pinfunction "A_A") (pintype "passive"))
      (node (ref "LED474") (pin "A") (pinfunction "A_A") (pintype "passive"))
      (node (ref "LED482") (pin "A") (pinfunction "A_A") (pintype "passive"))
      (node (ref "LED490") (pin "A") (pinfunction "A_A") (pintype "passive"))
      (node (ref "LED498") (pin "A") (pinfunction "A_A") (pintype "passive"))
      (node (ref "LED506") (pin "A") (pinfunction "A_A") (pintype "passive"))
      (node (ref "LED514") (pin "A") (pinfunction "A_A") (pintype "passive"))
      (node (ref "LED522") (pin "A") (pinfunction "A_A") (pintype "passive"))
      (node (ref "LED530") (pin "A") (pinfunction "A_A") (pintype "passive"))
      (node (ref "LED538") (pin "A") (pinfunction "A_A") (pintype "passive"))
      (node (ref "LED546") (pin "A") (pinfunction "A_A") (pintype "passive"))
      (node (ref "LED554") (pin "A") (pinfunction "A_A") (pintype "passive"))
      (node (ref "LED562") (pin "A") (pinfunction "A_A") (pintype "passive"))
      (node (ref "LED570") (pin "A") (pinfunction "A_A") (pintype "passive"))
      (node (ref "LED578") (pin "A") (pinfunction "A_A") (pintype "passive"))
      (node (ref "LED586") (pin "A") (pinfunction "A_A") (pintype "passive"))
      (node (ref "LED594") (pin "A") (pinfunction "A_A") (pintype "passive"))
      (node (ref "LED602") (pin "A") (pinfunction "A_A") (pintype "passive"))
      (node (ref "LED610") (pin "A") (pinfunction "A_A") (pintype "passive"))
      (node (ref "LED618") (pin "A") (pinfunction "A_A") (pintype "passive"))
      (node (ref "U$4") (pin "P$7") (pinfunction "P$7_P$7") (pintype "bidirectional"))
    )
    (net (code "37") (name "Net-(LED315-PadA)") (class "Default")
      (node (ref "LED315") (pin "A") (pinfunction "A_A") (pintype "passive"))
      (node (ref "LED323") (pin "A") (pinfunction "A_A") (pintype "passive"))
      (node (ref "LED331") (pin "A") (pinfunction "A_A") (pintype "passive"))
      (node (ref "LED339") (pin "A") (pinfunction "A_A") (pintype "passive"))
      (node (ref "LED347") (pin "A") (pinfunction "A_A") (pintype "passive"))
      (node (ref "LED355") (pin "A") (pinfunction "A_A") (pintype "passive"))
      (node (ref "LED363") (pin "A") (pinfunction "A_A") (pintype "passive"))
      (node (ref "LED371") (pin "A") (pinfunction "A_A") (pintype "passive"))
      (node (ref "LED379") (pin "A") (pinfunction "A_A") (pintype "passive"))
      (node (ref "LED387") (pin "A") (pinfunction "A_A") (pintype "passive"))
      (node (ref "LED395") (pin "A") (pinfunction "A_A") (pintype "passive"))
      (node (ref "LED403") (pin "A") (pinfunction "A_A") (pintype "passive"))
      (node (ref "LED411") (pin "A") (pinfunction "A_A") (pintype "passive"))
      (node (ref "LED419") (pin "A") (pinfunction "A_A") (pintype "passive"))
      (node (ref "LED427") (pin "A") (pinfunction "A_A") (pintype "passive"))
      (node (ref "LED435") (pin "A") (pinfunction "A_A") (pintype "passive"))
      (node (ref "LED443") (pin "A") (pinfunction "A_A") (pintype "passive"))
      (node (ref "LED451") (pin "A") (pinfunction "A_A") (pintype "passive"))
      (node (ref "LED459") (pin "A") (pinfunction "A_A") (pintype "passive"))
      (node (ref "LED467") (pin "A") (pinfunction "A_A") (pintype "passive"))
      (node (ref "LED475") (pin "A") (pinfunction "A_A") (pintype "passive"))
      (node (ref "LED483") (pin "A") (pinfunction "A_A") (pintype "passive"))
      (node (ref "LED491") (pin "A") (pinfunction "A_A") (pintype "passive"))
      (node (ref "LED499") (pin "A") (pinfunction "A_A") (pintype "passive"))
      (node (ref "LED507") (pin "A") (pinfunction "A_A") (pintype "passive"))
      (node (ref "LED515") (pin "A") (pinfunction "A_A") (pintype "passive"))
      (node (ref "LED523") (pin "A") (pinfunction "A_A") (pintype "passive"))
      (node (ref "LED531") (pin "A") (pinfunction "A_A") (pintype "passive"))
      (node (ref "LED539") (pin "A") (pinfunction "A_A") (pintype "passive"))
      (node (ref "LED547") (pin "A") (pinfunction "A_A") (pintype "passive"))
      (node (ref "LED555") (pin "A") (pinfunction "A_A") (pintype "passive"))
      (node (ref "LED563") (pin "A") (pinfunction "A_A") (pintype "passive"))
      (node (ref "LED571") (pin "A") (pinfunction "A_A") (pintype "passive"))
      (node (ref "LED579") (pin "A") (pinfunction "A_A") (pintype "passive"))
      (node (ref "LED587") (pin "A") (pinfunction "A_A") (pintype "passive"))
      (node (ref "LED595") (pin "A") (pinfunction "A_A") (pintype "passive"))
      (node (ref "LED603") (pin "A") (pinfunction "A_A") (pintype "passive"))
      (node (ref "LED611") (pin "A") (pinfunction "A_A") (pintype "passive"))
      (node (ref "LED619") (pin "A") (pinfunction "A_A") (pintype "passive"))
      (node (ref "U$4") (pin "P$6") (pinfunction "P$6_P$6") (pintype "bidirectional"))
    )
    (net (code "38") (name "Net-(LED316-PadA)") (class "Default")
      (node (ref "LED316") (pin "A") (pinfunction "A_A") (pintype "passive"))
      (node (ref "LED324") (pin "A") (pinfunction "A_A") (pintype "passive"))
      (node (ref "LED332") (pin "A") (pinfunction "A_A") (pintype "passive"))
      (node (ref "LED340") (pin "A") (pinfunction "A_A") (pintype "passive"))
      (node (ref "LED348") (pin "A") (pinfunction "A_A") (pintype "passive"))
      (node (ref "LED356") (pin "A") (pinfunction "A_A") (pintype "passive"))
      (node (ref "LED364") (pin "A") (pinfunction "A_A") (pintype "passive"))
      (node (ref "LED372") (pin "A") (pinfunction "A_A") (pintype "passive"))
      (node (ref "LED380") (pin "A") (pinfunction "A_A") (pintype "passive"))
      (node (ref "LED388") (pin "A") (pinfunction "A_A") (pintype "passive"))
      (node (ref "LED396") (pin "A") (pinfunction "A_A") (pintype "passive"))
      (node (ref "LED404") (pin "A") (pinfunction "A_A") (pintype "passive"))
      (node (ref "LED412") (pin "A") (pinfunction "A_A") (pintype "passive"))
      (node (ref "LED420") (pin "A") (pinfunction "A_A") (pintype "passive"))
      (node (ref "LED428") (pin "A") (pinfunction "A_A") (pintype "passive"))
      (node (ref "LED436") (pin "A") (pinfunction "A_A") (pintype "passive"))
      (node (ref "LED444") (pin "A") (pinfunction "A_A") (pintype "passive"))
      (node (ref "LED452") (pin "A") (pinfunction "A_A") (pintype "passive"))
      (node (ref "LED460") (pin "A") (pinfunction "A_A") (pintype "passive"))
      (node (ref "LED468") (pin "A") (pinfunction "A_A") (pintype "passive"))
      (node (ref "LED476") (pin "A") (pinfunction "A_A") (pintype "passive"))
      (node (ref "LED484") (pin "A") (pinfunction "A_A") (pintype "passive"))
      (node (ref "LED492") (pin "A") (pinfunction "A_A") (pintype "passive"))
      (node (ref "LED500") (pin "A") (pinfunction "A_A") (pintype "passive"))
      (node (ref "LED508") (pin "A") (pinfunction "A_A") (pintype "passive"))
      (node (ref "LED516") (pin "A") (pinfunction "A_A") (pintype "passive"))
      (node (ref "LED524") (pin "A") (pinfunction "A_A") (pintype "passive"))
      (node (ref "LED532") (pin "A") (pinfunction "A_A") (pintype "passive"))
      (node (ref "LED540") (pin "A") (pinfunction "A_A") (pintype "passive"))
      (node (ref "LED548") (pin "A") (pinfunction "A_A") (pintype "passive"))
      (node (ref "LED556") (pin "A") (pinfunction "A_A") (pintype "passive"))
      (node (ref "LED564") (pin "A") (pinfunction "A_A") (pintype "passive"))
      (node (ref "LED572") (pin "A") (pinfunction "A_A") (pintype "passive"))
      (node (ref "LED580") (pin "A") (pinfunction "A_A") (pintype "passive"))
      (node (ref "LED588") (pin "A") (pinfunction "A_A") (pintype "passive"))
      (node (ref "LED596") (pin "A") (pinfunction "A_A") (pintype "passive"))
      (node (ref "LED604") (pin "A") (pinfunction "A_A") (pintype "passive"))
      (node (ref "LED612") (pin "A") (pinfunction "A_A") (pintype "passive"))
      (node (ref "LED620") (pin "A") (pinfunction "A_A") (pintype "passive"))
      (node (ref "U$4") (pin "P$5") (pinfunction "P$5_P$5") (pintype "bidirectional"))
    )
    (net (code "39") (name "Net-(LED317-PadA)") (class "Default")
      (node (ref "LED317") (pin "A") (pinfunction "A_A") (pintype "passive"))
      (node (ref "LED325") (pin "A") (pinfunction "A_A") (pintype "passive"))
      (node (ref "LED333") (pin "A") (pinfunction "A_A") (pintype "passive"))
      (node (ref "LED341") (pin "A") (pinfunction "A_A") (pintype "passive"))
      (node (ref "LED349") (pin "A") (pinfunction "A_A") (pintype "passive"))
      (node (ref "LED357") (pin "A") (pinfunction "A_A") (pintype "passive"))
      (node (ref "LED365") (pin "A") (pinfunction "A_A") (pintype "passive"))
      (node (ref "LED373") (pin "A") (pinfunction "A_A") (pintype "passive"))
      (node (ref "LED381") (pin "A") (pinfunction "A_A") (pintype "passive"))
      (node (ref "LED389") (pin "A") (pinfunction "A_A") (pintype "passive"))
      (node (ref "LED397") (pin "A") (pinfunction "A_A") (pintype "passive"))
      (node (ref "LED405") (pin "A") (pinfunction "A_A") (pintype "passive"))
      (node (ref "LED413") (pin "A") (pinfunction "A_A") (pintype "passive"))
      (node (ref "LED421") (pin "A") (pinfunction "A_A") (pintype "passive"))
      (node (ref "LED429") (pin "A") (pinfunction "A_A") (pintype "passive"))
      (node (ref "LED437") (pin "A") (pinfunction "A_A") (pintype "passive"))
      (node (ref "LED445") (pin "A") (pinfunction "A_A") (pintype "passive"))
      (node (ref "LED453") (pin "A") (pinfunction "A_A") (pintype "passive"))
      (node (ref "LED461") (pin "A") (pinfunction "A_A") (pintype "passive"))
      (node (ref "LED469") (pin "A") (pinfunction "A_A") (pintype "passive"))
      (node (ref "LED477") (pin "A") (pinfunction "A_A") (pintype "passive"))
      (node (ref "LED485") (pin "A") (pinfunction "A_A") (pintype "passive"))
      (node (ref "LED493") (pin "A") (pinfunction "A_A") (pintype "passive"))
      (node (ref "LED501") (pin "A") (pinfunction "A_A") (pintype "passive"))
      (node (ref "LED509") (pin "A") (pinfunction "A_A") (pintype "passive"))
      (node (ref "LED517") (pin "A") (pinfunction "A_A") (pintype "passive"))
      (node (ref "LED525") (pin "A") (pinfunction "A_A") (pintype "passive"))
      (node (ref "LED533") (pin "A") (pinfunction "A_A") (pintype "passive"))
      (node (ref "LED541") (pin "A") (pinfunction "A_A") (pintype "passive"))
      (node (ref "LED549") (pin "A") (pinfunction "A_A") (pintype "passive"))
      (node (ref "LED557") (pin "A") (pinfunction "A_A") (pintype "passive"))
      (node (ref "LED565") (pin "A") (pinfunction "A_A") (pintype "passive"))
      (node (ref "LED573") (pin "A") (pinfunction "A_A") (pintype "passive"))
      (node (ref "LED581") (pin "A") (pinfunction "A_A") (pintype "passive"))
      (node (ref "LED589") (pin "A") (pinfunction "A_A") (pintype "passive"))
      (node (ref "LED597") (pin "A") (pinfunction "A_A") (pintype "passive"))
      (node (ref "LED605") (pin "A") (pinfunction "A_A") (pintype "passive"))
      (node (ref "LED613") (pin "A") (pinfunction "A_A") (pintype "passive"))
      (node (ref "LED621") (pin "A") (pinfunction "A_A") (pintype "passive"))
      (node (ref "U$4") (pin "P$4") (pinfunction "P$4_P$4") (pintype "bidirectional"))
    )
    (net (code "40") (name "Net-(LED318-PadA)") (class "Default")
      (node (ref "LED318") (pin "A") (pinfunction "A_A") (pintype "passive"))
      (node (ref "LED326") (pin "A") (pinfunction "A_A") (pintype "passive"))
      (node (ref "LED334") (pin "A") (pinfunction "A_A") (pintype "passive"))
      (node (ref "LED342") (pin "A") (pinfunction "A_A") (pintype "passive"))
      (node (ref "LED350") (pin "A") (pinfunction "A_A") (pintype "passive"))
      (node (ref "LED358") (pin "A") (pinfunction "A_A") (pintype "passive"))
      (node (ref "LED366") (pin "A") (pinfunction "A_A") (pintype "passive"))
      (node (ref "LED374") (pin "A") (pinfunction "A_A") (pintype "passive"))
      (node (ref "LED382") (pin "A") (pinfunction "A_A") (pintype "passive"))
      (node (ref "LED390") (pin "A") (pinfunction "A_A") (pintype "passive"))
      (node (ref "LED398") (pin "A") (pinfunction "A_A") (pintype "passive"))
      (node (ref "LED406") (pin "A") (pinfunction "A_A") (pintype "passive"))
      (node (ref "LED414") (pin "A") (pinfunction "A_A") (pintype "passive"))
      (node (ref "LED422") (pin "A") (pinfunction "A_A") (pintype "passive"))
      (node (ref "LED430") (pin "A") (pinfunction "A_A") (pintype "passive"))
      (node (ref "LED438") (pin "A") (pinfunction "A_A") (pintype "passive"))
      (node (ref "LED446") (pin "A") (pinfunction "A_A") (pintype "passive"))
      (node (ref "LED454") (pin "A") (pinfunction "A_A") (pintype "passive"))
      (node (ref "LED462") (pin "A") (pinfunction "A_A") (pintype "passive"))
      (node (ref "LED470") (pin "A") (pinfunction "A_A") (pintype "passive"))
      (node (ref "LED478") (pin "A") (pinfunction "A_A") (pintype "passive"))
      (node (ref "LED486") (pin "A") (pinfunction "A_A") (pintype "passive"))
      (node (ref "LED494") (pin "A") (pinfunction "A_A") (pintype "passive"))
      (node (ref "LED502") (pin "A") (pinfunction "A_A") (pintype "passive"))
      (node (ref "LED510") (pin "A") (pinfunction "A_A") (pintype "passive"))
      (node (ref "LED518") (pin "A") (pinfunction "A_A") (pintype "passive"))
      (node (ref "LED526") (pin "A") (pinfunction "A_A") (pintype "passive"))
      (node (ref "LED534") (pin "A") (pinfunction "A_A") (pintype "passive"))
      (node (ref "LED542") (pin "A") (pinfunction "A_A") (pintype "passive"))
      (node (ref "LED550") (pin "A") (pinfunction "A_A") (pintype "passive"))
      (node (ref "LED558") (pin "A") (pinfunction "A_A") (pintype "passive"))
      (node (ref "LED566") (pin "A") (pinfunction "A_A") (pintype "passive"))
      (node (ref "LED574") (pin "A") (pinfunction "A_A") (pintype "passive"))
      (node (ref "LED582") (pin "A") (pinfunction "A_A") (pintype "passive"))
      (node (ref "LED590") (pin "A") (pinfunction "A_A") (pintype "passive"))
      (node (ref "LED598") (pin "A") (pinfunction "A_A") (pintype "passive"))
      (node (ref "LED606") (pin "A") (pinfunction "A_A") (pintype "passive"))
      (node (ref "LED614") (pin "A") (pinfunction "A_A") (pintype "passive"))
      (node (ref "LED622") (pin "A") (pinfunction "A_A") (pintype "passive"))
      (node (ref "U$4") (pin "P$3") (pinfunction "P$3_P$3") (pintype "bidirectional"))
    )
    (net (code "41") (name "Net-(LED319-PadA)") (class "Default")
      (node (ref "LED319") (pin "A") (pinfunction "A_A") (pintype "passive"))
      (node (ref "LED327") (pin "A") (pinfunction "A_A") (pintype "passive"))
      (node (ref "LED335") (pin "A") (pinfunction "A_A") (pintype "passive"))
      (node (ref "LED343") (pin "A") (pinfunction "A_A") (pintype "passive"))
      (node (ref "LED351") (pin "A") (pinfunction "A_A") (pintype "passive"))
      (node (ref "LED359") (pin "A") (pinfunction "A_A") (pintype "passive"))
      (node (ref "LED367") (pin "A") (pinfunction "A_A") (pintype "passive"))
      (node (ref "LED375") (pin "A") (pinfunction "A_A") (pintype "passive"))
      (node (ref "LED383") (pin "A") (pinfunction "A_A") (pintype "passive"))
      (node (ref "LED391") (pin "A") (pinfunction "A_A") (pintype "passive"))
      (node (ref "LED399") (pin "A") (pinfunction "A_A") (pintype "passive"))
      (node (ref "LED407") (pin "A") (pinfunction "A_A") (pintype "passive"))
      (node (ref "LED415") (pin "A") (pinfunction "A_A") (pintype "passive"))
      (node (ref "LED423") (pin "A") (pinfunction "A_A") (pintype "passive"))
      (node (ref "LED431") (pin "A") (pinfunction "A_A") (pintype "passive"))
      (node (ref "LED439") (pin "A") (pinfunction "A_A") (pintype "passive"))
      (node (ref "LED447") (pin "A") (pinfunction "A_A") (pintype "passive"))
      (node (ref "LED455") (pin "A") (pinfunction "A_A") (pintype "passive"))
      (node (ref "LED463") (pin "A") (pinfunction "A_A") (pintype "passive"))
      (node (ref "LED471") (pin "A") (pinfunction "A_A") (pintype "passive"))
      (node (ref "LED479") (pin "A") (pinfunction "A_A") (pintype "passive"))
      (node (ref "LED487") (pin "A") (pinfunction "A_A") (pintype "passive"))
      (node (ref "LED495") (pin "A") (pinfunction "A_A") (pintype "passive"))
      (node (ref "LED503") (pin "A") (pinfunction "A_A") (pintype "passive"))
      (node (ref "LED511") (pin "A") (pinfunction "A_A") (pintype "passive"))
      (node (ref "LED519") (pin "A") (pinfunction "A_A") (pintype "passive"))
      (node (ref "LED527") (pin "A") (pinfunction "A_A") (pintype "passive"))
      (node (ref "LED535") (pin "A") (pinfunction "A_A") (pintype "passive"))
      (node (ref "LED543") (pin "A") (pinfunction "A_A") (pintype "passive"))
      (node (ref "LED551") (pin "A") (pinfunction "A_A") (pintype "passive"))
      (node (ref "LED559") (pin "A") (pinfunction "A_A") (pintype "passive"))
      (node (ref "LED567") (pin "A") (pinfunction "A_A") (pintype "passive"))
      (node (ref "LED575") (pin "A") (pinfunction "A_A") (pintype "passive"))
      (node (ref "LED583") (pin "A") (pinfunction "A_A") (pintype "passive"))
      (node (ref "LED591") (pin "A") (pinfunction "A_A") (pintype "passive"))
      (node (ref "LED599") (pin "A") (pinfunction "A_A") (pintype "passive"))
      (node (ref "LED607") (pin "A") (pinfunction "A_A") (pintype "passive"))
      (node (ref "LED615") (pin "A") (pinfunction "A_A") (pintype "passive"))
      (node (ref "LED623") (pin "A") (pinfunction "A_A") (pintype "passive"))
      (node (ref "U$4") (pin "P$2") (pinfunction "P$2_P$2") (pintype "bidirectional"))
    )
    (net (code "42") (name "Net-(LED320-PadA)") (class "Default")
      (node (ref "LED320") (pin "A") (pinfunction "A_A") (pintype "passive"))
      (node (ref "LED328") (pin "A") (pinfunction "A_A") (pintype "passive"))
      (node (ref "LED336") (pin "A") (pinfunction "A_A") (pintype "passive"))
      (node (ref "LED344") (pin "A") (pinfunction "A_A") (pintype "passive"))
      (node (ref "LED352") (pin "A") (pinfunction "A_A") (pintype "passive"))
      (node (ref "LED360") (pin "A") (pinfunction "A_A") (pintype "passive"))
      (node (ref "LED368") (pin "A") (pinfunction "A_A") (pintype "passive"))
      (node (ref "LED376") (pin "A") (pinfunction "A_A") (pintype "passive"))
      (node (ref "LED384") (pin "A") (pinfunction "A_A") (pintype "passive"))
      (node (ref "LED392") (pin "A") (pinfunction "A_A") (pintype "passive"))
      (node (ref "LED400") (pin "A") (pinfunction "A_A") (pintype "passive"))
      (node (ref "LED408") (pin "A") (pinfunction "A_A") (pintype "passive"))
      (node (ref "LED416") (pin "A") (pinfunction "A_A") (pintype "passive"))
      (node (ref "LED424") (pin "A") (pinfunction "A_A") (pintype "passive"))
      (node (ref "LED432") (pin "A") (pinfunction "A_A") (pintype "passive"))
      (node (ref "LED440") (pin "A") (pinfunction "A_A") (pintype "passive"))
      (node (ref "LED448") (pin "A") (pinfunction "A_A") (pintype "passive"))
      (node (ref "LED456") (pin "A") (pinfunction "A_A") (pintype "passive"))
      (node (ref "LED464") (pin "A") (pinfunction "A_A") (pintype "passive"))
      (node (ref "LED472") (pin "A") (pinfunction "A_A") (pintype "passive"))
      (node (ref "LED480") (pin "A") (pinfunction "A_A") (pintype "passive"))
      (node (ref "LED488") (pin "A") (pinfunction "A_A") (pintype "passive"))
      (node (ref "LED496") (pin "A") (pinfunction "A_A") (pintype "passive"))
      (node (ref "LED504") (pin "A") (pinfunction "A_A") (pintype "passive"))
      (node (ref "LED512") (pin "A") (pinfunction "A_A") (pintype "passive"))
      (node (ref "LED520") (pin "A") (pinfunction "A_A") (pintype "passive"))
      (node (ref "LED528") (pin "A") (pinfunction "A_A") (pintype "passive"))
      (node (ref "LED536") (pin "A") (pinfunction "A_A") (pintype "passive"))
      (node (ref "LED544") (pin "A") (pinfunction "A_A") (pintype "passive"))
      (node (ref "LED552") (pin "A") (pinfunction "A_A") (pintype "passive"))
      (node (ref "LED560") (pin "A") (pinfunction "A_A") (pintype "passive"))
      (node (ref "LED568") (pin "A") (pinfunction "A_A") (pintype "passive"))
      (node (ref "LED576") (pin "A") (pinfunction "A_A") (pintype "passive"))
      (node (ref "LED584") (pin "A") (pinfunction "A_A") (pintype "passive"))
      (node (ref "LED592") (pin "A") (pinfunction "A_A") (pintype "passive"))
      (node (ref "LED600") (pin "A") (pinfunction "A_A") (pintype "passive"))
      (node (ref "LED608") (pin "A") (pinfunction "A_A") (pintype "passive"))
      (node (ref "LED616") (pin "A") (pinfunction "A_A") (pintype "passive"))
      (node (ref "LED624") (pin "A") (pinfunction "A_A") (pintype "passive"))
      (node (ref "U$4") (pin "P$1") (pinfunction "P$1_P$1") (pintype "bidirectional"))
    )
    (net (code "43") (name "Net-(LED337-C)") (class "Default")
      (node (ref "LED337") (pin "K") (pinfunction "C_K") (pintype "passive"))
      (node (ref "LED338") (pin "K") (pinfunction "C_K") (pintype "passive"))
      (node (ref "LED339") (pin "K") (pinfunction "C_K") (pintype "passive"))
      (node (ref "LED340") (pin "K") (pinfunction "C_K") (pintype "passive"))
      (node (ref "LED341") (pin "K") (pinfunction "C_K") (pintype "passive"))
      (node (ref "LED342") (pin "K") (pinfunction "C_K") (pintype "passive"))
      (node (ref "LED343") (pin "K") (pinfunction "C_K") (pintype "passive"))
      (node (ref "LED344") (pin "K") (pinfunction "C_K") (pintype "passive"))
      (node (ref "LED4") (pin "K") (pinfunction "C_K") (pintype "passive"))
      (node (ref "U$1") (pin "P$36") (pinfunction "P$36_P$36") (pintype "bidirectional"))
    )
    (net (code "44") (name "Net-(LED345-C)") (class "Default")
      (node (ref "LED345") (pin "K") (pinfunction "C_K") (pintype "passive"))
      (node (ref "LED346") (pin "K") (pinfunction "C_K") (pintype "passive"))
      (node (ref "LED347") (pin "K") (pinfunction "C_K") (pintype "passive"))
      (node (ref "LED348") (pin "K") (pinfunction "C_K") (pintype "passive"))
      (node (ref "LED349") (pin "K") (pinfunction "C_K") (pintype "passive"))
      (node (ref "LED350") (pin "K") (pinfunction "C_K") (pintype "passive"))
      (node (ref "LED351") (pin "K") (pinfunction "C_K") (pintype "passive"))
      (node (ref "LED352") (pin "K") (pinfunction "C_K") (pintype "passive"))
      (node (ref "LED5") (pin "K") (pinfunction "C_K") (pintype "passive"))
      (node (ref "U$1") (pin "P$35") (pinfunction "P$35_P$35") (pintype "bidirectional"))
    )
    (net (code "45") (name "Net-(LED353-C)") (class "Default")
      (node (ref "LED353") (pin "K") (pinfunction "C_K") (pintype "passive"))
      (node (ref "LED354") (pin "K") (pinfunction "C_K") (pintype "passive"))
      (node (ref "LED355") (pin "K") (pinfunction "C_K") (pintype "passive"))
      (node (ref "LED356") (pin "K") (pinfunction "C_K") (pintype "passive"))
      (node (ref "LED357") (pin "K") (pinfunction "C_K") (pintype "passive"))
      (node (ref "LED358") (pin "K") (pinfunction "C_K") (pintype "passive"))
      (node (ref "LED359") (pin "K") (pinfunction "C_K") (pintype "passive"))
      (node (ref "LED360") (pin "K") (pinfunction "C_K") (pintype "passive"))
      (node (ref "LED6") (pin "K") (pinfunction "C_K") (pintype "passive"))
      (node (ref "U$1") (pin "P$34") (pinfunction "P$34_P$34") (pintype "bidirectional"))
    )
    (net (code "46") (name "Net-(LED361-C)") (class "Default")
      (node (ref "LED361") (pin "K") (pinfunction "C_K") (pintype "passive"))
      (node (ref "LED362") (pin "K") (pinfunction "C_K") (pintype "passive"))
      (node (ref "LED363") (pin "K") (pinfunction "C_K") (pintype "passive"))
      (node (ref "LED364") (pin "K") (pinfunction "C_K") (pintype "passive"))
      (node (ref "LED365") (pin "K") (pinfunction "C_K") (pintype "passive"))
      (node (ref "LED366") (pin "K") (pinfunction "C_K") (pintype "passive"))
      (node (ref "LED367") (pin "K") (pinfunction "C_K") (pintype "passive"))
      (node (ref "LED368") (pin "K") (pinfunction "C_K") (pintype "passive"))
      (node (ref "LED7") (pin "K") (pinfunction "C_K") (pintype "passive"))
      (node (ref "U$1") (pin "P$33") (pinfunction "P$33_P$33") (pintype "bidirectional"))
    )
    (net (code "47") (name "Net-(LED369-C)") (class "Default")
      (node (ref "LED369") (pin "K") (pinfunction "C_K") (pintype "passive"))
      (node (ref "LED370") (pin "K") (pinfunction "C_K") (pintype "passive"))
      (node (ref "LED371") (pin "K") (pinfunction "C_K") (pintype "passive"))
      (node (ref "LED372") (pin "K") (pinfunction "C_K") (pintype "passive"))
      (node (ref "LED373") (pin "K") (pinfunction "C_K") (pintype "passive"))
      (node (ref "LED374") (pin "K") (pinfunction "C_K") (pintype "passive"))
      (node (ref "LED375") (pin "K") (pinfunction "C_K") (pintype "passive"))
      (node (ref "LED376") (pin "K") (pinfunction "C_K") (pintype "passive"))
      (node (ref "LED8") (pin "K") (pinfunction "C_K") (pintype "passive"))
      (node (ref "U$1") (pin "P$32") (pinfunction "P$32_P$32") (pintype "bidirectional"))
    )
    (net (code "48") (name "Net-(LED377-C)") (class "Default")
      (node (ref "LED377") (pin "K") (pinfunction "C_K") (pintype "passive"))
      (node (ref "LED378") (pin "K") (pinfunction "C_K") (pintype "passive"))
      (node (ref "LED379") (pin "K") (pinfunction "C_K") (pintype "passive"))
      (node (ref "LED380") (pin "K") (pinfunction "C_K") (pintype "passive"))
      (node (ref "LED381") (pin "K") (pinfunction "C_K") (pintype "passive"))
      (node (ref "LED382") (pin "K") (pinfunction "C_K") (pintype "passive"))
      (node (ref "LED383") (pin "K") (pinfunction "C_K") (pintype "passive"))
      (node (ref "LED384") (pin "K") (pinfunction "C_K") (pintype "passive"))
      (node (ref "LED9") (pin "K") (pinfunction "C_K") (pintype "passive"))
      (node (ref "U$1") (pin "P$31") (pinfunction "P$31_P$31") (pintype "bidirectional"))
    )
    (net (code "49") (name "Net-(LED1000-C)") (class "Default")
      (node (ref "LED1000") (pin "K") (pinfunction "C_K") (pintype "passive"))
      (node (ref "LED1001") (pin "K") (pinfunction "C_K") (pintype "passive"))
      (node (ref "LED1002") (pin "K") (pinfunction "C_K") (pintype "passive"))
      (node (ref "LED1003") (pin "K") (pinfunction "C_K") (pintype "passive"))
      (node (ref "LED1004") (pin "K") (pinfunction "C_K") (pintype "passive"))
      (node (ref "LED1005") (pin "K") (pinfunction "C_K") (pintype "passive"))
      (node (ref "LED1006") (pin "K") (pinfunction "C_K") (pintype "passive"))
      (node (ref "LED1052") (pin "K") (pinfunction "C_K") (pintype "passive"))
      (node (ref "LED999") (pin "K") (pinfunction "C_K") (pintype "passive"))
      (node (ref "U$2") (pin "P$2") (pinfunction "P$2_P$2") (pintype "bidirectional"))
    )
    (net (code "50") (name "Net-(LED1000-PadA)") (class "Default")
      (node (ref "LED1000") (pin "A") (pinfunction "A_A") (pintype "passive"))
      (node (ref "LED1008") (pin "A") (pinfunction "A_A") (pintype "passive"))
      (node (ref "LED704") (pin "A") (pinfunction "A_A") (pintype "passive"))
      (node (ref "LED712") (pin "A") (pinfunction "A_A") (pintype "passive"))
      (node (ref "LED720") (pin "A") (pinfunction "A_A") (pintype "passive"))
      (node (ref "LED728") (pin "A") (pinfunction "A_A") (pintype "passive"))
      (node (ref "LED736") (pin "A") (pinfunction "A_A") (pintype "passive"))
      (node (ref "LED744") (pin "A") (pinfunction "A_A") (pintype "passive"))
      (node (ref "LED752") (pin "A") (pinfunction "A_A") (pintype "passive"))
      (node (ref "LED760") (pin "A") (pinfunction "A_A") (pintype "passive"))
      (node (ref "LED768") (pin "A") (pinfunction "A_A") (pintype "passive"))
      (node (ref "LED776") (pin "A") (pinfunction "A_A") (pintype "passive"))
      (node (ref "LED784") (pin "A") (pinfunction "A_A") (pintype "passive"))
      (node (ref "LED792") (pin "A") (pinfunction "A_A") (pintype "passive"))
      (node (ref "LED800") (pin "A") (pinfunction "A_A") (pintype "passive"))
      (node (ref "LED808") (pin "A") (pinfunction "A_A") (pintype "passive"))
      (node (ref "LED816") (pin "A") (pinfunction "A_A") (pintype "passive"))
      (node (ref "LED824") (pin "A") (pinfunction "A_A") (pintype "passive"))
      (node (ref "LED832") (pin "A") (pinfunction "A_A") (pintype "passive"))
      (node (ref "LED840") (pin "A") (pinfunction "A_A") (pintype "passive"))
      (node (ref "LED848") (pin "A") (pinfunction "A_A") (pintype "passive"))
      (node (ref "LED856") (pin "A") (pinfunction "A_A") (pintype "passive"))
      (node (ref "LED864") (pin "A") (pinfunction "A_A") (pintype "passive"))
      (node (ref "LED872") (pin "A") (pinfunction "A_A") (pintype "passive"))
      (node (ref "LED880") (pin "A") (pinfunction "A_A") (pintype "passive"))
      (node (ref "LED888") (pin "A") (pinfunction "A_A") (pintype "passive"))
      (node (ref "LED896") (pin "A") (pinfunction "A_A") (pintype "passive"))
      (node (ref "LED904") (pin "A") (pinfunction "A_A") (pintype "passive"))
      (node (ref "LED912") (pin "A") (pinfunction "A_A") (pintype "passive"))
      (node (ref "LED920") (pin "A") (pinfunction "A_A") (pintype "passive"))
      (node (ref "LED928") (pin "A") (pinfunction "A_A") (pintype "passive"))
      (node (ref "LED936") (pin "A") (pinfunction "A_A") (pintype "passive"))
      (node (ref "LED944") (pin "A") (pinfunction "A_A") (pintype "passive"))
      (node (ref "LED952") (pin "A") (pinfunction "A_A") (pintype "passive"))
      (node (ref "LED960") (pin "A") (pinfunction "A_A") (pintype "passive"))
      (node (ref "LED968") (pin "A") (pinfunction "A_A") (pintype "passive"))
      (node (ref "LED976") (pin "A") (pinfunction "A_A") (pintype "passive"))
      (node (ref "LED984") (pin "A") (pinfunction "A_A") (pintype "passive"))
      (node (ref "LED992") (pin "A") (pinfunction "A_A") (pintype "passive"))
      (node (ref "U$3") (pin "P$7") (pinfunction "P$7_P$7") (pintype "bidirectional"))
    )
    (net (code "51") (name "Net-(LED1001-PadA)") (class "Default")
      (node (ref "LED1001") (pin "A") (pinfunction "A_A") (pintype "passive"))
      (node (ref "LED1009") (pin "A") (pinfunction "A_A") (pintype "passive"))
      (node (ref "LED705") (pin "A") (pinfunction "A_A") (pintype "passive"))
      (node (ref "LED713") (pin "A") (pinfunction "A_A") (pintype "passive"))
      (node (ref "LED721") (pin "A") (pinfunction "A_A") (pintype "passive"))
      (node (ref "LED729") (pin "A") (pinfunction "A_A") (pintype "passive"))
      (node (ref "LED737") (pin "A") (pinfunction "A_A") (pintype "passive"))
      (node (ref "LED745") (pin "A") (pinfunction "A_A") (pintype "passive"))
      (node (ref "LED753") (pin "A") (pinfunction "A_A") (pintype "passive"))
      (node (ref "LED761") (pin "A") (pinfunction "A_A") (pintype "passive"))
      (node (ref "LED769") (pin "A") (pinfunction "A_A") (pintype "passive"))
      (node (ref "LED777") (pin "A") (pinfunction "A_A") (pintype "passive"))
      (node (ref "LED785") (pin "A") (pinfunction "A_A") (pintype "passive"))
      (node (ref "LED793") (pin "A") (pinfunction "A_A") (pintype "passive"))
      (node (ref "LED801") (pin "A") (pinfunction "A_A") (pintype "passive"))
      (node (ref "LED809") (pin "A") (pinfunction "A_A") (pintype "passive"))
      (node (ref "LED817") (pin "A") (pinfunction "A_A") (pintype "passive"))
      (node (ref "LED825") (pin "A") (pinfunction "A_A") (pintype "passive"))
      (node (ref "LED833") (pin "A") (pinfunction "A_A") (pintype "passive"))
      (node (ref "LED841") (pin "A") (pinfunction "A_A") (pintype "passive"))
      (node (ref "LED849") (pin "A") (pinfunction "A_A") (pintype "passive"))
      (node (ref "LED857") (pin "A") (pinfunction "A_A") (pintype "passive"))
      (node (ref "LED865") (pin "A") (pinfunction "A_A") (pintype "passive"))
      (node (ref "LED873") (pin "A") (pinfunction "A_A") (pintype "passive"))
      (node (ref "LED881") (pin "A") (pinfunction "A_A") (pintype "passive"))
      (node (ref "LED889") (pin "A") (pinfunction "A_A") (pintype "passive"))
      (node (ref "LED897") (pin "A") (pinfunction "A_A") (pintype "passive"))
      (node (ref "LED905") (pin "A") (pinfunction "A_A") (pintype "passive"))
      (node (ref "LED913") (pin "A") (pinfunction "A_A") (pintype "passive"))
      (node (ref "LED921") (pin "A") (pinfunction "A_A") (pintype "passive"))
      (node (ref "LED929") (pin "A") (pinfunction "A_A") (pintype "passive"))
      (node (ref "LED937") (pin "A") (pinfunction "A_A") (pintype "passive"))
      (node (ref "LED945") (pin "A") (pinfunction "A_A") (pintype "passive"))
      (node (ref "LED953") (pin "A") (pinfunction "A_A") (pintype "passive"))
      (node (ref "LED961") (pin "A") (pinfunction "A_A") (pintype "passive"))
      (node (ref "LED969") (pin "A") (pinfunction "A_A") (pintype "passive"))
      (node (ref "LED977") (pin "A") (pinfunction "A_A") (pintype "passive"))
      (node (ref "LED985") (pin "A") (pinfunction "A_A") (pintype "passive"))
      (node (ref "LED993") (pin "A") (pinfunction "A_A") (pintype "passive"))
      (node (ref "U$3") (pin "P$6") (pinfunction "P$6_P$6") (pintype "bidirectional"))
    )
    (net (code "52") (name "Net-(LED1002-PadA)") (class "Default")
      (node (ref "LED1002") (pin "A") (pinfunction "A_A") (pintype "passive"))
      (node (ref "LED1010") (pin "A") (pinfunction "A_A") (pintype "passive"))
      (node (ref "LED706") (pin "A") (pinfunction "A_A") (pintype "passive"))
      (node (ref "LED714") (pin "A") (pinfunction "A_A") (pintype "passive"))
      (node (ref "LED722") (pin "A") (pinfunction "A_A") (pintype "passive"))
      (node (ref "LED730") (pin "A") (pinfunction "A_A") (pintype "passive"))
      (node (ref "LED738") (pin "A") (pinfunction "A_A") (pintype "passive"))
      (node (ref "LED746") (pin "A") (pinfunction "A_A") (pintype "passive"))
      (node (ref "LED754") (pin "A") (pinfunction "A_A") (pintype "passive"))
      (node (ref "LED762") (pin "A") (pinfunction "A_A") (pintype "passive"))
      (node (ref "LED770") (pin "A") (pinfunction "A_A") (pintype "passive"))
      (node (ref "LED778") (pin "A") (pinfunction "A_A") (pintype "passive"))
      (node (ref "LED786") (pin "A") (pinfunction "A_A") (pintype "passive"))
      (node (ref "LED794") (pin "A") (pinfunction "A_A") (pintype "passive"))
      (node (ref "LED802") (pin "A") (pinfunction "A_A") (pintype "passive"))
      (node (ref "LED810") (pin "A") (pinfunction "A_A") (pintype "passive"))
      (node (ref "LED818") (pin "A") (pinfunction "A_A") (pintype "passive"))
      (node (ref "LED826") (pin "A") (pinfunction "A_A") (pintype "passive"))
      (node (ref "LED834") (pin "A") (pinfunction "A_A") (pintype "passive"))
      (node (ref "LED842") (pin "A") (pinfunction "A_A") (pintype "passive"))
      (node (ref "LED850") (pin "A") (pinfunction "A_A") (pintype "passive"))
      (node (ref "LED858") (pin "A") (pinfunction "A_A") (pintype "passive"))
      (node (ref "LED866") (pin "A") (pinfunction "A_A") (pintype "passive"))
      (node (ref "LED874") (pin "A") (pinfunction "A_A") (pintype "passive"))
      (node (ref "LED882") (pin "A") (pinfunction "A_A") (pintype "passive"))
      (node (ref "LED890") (pin "A") (pinfunction "A_A") (pintype "passive"))
      (node (ref "LED898") (pin "A") (pinfunction "A_A") (pintype "passive"))
      (node (ref "LED906") (pin "A") (pinfunction "A_A") (pintype "passive"))
      (node (ref "LED914") (pin "A") (pinfunction "A_A") (pintype "passive"))
      (node (ref "LED922") (pin "A") (pinfunction "A_A") (pintype "passive"))
      (node (ref "LED930") (pin "A") (pinfunction "A_A") (pintype "passive"))
      (node (ref "LED938") (pin "A") (pinfunction "A_A") (pintype "passive"))
      (node (ref "LED946") (pin "A") (pinfunction "A_A") (pintype "passive"))
      (node (ref "LED954") (pin "A") (pinfunction "A_A") (pintype "passive"))
      (node (ref "LED962") (pin "A") (pinfunction "A_A") (pintype "passive"))
      (node (ref "LED970") (pin "A") (pinfunction "A_A") (pintype "passive"))
      (node (ref "LED978") (pin "A") (pinfunction "A_A") (pintype "passive"))
      (node (ref "LED986") (pin "A") (pinfunction "A_A") (pintype "passive"))
      (node (ref "LED994") (pin "A") (pinfunction "A_A") (pintype "passive"))
      (node (ref "U$3") (pin "P$5") (pinfunction "P$5_P$5") (pintype "bidirectional"))
    )
    (net (code "53") (name "Net-(LED1003-PadA)") (class "Default")
      (node (ref "LED1003") (pin "A") (pinfunction "A_A") (pintype "passive"))
      (node (ref "LED1011") (pin "A") (pinfunction "A_A") (pintype "passive"))
      (node (ref "LED707") (pin "A") (pinfunction "A_A") (pintype "passive"))
      (node (ref "LED715") (pin "A") (pinfunction "A_A") (pintype "passive"))
      (node (ref "LED723") (pin "A") (pinfunction "A_A") (pintype "passive"))
      (node (ref "LED731") (pin "A") (pinfunction "A_A") (pintype "passive"))
      (node (ref "LED739") (pin "A") (pinfunction "A_A") (pintype "passive"))
      (node (ref "LED747") (pin "A") (pinfunction "A_A") (pintype "passive"))
      (node (ref "LED755") (pin "A") (pinfunction "A_A") (pintype "passive"))
      (node (ref "LED763") (pin "A") (pinfunction "A_A") (pintype "passive"))
      (node (ref "LED771") (pin "A") (pinfunction "A_A") (pintype "passive"))
      (node (ref "LED779") (pin "A") (pinfunction "A_A") (pintype "passive"))
      (node (ref "LED787") (pin "A") (pinfunction "A_A") (pintype "passive"))
      (node (ref "LED795") (pin "A") (pinfunction "A_A") (pintype "passive"))
      (node (ref "LED803") (pin "A") (pinfunction "A_A") (pintype "passive"))
      (node (ref "LED811") (pin "A") (pinfunction "A_A") (pintype "passive"))
      (node (ref "LED819") (pin "A") (pinfunction "A_A") (pintype "passive"))
      (node (ref "LED827") (pin "A") (pinfunction "A_A") (pintype "passive"))
      (node (ref "LED835") (pin "A") (pinfunction "A_A") (pintype "passive"))
      (node (ref "LED843") (pin "A") (pinfunction "A_A") (pintype "passive"))
      (node (ref "LED851") (pin "A") (pinfunction "A_A") (pintype "passive"))
      (node (ref "LED859") (pin "A") (pinfunction "A_A") (pintype "passive"))
      (node (ref "LED867") (pin "A") (pinfunction "A_A") (pintype "passive"))
      (node (ref "LED875") (pin "A") (pinfunction "A_A") (pintype "passive"))
      (node (ref "LED883") (pin "A") (pinfunction "A_A") (pintype "passive"))
      (node (ref "LED891") (pin "A") (pinfunction "A_A") (pintype "passive"))
      (node (ref "LED899") (pin "A") (pinfunction "A_A") (pintype "passive"))
      (node (ref "LED907") (pin "A") (pinfunction "A_A") (pintype "passive"))
      (node (ref "LED915") (pin "A") (pinfunction "A_A") (pintype "passive"))
      (node (ref "LED923") (pin "A") (pinfunction "A_A") (pintype "passive"))
      (node (ref "LED931") (pin "A") (pinfunction "A_A") (pintype "passive"))
      (node (ref "LED939") (pin "A") (pinfunction "A_A") (pintype "passive"))
      (node (ref "LED947") (pin "A") (pinfunction "A_A") (pintype "passive"))
      (node (ref "LED955") (pin "A") (pinfunction "A_A") (pintype "passive"))
      (node (ref "LED963") (pin "A") (pinfunction "A_A") (pintype "passive"))
      (node (ref "LED971") (pin "A") (pinfunction "A_A") (pintype "passive"))
      (node (ref "LED979") (pin "A") (pinfunction "A_A") (pintype "passive"))
      (node (ref "LED987") (pin "A") (pinfunction "A_A") (pintype "passive"))
      (node (ref "LED995") (pin "A") (pinfunction "A_A") (pintype "passive"))
      (node (ref "U$3") (pin "P$4") (pinfunction "P$4_P$4") (pintype "bidirectional"))
    )
    (net (code "54") (name "Net-(LED1004-PadA)") (class "Default")
      (node (ref "LED1004") (pin "A") (pinfunction "A_A") (pintype "passive"))
      (node (ref "LED1012") (pin "A") (pinfunction "A_A") (pintype "passive"))
      (node (ref "LED708") (pin "A") (pinfunction "A_A") (pintype "passive"))
      (node (ref "LED716") (pin "A") (pinfunction "A_A") (pintype "passive"))
      (node (ref "LED724") (pin "A") (pinfunction "A_A") (pintype "passive"))
      (node (ref "LED732") (pin "A") (pinfunction "A_A") (pintype "passive"))
      (node (ref "LED740") (pin "A") (pinfunction "A_A") (pintype "passive"))
      (node (ref "LED748") (pin "A") (pinfunction "A_A") (pintype "passive"))
      (node (ref "LED756") (pin "A") (pinfunction "A_A") (pintype "passive"))
      (node (ref "LED764") (pin "A") (pinfunction "A_A") (pintype "passive"))
      (node (ref "LED772") (pin "A") (pinfunction "A_A") (pintype "passive"))
      (node (ref "LED780") (pin "A") (pinfunction "A_A") (pintype "passive"))
      (node (ref "LED788") (pin "A") (pinfunction "A_A") (pintype "passive"))
      (node (ref "LED796") (pin "A") (pinfunction "A_A") (pintype "passive"))
      (node (ref "LED804") (pin "A") (pinfunction "A_A") (pintype "passive"))
      (node (ref "LED812") (pin "A") (pinfunction "A_A") (pintype "passive"))
      (node (ref "LED820") (pin "A") (pinfunction "A_A") (pintype "passive"))
      (node (ref "LED828") (pin "A") (pinfunction "A_A") (pintype "passive"))
      (node (ref "LED836") (pin "A") (pinfunction "A_A") (pintype "passive"))
      (node (ref "LED844") (pin "A") (pinfunction "A_A") (pintype "passive"))
      (node (ref "LED852") (pin "A") (pinfunction "A_A") (pintype "passive"))
      (node (ref "LED860") (pin "A") (pinfunction "A_A") (pintype "passive"))
      (node (ref "LED868") (pin "A") (pinfunction "A_A") (pintype "passive"))
      (node (ref "LED876") (pin "A") (pinfunction "A_A") (pintype "passive"))
      (node (ref "LED884") (pin "A") (pinfunction "A_A") (pintype "passive"))
      (node (ref "LED892") (pin "A") (pinfunction "A_A") (pintype "passive"))
      (node (ref "LED900") (pin "A") (pinfunction "A_A") (pintype "passive"))
      (node (ref "LED908") (pin "A") (pinfunction "A_A") (pintype "passive"))
      (node (ref "LED916") (pin "A") (pinfunction "A_A") (pintype "passive"))
      (node (ref "LED924") (pin "A") (pinfunction "A_A") (pintype "passive"))
      (node (ref "LED932") (pin "A") (pinfunction "A_A") (pintype "passive"))
      (node (ref "LED940") (pin "A") (pinfunction "A_A") (pintype "passive"))
      (node (ref "LED948") (pin "A") (pinfunction "A_A") (pintype "passive"))
      (node (ref "LED956") (pin "A") (pinfunction "A_A") (pintype "passive"))
      (node (ref "LED964") (pin "A") (pinfunction "A_A") (pintype "passive"))
      (node (ref "LED972") (pin "A") (pinfunction "A_A") (pintype "passive"))
      (node (ref "LED980") (pin "A") (pinfunction "A_A") (pintype "passive"))
      (node (ref "LED988") (pin "A") (pinfunction "A_A") (pintype "passive"))
      (node (ref "LED996") (pin "A") (pinfunction "A_A") (pintype "passive"))
      (node (ref "U$3") (pin "P$3") (pinfunction "P$3_P$3") (pintype "bidirectional"))
    )
    (net (code "55") (name "Net-(LED1005-PadA)") (class "Default")
      (node (ref "LED1005") (pin "A") (pinfunction "A_A") (pintype "passive"))
      (node (ref "LED1013") (pin "A") (pinfunction "A_A") (pintype "passive"))
      (node (ref "LED709") (pin "A") (pinfunction "A_A") (pintype "passive"))
      (node (ref "LED717") (pin "A") (pinfunction "A_A") (pintype "passive"))
      (node (ref "LED725") (pin "A") (pinfunction "A_A") (pintype "passive"))
      (node (ref "LED733") (pin "A") (pinfunction "A_A") (pintype "passive"))
      (node (ref "LED741") (pin "A") (pinfunction "A_A") (pintype "passive"))
      (node (ref "LED749") (pin "A") (pinfunction "A_A") (pintype "passive"))
      (node (ref "LED757") (pin "A") (pinfunction "A_A") (pintype "passive"))
      (node (ref "LED765") (pin "A") (pinfunction "A_A") (pintype "passive"))
      (node (ref "LED773") (pin "A") (pinfunction "A_A") (pintype "passive"))
      (node (ref "LED781") (pin "A") (pinfunction "A_A") (pintype "passive"))
      (node (ref "LED789") (pin "A") (pinfunction "A_A") (pintype "passive"))
      (node (ref "LED797") (pin "A") (pinfunction "A_A") (pintype "passive"))
      (node (ref "LED805") (pin "A") (pinfunction "A_A") (pintype "passive"))
      (node (ref "LED813") (pin "A") (pinfunction "A_A") (pintype "passive"))
      (node (ref "LED821") (pin "A") (pinfunction "A_A") (pintype "passive"))
      (node (ref "LED829") (pin "A") (pinfunction "A_A") (pintype "passive"))
      (node (ref "LED837") (pin "A") (pinfunction "A_A") (pintype "passive"))
      (node (ref "LED845") (pin "A") (pinfunction "A_A") (pintype "passive"))
      (node (ref "LED853") (pin "A") (pinfunction "A_A") (pintype "passive"))
      (node (ref "LED861") (pin "A") (pinfunction "A_A") (pintype "passive"))
      (node (ref "LED869") (pin "A") (pinfunction "A_A") (pintype "passive"))
      (node (ref "LED877") (pin "A") (pinfunction "A_A") (pintype "passive"))
      (node (ref "LED885") (pin "A") (pinfunction "A_A") (pintype "passive"))
      (node (ref "LED893") (pin "A") (pinfunction "A_A") (pintype "passive"))
      (node (ref "LED901") (pin "A") (pinfunction "A_A") (pintype "passive"))
      (node (ref "LED909") (pin "A") (pinfunction "A_A") (pintype "passive"))
      (node (ref "LED917") (pin "A") (pinfunction "A_A") (pintype "passive"))
      (node (ref "LED925") (pin "A") (pinfunction "A_A") (pintype "passive"))
      (node (ref "LED933") (pin "A") (pinfunction "A_A") (pintype "passive"))
      (node (ref "LED941") (pin "A") (pinfunction "A_A") (pintype "passive"))
      (node (ref "LED949") (pin "A") (pinfunction "A_A") (pintype "passive"))
      (node (ref "LED957") (pin "A") (pinfunction "A_A") (pintype "passive"))
      (node (ref "LED965") (pin "A") (pinfunction "A_A") (pintype "passive"))
      (node (ref "LED973") (pin "A") (pinfunction "A_A") (pintype "passive"))
      (node (ref "LED981") (pin "A") (pinfunction "A_A") (pintype "passive"))
      (node (ref "LED989") (pin "A") (pinfunction "A_A") (pintype "passive"))
      (node (ref "LED997") (pin "A") (pinfunction "A_A") (pintype "passive"))
      (node (ref "U$3") (pin "P$2") (pinfunction "P$2_P$2") (pintype "bidirectional"))
    )
    (net (code "56") (name "Net-(LED1006-PadA)") (class "Default")
      (node (ref "LED1006") (pin "A") (pinfunction "A_A") (pintype "passive"))
      (node (ref "LED1014") (pin "A") (pinfunction "A_A") (pintype "passive"))
      (node (ref "LED710") (pin "A") (pinfunction "A_A") (pintype "passive"))
      (node (ref "LED718") (pin "A") (pinfunction "A_A") (pintype "passive"))
      (node (ref "LED726") (pin "A") (pinfunction "A_A") (pintype "passive"))
      (node (ref "LED734") (pin "A") (pinfunction "A_A") (pintype "passive"))
      (node (ref "LED742") (pin "A") (pinfunction "A_A") (pintype "passive"))
      (node (ref "LED750") (pin "A") (pinfunction "A_A") (pintype "passive"))
      (node (ref "LED758") (pin "A") (pinfunction "A_A") (pintype "passive"))
      (node (ref "LED766") (pin "A") (pinfunction "A_A") (pintype "passive"))
      (node (ref "LED774") (pin "A") (pinfunction "A_A") (pintype "passive"))
      (node (ref "LED782") (pin "A") (pinfunction "A_A") (pintype "passive"))
      (node (ref "LED790") (pin "A") (pinfunction "A_A") (pintype "passive"))
      (node (ref "LED798") (pin "A") (pinfunction "A_A") (pintype "passive"))
      (node (ref "LED806") (pin "A") (pinfunction "A_A") (pintype "passive"))
      (node (ref "LED814") (pin "A") (pinfunction "A_A") (pintype "passive"))
      (node (ref "LED822") (pin "A") (pinfunction "A_A") (pintype "passive"))
      (node (ref "LED830") (pin "A") (pinfunction "A_A") (pintype "passive"))
      (node (ref "LED838") (pin "A") (pinfunction "A_A") (pintype "passive"))
      (node (ref "LED846") (pin "A") (pinfunction "A_A") (pintype "passive"))
      (node (ref "LED854") (pin "A") (pinfunction "A_A") (pintype "passive"))
      (node (ref "LED862") (pin "A") (pinfunction "A_A") (pintype "passive"))
      (node (ref "LED870") (pin "A") (pinfunction "A_A") (pintype "passive"))
      (node (ref "LED878") (pin "A") (pinfunction "A_A") (pintype "passive"))
      (node (ref "LED886") (pin "A") (pinfunction "A_A") (pintype "passive"))
      (node (ref "LED894") (pin "A") (pinfunction "A_A") (pintype "passive"))
      (node (ref "LED902") (pin "A") (pinfunction "A_A") (pintype "passive"))
      (node (ref "LED910") (pin "A") (pinfunction "A_A") (pintype "passive"))
      (node (ref "LED918") (pin "A") (pinfunction "A_A") (pintype "passive"))
      (node (ref "LED926") (pin "A") (pinfunction "A_A") (pintype "passive"))
      (node (ref "LED934") (pin "A") (pinfunction "A_A") (pintype "passive"))
      (node (ref "LED942") (pin "A") (pinfunction "A_A") (pintype "passive"))
      (node (ref "LED950") (pin "A") (pinfunction "A_A") (pintype "passive"))
      (node (ref "LED958") (pin "A") (pinfunction "A_A") (pintype "passive"))
      (node (ref "LED966") (pin "A") (pinfunction "A_A") (pintype "passive"))
      (node (ref "LED974") (pin "A") (pinfunction "A_A") (pintype "passive"))
      (node (ref "LED982") (pin "A") (pinfunction "A_A") (pintype "passive"))
      (node (ref "LED990") (pin "A") (pinfunction "A_A") (pintype "passive"))
      (node (ref "LED998") (pin "A") (pinfunction "A_A") (pintype "passive"))
      (node (ref "U$3") (pin "P$1") (pinfunction "P$1_P$1") (pintype "bidirectional"))
    )
    (net (code "57") (name "Net-(LED1007-C)") (class "Default")
      (node (ref "LED1007") (pin "K") (pinfunction "C_K") (pintype "passive"))
      (node (ref "LED1008") (pin "K") (pinfunction "C_K") (pintype "passive"))
      (node (ref "LED1009") (pin "K") (pinfunction "C_K") (pintype "passive"))
      (node (ref "LED1010") (pin "K") (pinfunction "C_K") (pintype "passive"))
      (node (ref "LED1011") (pin "K") (pinfunction "C_K") (pintype "passive"))
      (node (ref "LED1012") (pin "K") (pinfunction "C_K") (pintype "passive"))
      (node (ref "LED1013") (pin "K") (pinfunction "C_K") (pintype "passive"))
      (node (ref "LED1014") (pin "K") (pinfunction "C_K") (pintype "passive"))
      (node (ref "LED1053") (pin "K") (pinfunction "C_K") (pintype "passive"))
      (node (ref "U$2") (pin "P$1") (pinfunction "P$1_P$1") (pintype "bidirectional"))
    )
    (net (code "58") (name "Net-(LED1007-PadA)") (class "Default")
      (node (ref "LED1007") (pin "A") (pinfunction "A_A") (pintype "passive"))
      (node (ref "LED703") (pin "A") (pinfunction "A_A") (pintype "passive"))
      (node (ref "LED711") (pin "A") (pinfunction "A_A") (pintype "passive"))
      (node (ref "LED719") (pin "A") (pinfunction "A_A") (pintype "passive"))
      (node (ref "LED727") (pin "A") (pinfunction "A_A") (pintype "passive"))
      (node (ref "LED735") (pin "A") (pinfunction "A_A") (pintype "passive"))
      (node (ref "LED743") (pin "A") (pinfunction "A_A") (pintype "passive"))
      (node (ref "LED751") (pin "A") (pinfunction "A_A") (pintype "passive"))
      (node (ref "LED759") (pin "A") (pinfunction "A_A") (pintype "passive"))
      (node (ref "LED767") (pin "A") (pinfunction "A_A") (pintype "passive"))
      (node (ref "LED775") (pin "A") (pinfunction "A_A") (pintype "passive"))
      (node (ref "LED783") (pin "A") (pinfunction "A_A") (pintype "passive"))
      (node (ref "LED791") (pin "A") (pinfunction "A_A") (pintype "passive"))
      (node (ref "LED799") (pin "A") (pinfunction "A_A") (pintype "passive"))
      (node (ref "LED807") (pin "A") (pinfunction "A_A") (pintype "passive"))
      (node (ref "LED815") (pin "A") (pinfunction "A_A") (pintype "passive"))
      (node (ref "LED823") (pin "A") (pinfunction "A_A") (pintype "passive"))
      (node (ref "LED831") (pin "A") (pinfunction "A_A") (pintype "passive"))
      (node (ref "LED839") (pin "A") (pinfunction "A_A") (pintype "passive"))
      (node (ref "LED847") (pin "A") (pinfunction "A_A") (pintype "passive"))
      (node (ref "LED855") (pin "A") (pinfunction "A_A") (pintype "passive"))
      (node (ref "LED863") (pin "A") (pinfunction "A_A") (pintype "passive"))
      (node (ref "LED871") (pin "A") (pinfunction "A_A") (pintype "passive"))
      (node (ref "LED879") (pin "A") (pinfunction "A_A") (pintype "passive"))
      (node (ref "LED887") (pin "A") (pinfunction "A_A") (pintype "passive"))
      (node (ref "LED895") (pin "A") (pinfunction "A_A") (pintype "passive"))
      (node (ref "LED903") (pin "A") (pinfunction "A_A") (pintype "passive"))
      (node (ref "LED911") (pin "A") (pinfunction "A_A") (pintype "passive"))
      (node (ref "LED919") (pin "A") (pinfunction "A_A") (pintype "passive"))
      (node (ref "LED927") (pin "A") (pinfunction "A_A") (pintype "passive"))
      (node (ref "LED935") (pin "A") (pinfunction "A_A") (pintype "passive"))
      (node (ref "LED943") (pin "A") (pinfunction "A_A") (pintype "passive"))
      (node (ref "LED951") (pin "A") (pinfunction "A_A") (pintype "passive"))
      (node (ref "LED959") (pin "A") (pinfunction "A_A") (pintype "passive"))
      (node (ref "LED967") (pin "A") (pinfunction "A_A") (pintype "passive"))
      (node (ref "LED975") (pin "A") (pinfunction "A_A") (pintype "passive"))
      (node (ref "LED983") (pin "A") (pinfunction "A_A") (pintype "passive"))
      (node (ref "LED991") (pin "A") (pinfunction "A_A") (pintype "passive"))
      (node (ref "LED999") (pin "A") (pinfunction "A_A") (pintype "passive"))
      (node (ref "U$3") (pin "P$8") (pinfunction "P$8_P$8") (pintype "bidirectional"))
    )
    (net (code "59") (name "Net-(LED1015-C)") (class "Default")
      (node (ref "LED1015") (pin "K") (pinfunction "C_K") (pintype "passive"))
      (node (ref "LED703") (pin "K") (pinfunction "C_K") (pintype "passive"))
      (node (ref "LED704") (pin "K") (pinfunction "C_K") (pintype "passive"))
      (node (ref "LED705") (pin "K") (pinfunction "C_K") (pintype "passive"))
      (node (ref "LED706") (pin "K") (pinfunction "C_K") (pintype "passive"))
      (node (ref "LED707") (pin "K") (pinfunction "C_K") (pintype "passive"))
      (node (ref "LED708") (pin "K") (pinfunction "C_K") (pintype "passive"))
      (node (ref "LED709") (pin "K") (pinfunction "C_K") (pintype "passive"))
      (node (ref "LED710") (pin "K") (pinfunction "C_K") (pintype "passive"))
      (node (ref "U$2") (pin "P$39") (pinfunction "P$39_P$39") (pintype "bidirectional"))
    )
    (net (code "60") (name "Net-(LED1015-PadA)") (class "Default")
      (node (ref "LED1015") (pin "A") (pinfunction "A_A") (pintype "passive"))
      (node (ref "LED1016") (pin "A") (pinfunction "A_A") (pintype "passive"))
      (node (ref "LED1017") (pin "A") (pinfunction "A_A") (pintype "passive"))
      (node (ref "LED1018") (pin "A") (pinfunction "A_A") (pintype "passive"))
      (node (ref "LED1019") (pin "A") (pinfunction "A_A") (pintype "passive"))
      (node (ref "LED1020") (pin "A") (pinfunction "A_A") (pintype "passive"))
      (node (ref "LED1021") (pin "A") (pinfunction "A_A") (pintype "passive"))
      (node (ref "LED1022") (pin "A") (pinfunction "A_A") (pintype "passive"))
      (node (ref "LED1023") (pin "A") (pinfunction "A_A") (pintype "passive"))
      (node (ref "LED1024") (pin "A") (pinfunction "A_A") (pintype "passive"))
      (node (ref "LED1025") (pin "A") (pinfunction "A_A") (pintype "passive"))
      (node (ref "LED1026") (pin "A") (pinfunction "A_A") (pintype "passive"))
      (node (ref "LED1027") (pin "A") (pinfunction "A_A") (pintype "passive"))
      (node (ref "LED1028") (pin "A") (pinfunction "A_A") (pintype "passive"))
      (node (ref "LED1029") (pin "A") (pinfunction "A_A") (pintype "passive"))
      (node (ref "LED1030") (pin "A") (pinfunction "A_A") (pintype "passive"))
      (node (ref "LED1031") (pin "A") (pinfunction "A_A") (pintype "passive"))
      (node (ref "LED1032") (pin "A") (pinfunction "A_A") (pintype "passive"))
      (node (ref "LED1033") (pin "A") (pinfunction "A_A") (pintype "passive"))
      (node (ref "LED1034") (pin "A") (pinfunction "A_A") (pintype "passive"))
      (node (ref "LED1035") (pin "A") (pinfunction "A_A") (pintype "passive"))
      (node (ref "LED1036") (pin "A") (pinfunction "A_A") (pintype "passive"))
      (node (ref "LED1037") (pin "A") (pinfunction "A_A") (pintype "passive"))
      (node (ref "LED1038") (pin "A") (pinfunction "A_A") (pintype "passive"))
      (node (ref "LED1039") (pin "A") (pinfunction "A_A") (pintype "passive"))
      (node (ref "LED1040") (pin "A") (pinfunction "A_A") (pintype "passive"))
      (node (ref "LED1041") (pin "A") (pinfunction "A_A") (pintype "passive"))
      (node (ref "LED1042") (pin "A") (pinfunction "A_A") (pintype "passive"))
      (node (ref "LED1043") (pin "A") (pinfunction "A_A") (pintype "passive"))
      (node (ref "LED1044") (pin "A") (pinfunction "A_A") (pintype "passive"))
      (node (ref "LED1045") (pin "A") (pinfunction "A_A") (pintype "passive"))
      (node (ref "LED1046") (pin "A") (pinfunction "A_A") (pintype "passive"))
      (node (ref "LED1047") (pin "A") (pinfunction "A_A") (pintype "passive"))
      (node (ref "LED1048") (pin "A") (pinfunction "A_A") (pintype "passive"))
      (node (ref "LED1049") (pin "A") (pinfunction "A_A") (pintype "passive"))
      (node (ref "LED1050") (pin "A") (pinfunction "A_A") (pintype "passive"))
      (node (ref "LED1051") (pin "A") (pinfunction "A_A") (pintype "passive"))
      (node (ref "LED1052") (pin "A") (pinfunction "A_A") (pintype "passive"))
      (node (ref "LED1053") (pin "A") (pinfunction "A_A") (pintype "passive"))
      (node (ref "U$3") (pin "P$9") (pinfunction "P$9_P$9") (pintype "bidirectional"))
    )
    (net (code "61") (name "Net-(LED1016-C)") (class "Default")
      (node (ref "LED1016") (pin "K") (pinfunction "C_K") (pintype "passive"))
      (node (ref "LED711") (pin "K") (pinfunction "C_K") (pintype "passive"))
      (node (ref "LED712") (pin "K") (pinfunction "C_K") (pintype "passive"))
      (node (ref "LED713") (pin "K") (pinfunction "C_K") (pintype "passive"))
      (node (ref "LED714") (pin "K") (pinfunction "C_K") (pintype "passive"))
      (node (ref "LED715") (pin "K") (pinfunction "C_K") (pintype "passive"))
      (node (ref "LED716") (pin "K") (pinfunction "C_K") (pintype "passive"))
      (node (ref "LED717") (pin "K") (pinfunction "C_K") (pintype "passive"))
      (node (ref "LED718") (pin "K") (pinfunction "C_K") (pintype "passive"))
      (node (ref "U$2") (pin "P$38") (pinfunction "P$38_P$38") (pintype "bidirectional"))
    )
    (net (code "62") (name "Net-(LED1017-C)") (class "Default")
      (node (ref "LED1017") (pin "K") (pinfunction "C_K") (pintype "passive"))
      (node (ref "LED719") (pin "K") (pinfunction "C_K") (pintype "passive"))
      (node (ref "LED720") (pin "K") (pinfunction "C_K") (pintype "passive"))
      (node (ref "LED721") (pin "K") (pinfunction "C_K") (pintype "passive"))
      (node (ref "LED722") (pin "K") (pinfunction "C_K") (pintype "passive"))
      (node (ref "LED723") (pin "K") (pinfunction "C_K") (pintype "passive"))
      (node (ref "LED724") (pin "K") (pinfunction "C_K") (pintype "passive"))
      (node (ref "LED725") (pin "K") (pinfunction "C_K") (pintype "passive"))
      (node (ref "LED726") (pin "K") (pinfunction "C_K") (pintype "passive"))
      (node (ref "U$2") (pin "P$37") (pinfunction "P$37_P$37") (pintype "bidirectional"))
    )
    (net (code "63") (name "Net-(LED1018-C)") (class "Default")
      (node (ref "LED1018") (pin "K") (pinfunction "C_K") (pintype "passive"))
      (node (ref "LED727") (pin "K") (pinfunction "C_K") (pintype "passive"))
      (node (ref "LED728") (pin "K") (pinfunction "C_K") (pintype "passive"))
      (node (ref "LED729") (pin "K") (pinfunction "C_K") (pintype "passive"))
      (node (ref "LED730") (pin "K") (pinfunction "C_K") (pintype "passive"))
      (node (ref "LED731") (pin "K") (pinfunction "C_K") (pintype "passive"))
      (node (ref "LED732") (pin "K") (pinfunction "C_K") (pintype "passive"))
      (node (ref "LED733") (pin "K") (pinfunction "C_K") (pintype "passive"))
      (node (ref "LED734") (pin "K") (pinfunction "C_K") (pintype "passive"))
      (node (ref "U$2") (pin "P$36") (pinfunction "P$36_P$36") (pintype "bidirectional"))
    )
    (net (code "64") (name "Net-(LED1019-C)") (class "Default")
      (node (ref "LED1019") (pin "K") (pinfunction "C_K") (pintype "passive"))
      (node (ref "LED735") (pin "K") (pinfunction "C_K") (pintype "passive"))
      (node (ref "LED736") (pin "K") (pinfunction "C_K") (pintype "passive"))
      (node (ref "LED737") (pin "K") (pinfunction "C_K") (pintype "passive"))
      (node (ref "LED738") (pin "K") (pinfunction "C_K") (pintype "passive"))
      (node (ref "LED739") (pin "K") (pinfunction "C_K") (pintype "passive"))
      (node (ref "LED740") (pin "K") (pinfunction "C_K") (pintype "passive"))
      (node (ref "LED741") (pin "K") (pinfunction "C_K") (pintype "passive"))
      (node (ref "LED742") (pin "K") (pinfunction "C_K") (pintype "passive"))
      (node (ref "U$2") (pin "P$35") (pinfunction "P$35_P$35") (pintype "bidirectional"))
    )
    (net (code "65") (name "Net-(LED1020-C)") (class "Default")
      (node (ref "LED1020") (pin "K") (pinfunction "C_K") (pintype "passive"))
      (node (ref "LED743") (pin "K") (pinfunction "C_K") (pintype "passive"))
      (node (ref "LED744") (pin "K") (pinfunction "C_K") (pintype "passive"))
      (node (ref "LED745") (pin "K") (pinfunction "C_K") (pintype "passive"))
      (node (ref "LED746") (pin "K") (pinfunction "C_K") (pintype "passive"))
      (node (ref "LED747") (pin "K") (pinfunction "C_K") (pintype "passive"))
      (node (ref "LED748") (pin "K") (pinfunction "C_K") (pintype "passive"))
      (node (ref "LED749") (pin "K") (pinfunction "C_K") (pintype "passive"))
      (node (ref "LED750") (pin "K") (pinfunction "C_K") (pintype "passive"))
      (node (ref "U$2") (pin "P$34") (pinfunction "P$34_P$34") (pintype "bidirectional"))
    )
    (net (code "66") (name "Net-(LED1021-C)") (class "Default")
      (node (ref "LED1021") (pin "K") (pinfunction "C_K") (pintype "passive"))
      (node (ref "LED751") (pin "K") (pinfunction "C_K") (pintype "passive"))
      (node (ref "LED752") (pin "K") (pinfunction "C_K") (pintype "passive"))
      (node (ref "LED753") (pin "K") (pinfunction "C_K") (pintype "passive"))
      (node (ref "LED754") (pin "K") (pinfunction "C_K") (pintype "passive"))
      (node (ref "LED755") (pin "K") (pinfunction "C_K") (pintype "passive"))
      (node (ref "LED756") (pin "K") (pinfunction "C_K") (pintype "passive"))
      (node (ref "LED757") (pin "K") (pinfunction "C_K") (pintype "passive"))
      (node (ref "LED758") (pin "K") (pinfunction "C_K") (pintype "passive"))
      (node (ref "U$2") (pin "P$33") (pinfunction "P$33_P$33") (pintype "bidirectional"))
    )
    (net (code "67") (name "Net-(LED1022-C)") (class "Default")
      (node (ref "LED1022") (pin "K") (pinfunction "C_K") (pintype "passive"))
      (node (ref "LED759") (pin "K") (pinfunction "C_K") (pintype "passive"))
      (node (ref "LED760") (pin "K") (pinfunction "C_K") (pintype "passive"))
      (node (ref "LED761") (pin "K") (pinfunction "C_K") (pintype "passive"))
      (node (ref "LED762") (pin "K") (pinfunction "C_K") (pintype "passive"))
      (node (ref "LED763") (pin "K") (pinfunction "C_K") (pintype "passive"))
      (node (ref "LED764") (pin "K") (pinfunction "C_K") (pintype "passive"))
      (node (ref "LED765") (pin "K") (pinfunction "C_K") (pintype "passive"))
      (node (ref "LED766") (pin "K") (pinfunction "C_K") (pintype "passive"))
      (node (ref "U$2") (pin "P$32") (pinfunction "P$32_P$32") (pintype "bidirectional"))
    )
    (net (code "68") (name "Net-(LED1023-C)") (class "Default")
      (node (ref "LED1023") (pin "K") (pinfunction "C_K") (pintype "passive"))
      (node (ref "LED767") (pin "K") (pinfunction "C_K") (pintype "passive"))
      (node (ref "LED768") (pin "K") (pinfunction "C_K") (pintype "passive"))
      (node (ref "LED769") (pin "K") (pinfunction "C_K") (pintype "passive"))
      (node (ref "LED770") (pin "K") (pinfunction "C_K") (pintype "passive"))
      (node (ref "LED771") (pin "K") (pinfunction "C_K") (pintype "passive"))
      (node (ref "LED772") (pin "K") (pinfunction "C_K") (pintype "passive"))
      (node (ref "LED773") (pin "K") (pinfunction "C_K") (pintype "passive"))
      (node (ref "LED774") (pin "K") (pinfunction "C_K") (pintype "passive"))
      (node (ref "U$2") (pin "P$31") (pinfunction "P$31_P$31") (pintype "bidirectional"))
    )
    (net (code "69") (name "Net-(LED1024-C)") (class "Default")
      (node (ref "LED1024") (pin "K") (pinfunction "C_K") (pintype "passive"))
      (node (ref "LED775") (pin "K") (pinfunction "C_K") (pintype "passive"))
      (node (ref "LED776") (pin "K") (pinfunction "C_K") (pintype "passive"))
      (node (ref "LED777") (pin "K") (pinfunction "C_K") (pintype "passive"))
      (node (ref "LED778") (pin "K") (pinfunction "C_K") (pintype "passive"))
      (node (ref "LED779") (pin "K") (pinfunction "C_K") (pintype "passive"))
      (node (ref "LED780") (pin "K") (pinfunction "C_K") (pintype "passive"))
      (node (ref "LED781") (pin "K") (pinfunction "C_K") (pintype "passive"))
      (node (ref "LED782") (pin "K") (pinfunction "C_K") (pintype "passive"))
      (node (ref "U$2") (pin "P$30") (pinfunction "P$30_P$30") (pintype "bidirectional"))
    )
    (net (code "70") (name "Net-(LED1025-C)") (class "Default")
      (node (ref "LED1025") (pin "K") (pinfunction "C_K") (pintype "passive"))
      (node (ref "LED783") (pin "K") (pinfunction "C_K") (pintype "passive"))
      (node (ref "LED784") (pin "K") (pinfunction "C_K") (pintype "passive"))
      (node (ref "LED785") (pin "K") (pinfunction "C_K") (pintype "passive"))
      (node (ref "LED786") (pin "K") (pinfunction "C_K") (pintype "passive"))
      (node (ref "LED787") (pin "K") (pinfunction "C_K") (pintype "passive"))
      (node (ref "LED788") (pin "K") (pinfunction "C_K") (pintype "passive"))
      (node (ref "LED789") (pin "K") (pinfunction "C_K") (pintype "passive"))
      (node (ref "LED790") (pin "K") (pinfunction "C_K") (pintype "passive"))
      (node (ref "U$2") (pin "P$29") (pinfunction "P$29_P$29") (pintype "bidirectional"))
    )
    (net (code "71") (name "Net-(LED1026-C)") (class "Default")
      (node (ref "LED1026") (pin "K") (pinfunction "C_K") (pintype "passive"))
      (node (ref "LED791") (pin "K") (pinfunction "C_K") (pintype "passive"))
      (node (ref "LED792") (pin "K") (pinfunction "C_K") (pintype "passive"))
      (node (ref "LED793") (pin "K") (pinfunction "C_K") (pintype "passive"))
      (node (ref "LED794") (pin "K") (pinfunction "C_K") (pintype "passive"))
      (node (ref "LED795") (pin "K") (pinfunction "C_K") (pintype "passive"))
      (node (ref "LED796") (pin "K") (pinfunction "C_K") (pintype "passive"))
      (node (ref "LED797") (pin "K") (pinfunction "C_K") (pintype "passive"))
      (node (ref "LED798") (pin "K") (pinfunction "C_K") (pintype "passive"))
      (node (ref "U$2") (pin "P$28") (pinfunction "P$28_P$28") (pintype "bidirectional"))
    )
    (net (code "72") (name "Net-(LED1027-C)") (class "Default")
      (node (ref "LED1027") (pin "K") (pinfunction "C_K") (pintype "passive"))
      (node (ref "LED799") (pin "K") (pinfunction "C_K") (pintype "passive"))
      (node (ref "LED800") (pin "K") (pinfunction "C_K") (pintype "passive"))
      (node (ref "LED801") (pin "K") (pinfunction "C_K") (pintype "passive"))
      (node (ref "LED802") (pin "K") (pinfunction "C_K") (pintype "passive"))
      (node (ref "LED803") (pin "K") (pinfunction "C_K") (pintype "passive"))
      (node (ref "LED804") (pin "K") (pinfunction "C_K") (pintype "passive"))
      (node (ref "LED805") (pin "K") (pinfunction "C_K") (pintype "passive"))
      (node (ref "LED806") (pin "K") (pinfunction "C_K") (pintype "passive"))
      (node (ref "U$2") (pin "P$27") (pinfunction "P$27_P$27") (pintype "bidirectional"))
    )
    (net (code "73") (name "Net-(LED1028-C)") (class "Default")
      (node (ref "LED1028") (pin "K") (pinfunction "C_K") (pintype "passive"))
      (node (ref "LED807") (pin "K") (pinfunction "C_K") (pintype "passive"))
      (node (ref "LED808") (pin "K") (pinfunction "C_K") (pintype "passive"))
      (node (ref "LED809") (pin "K") (pinfunction "C_K") (pintype "passive"))
      (node (ref "LED810") (pin "K") (pinfunction "C_K") (pintype "passive"))
      (node (ref "LED811") (pin "K") (pinfunction "C_K") (pintype "passive"))
      (node (ref "LED812") (pin "K") (pinfunction "C_K") (pintype "passive"))
      (node (ref "LED813") (pin "K") (pinfunction "C_K") (pintype "passive"))
      (node (ref "LED814") (pin "K") (pinfunction "C_K") (pintype "passive"))
      (node (ref "U$2") (pin "P$26") (pinfunction "P$26_P$26") (pintype "bidirectional"))
    )
    (net (code "74") (name "Net-(LED1029-C)") (class "Default")
      (node (ref "LED1029") (pin "K") (pinfunction "C_K") (pintype "passive"))
      (node (ref "LED815") (pin "K") (pinfunction "C_K") (pintype "passive"))
      (node (ref "LED816") (pin "K") (pinfunction "C_K") (pintype "passive"))
      (node (ref "LED817") (pin "K") (pinfunction "C_K") (pintype "passive"))
      (node (ref "LED818") (pin "K") (pinfunction "C_K") (pintype "passive"))
      (node (ref "LED819") (pin "K") (pinfunction "C_K") (pintype "passive"))
      (node (ref "LED820") (pin "K") (pinfunction "C_K") (pintype "passive"))
      (node (ref "LED821") (pin "K") (pinfunction "C_K") (pintype "passive"))
      (node (ref "LED822") (pin "K") (pinfunction "C_K") (pintype "passive"))
      (node (ref "U$2") (pin "P$25") (pinfunction "P$25_P$25") (pintype "bidirectional"))
    )
    (net (code "75") (name "Net-(LED1030-C)") (class "Default")
      (node (ref "LED1030") (pin "K") (pinfunction "C_K") (pintype "passive"))
      (node (ref "LED823") (pin "K") (pinfunction "C_K") (pintype "passive"))
      (node (ref "LED824") (pin "K") (pinfunction "C_K") (pintype "passive"))
      (node (ref "LED825") (pin "K") (pinfunction "C_K") (pintype "passive"))
      (node (ref "LED826") (pin "K") (pinfunction "C_K") (pintype "passive"))
      (node (ref "LED827") (pin "K") (pinfunction "C_K") (pintype "passive"))
      (node (ref "LED828") (pin "K") (pinfunction "C_K") (pintype "passive"))
      (node (ref "LED829") (pin "K") (pinfunction "C_K") (pintype "passive"))
      (node (ref "LED830") (pin "K") (pinfunction "C_K") (pintype "passive"))
      (node (ref "U$2") (pin "P$24") (pinfunction "P$24_P$24") (pintype "bidirectional"))
    )
    (net (code "76") (name "Net-(LED1031-C)") (class "Default")
      (node (ref "LED1031") (pin "K") (pinfunction "C_K") (pintype "passive"))
      (node (ref "LED831") (pin "K") (pinfunction "C_K") (pintype "passive"))
      (node (ref "LED832") (pin "K") (pinfunction "C_K") (pintype "passive"))
      (node (ref "LED833") (pin "K") (pinfunction "C_K") (pintype "passive"))
      (node (ref "LED834") (pin "K") (pinfunction "C_K") (pintype "passive"))
      (node (ref "LED835") (pin "K") (pinfunction "C_K") (pintype "passive"))
      (node (ref "LED836") (pin "K") (pinfunction "C_K") (pintype "passive"))
      (node (ref "LED837") (pin "K") (pinfunction "C_K") (pintype "passive"))
      (node (ref "LED838") (pin "K") (pinfunction "C_K") (pintype "passive"))
      (node (ref "U$2") (pin "P$23") (pinfunction "P$23_P$23") (pintype "bidirectional"))
    )
    (net (code "77") (name "Net-(LED1032-C)") (class "Default")
      (node (ref "LED1032") (pin "K") (pinfunction "C_K") (pintype "passive"))
      (node (ref "LED839") (pin "K") (pinfunction "C_K") (pintype "passive"))
      (node (ref "LED840") (pin "K") (pinfunction "C_K") (pintype "passive"))
      (node (ref "LED841") (pin "K") (pinfunction "C_K") (pintype "passive"))
      (node (ref "LED842") (pin "K") (pinfunction "C_K") (pintype "passive"))
      (node (ref "LED843") (pin "K") (pinfunction "C_K") (pintype "passive"))
      (node (ref "LED844") (pin "K") (pinfunction "C_K") (pintype "passive"))
      (node (ref "LED845") (pin "K") (pinfunction "C_K") (pintype "passive"))
      (node (ref "LED846") (pin "K") (pinfunction "C_K") (pintype "passive"))
      (node (ref "U$2") (pin "P$22") (pinfunction "P$22_P$22") (pintype "bidirectional"))
    )
    (net (code "78") (name "Net-(LED1033-C)") (class "Default")
      (node (ref "LED1033") (pin "K") (pinfunction "C_K") (pintype "passive"))
      (node (ref "LED847") (pin "K") (pinfunction "C_K") (pintype "passive"))
      (node (ref "LED848") (pin "K") (pinfunction "C_K") (pintype "passive"))
      (node (ref "LED849") (pin "K") (pinfunction "C_K") (pintype "passive"))
      (node (ref "LED850") (pin "K") (pinfunction "C_K") (pintype "passive"))
      (node (ref "LED851") (pin "K") (pinfunction "C_K") (pintype "passive"))
      (node (ref "LED852") (pin "K") (pinfunction "C_K") (pintype "passive"))
      (node (ref "LED853") (pin "K") (pinfunction "C_K") (pintype "passive"))
      (node (ref "LED854") (pin "K") (pinfunction "C_K") (pintype "passive"))
      (node (ref "U$2") (pin "P$21") (pinfunction "P$21_P$21") (pintype "bidirectional"))
    )
    (net (code "79") (name "Net-(LED1034-C)") (class "Default")
      (node (ref "LED1034") (pin "K") (pinfunction "C_K") (pintype "passive"))
      (node (ref "LED855") (pin "K") (pinfunction "C_K") (pintype "passive"))
      (node (ref "LED856") (pin "K") (pinfunction "C_K") (pintype "passive"))
      (node (ref "LED857") (pin "K") (pinfunction "C_K") (pintype "passive"))
      (node (ref "LED858") (pin "K") (pinfunction "C_K") (pintype "passive"))
      (node (ref "LED859") (pin "K") (pinfunction "C_K") (pintype "passive"))
      (node (ref "LED860") (pin "K") (pinfunction "C_K") (pintype "passive"))
      (node (ref "LED861") (pin "K") (pinfunction "C_K") (pintype "passive"))
      (node (ref "LED862") (pin "K") (pinfunction "C_K") (pintype "passive"))
      (node (ref "U$2") (pin "P$20") (pinfunction "P$20_P$20") (pintype "bidirectional"))
    )
    (net (code "80") (name "Net-(LED1035-C)") (class "Default")
      (node (ref "LED1035") (pin "K") (pinfunction "C_K") (pintype "passive"))
      (node (ref "LED863") (pin "K") (pinfunction "C_K") (pintype "passive"))
      (node (ref "LED864") (pin "K") (pinfunction "C_K") (pintype "passive"))
      (node (ref "LED865") (pin "K") (pinfunction "C_K") (pintype "passive"))
      (node (ref "LED866") (pin "K") (pinfunction "C_K") (pintype "passive"))
      (node (ref "LED867") (pin "K") (pinfunction "C_K") (pintype "passive"))
      (node (ref "LED868") (pin "K") (pinfunction "C_K") (pintype "passive"))
      (node (ref "LED869") (pin "K") (pinfunction "C_K") (pintype "passive"))
      (node (ref "LED870") (pin "K") (pinfunction "C_K") (pintype "passive"))
      (node (ref "U$2") (pin "P$19") (pinfunction "P$19_P$19") (pintype "bidirectional"))
    )
    (net (code "81") (name "Net-(LED1036-C)") (class "Default")
      (node (ref "LED1036") (pin "K") (pinfunction "C_K") (pintype "passive"))
      (node (ref "LED871") (pin "K") (pinfunction "C_K") (pintype "passive"))
      (node (ref "LED872") (pin "K") (pinfunction "C_K") (pintype "passive"))
      (node (ref "LED873") (pin "K") (pinfunction "C_K") (pintype "passive"))
      (node (ref "LED874") (pin "K") (pinfunction "C_K") (pintype "passive"))
      (node (ref "LED875") (pin "K") (pinfunction "C_K") (pintype "passive"))
      (node (ref "LED876") (pin "K") (pinfunction "C_K") (pintype "passive"))
      (node (ref "LED877") (pin "K") (pinfunction "C_K") (pintype "passive"))
      (node (ref "LED878") (pin "K") (pinfunction "C_K") (pintype "passive"))
      (node (ref "U$2") (pin "P$18") (pinfunction "P$18_P$18") (pintype "bidirectional"))
    )
    (net (code "82") (name "Net-(LED1037-C)") (class "Default")
      (node (ref "LED1037") (pin "K") (pinfunction "C_K") (pintype "passive"))
      (node (ref "LED879") (pin "K") (pinfunction "C_K") (pintype "passive"))
      (node (ref "LED880") (pin "K") (pinfunction "C_K") (pintype "passive"))
      (node (ref "LED881") (pin "K") (pinfunction "C_K") (pintype "passive"))
      (node (ref "LED882") (pin "K") (pinfunction "C_K") (pintype "passive"))
      (node (ref "LED883") (pin "K") (pinfunction "C_K") (pintype "passive"))
      (node (ref "LED884") (pin "K") (pinfunction "C_K") (pintype "passive"))
      (node (ref "LED885") (pin "K") (pinfunction "C_K") (pintype "passive"))
      (node (ref "LED886") (pin "K") (pinfunction "C_K") (pintype "passive"))
      (node (ref "U$2") (pin "P$17") (pinfunction "P$17_P$17") (pintype "bidirectional"))
    )
    (net (code "83") (name "Net-(LED1038-C)") (class "Default")
      (node (ref "LED1038") (pin "K") (pinfunction "C_K") (pintype "passive"))
      (node (ref "LED887") (pin "K") (pinfunction "C_K") (pintype "passive"))
      (node (ref "LED888") (pin "K") (pinfunction "C_K") (pintype "passive"))
      (node (ref "LED889") (pin "K") (pinfunction "C_K") (pintype "passive"))
      (node (ref "LED890") (pin "K") (pinfunction "C_K") (pintype "passive"))
      (node (ref "LED891") (pin "K") (pinfunction "C_K") (pintype "passive"))
      (node (ref "LED892") (pin "K") (pinfunction "C_K") (pintype "passive"))
      (node (ref "LED893") (pin "K") (pinfunction "C_K") (pintype "passive"))
      (node (ref "LED894") (pin "K") (pinfunction "C_K") (pintype "passive"))
      (node (ref "U$2") (pin "P$16") (pinfunction "P$16_P$16") (pintype "bidirectional"))
    )
    (net (code "84") (name "Net-(LED1039-C)") (class "Default")
      (node (ref "LED1039") (pin "K") (pinfunction "C_K") (pintype "passive"))
      (node (ref "LED895") (pin "K") (pinfunction "C_K") (pintype "passive"))
      (node (ref "LED896") (pin "K") (pinfunction "C_K") (pintype "passive"))
      (node (ref "LED897") (pin "K") (pinfunction "C_K") (pintype "passive"))
      (node (ref "LED898") (pin "K") (pinfunction "C_K") (pintype "passive"))
      (node (ref "LED899") (pin "K") (pinfunction "C_K") (pintype "passive"))
      (node (ref "LED900") (pin "K") (pinfunction "C_K") (pintype "passive"))
      (node (ref "LED901") (pin "K") (pinfunction "C_K") (pintype "passive"))
      (node (ref "LED902") (pin "K") (pinfunction "C_K") (pintype "passive"))
      (node (ref "U$2") (pin "P$15") (pinfunction "P$15_P$15") (pintype "bidirectional"))
    )
    (net (code "85") (name "Net-(LED1040-C)") (class "Default")
      (node (ref "LED1040") (pin "K") (pinfunction "C_K") (pintype "passive"))
      (node (ref "LED903") (pin "K") (pinfunction "C_K") (pintype "passive"))
      (node (ref "LED904") (pin "K") (pinfunction "C_K") (pintype "passive"))
      (node (ref "LED905") (pin "K") (pinfunction "C_K") (pintype "passive"))
      (node (ref "LED906") (pin "K") (pinfunction "C_K") (pintype "passive"))
      (node (ref "LED907") (pin "K") (pinfunction "C_K") (pintype "passive"))
      (node (ref "LED908") (pin "K") (pinfunction "C_K") (pintype "passive"))
      (node (ref "LED909") (pin "K") (pinfunction "C_K") (pintype "passive"))
      (node (ref "LED910") (pin "K") (pinfunction "C_K") (pintype "passive"))
      (node (ref "U$2") (pin "P$14") (pinfunction "P$14_P$14") (pintype "bidirectional"))
    )
    (net (code "86") (name "Net-(LED1041-C)") (class "Default")
      (node (ref "LED1041") (pin "K") (pinfunction "C_K") (pintype "passive"))
      (node (ref "LED911") (pin "K") (pinfunction "C_K") (pintype "passive"))
      (node (ref "LED912") (pin "K") (pinfunction "C_K") (pintype "passive"))
      (node (ref "LED913") (pin "K") (pinfunction "C_K") (pintype "passive"))
      (node (ref "LED914") (pin "K") (pinfunction "C_K") (pintype "passive"))
      (node (ref "LED915") (pin "K") (pinfunction "C_K") (pintype "passive"))
      (node (ref "LED916") (pin "K") (pinfunction "C_K") (pintype "passive"))
      (node (ref "LED917") (pin "K") (pinfunction "C_K") (pintype "passive"))
      (node (ref "LED918") (pin "K") (pinfunction "C_K") (pintype "passive"))
      (node (ref "U$2") (pin "P$13") (pinfunction "P$13_P$13") (pintype "bidirectional"))
    )
    (net (code "87") (name "Net-(LED1042-C)") (class "Default")
      (node (ref "LED1042") (pin "K") (pinfunction "C_K") (pintype "passive"))
      (node (ref "LED919") (pin "K") (pinfunction "C_K") (pintype "passive"))
      (node (ref "LED920") (pin "K") (pinfunction "C_K") (pintype "passive"))
      (node (ref "LED921") (pin "K") (pinfunction "C_K") (pintype "passive"))
      (node (ref "LED922") (pin "K") (pinfunction "C_K") (pintype "passive"))
      (node (ref "LED923") (pin "K") (pinfunction "C_K") (pintype "passive"))
      (node (ref "LED924") (pin "K") (pinfunction "C_K") (pintype "passive"))
      (node (ref "LED925") (pin "K") (pinfunction "C_K") (pintype "passive"))
      (node (ref "LED926") (pin "K") (pinfunction "C_K") (pintype "passive"))
      (node (ref "U$2") (pin "P$12") (pinfunction "P$12_P$12") (pintype "bidirectional"))
    )
    (net (code "88") (name "Net-(LED1043-C)") (class "Default")
      (node (ref "LED1043") (pin "K") (pinfunction "C_K") (pintype "passive"))
      (node (ref "LED927") (pin "K") (pinfunction "C_K") (pintype "passive"))
      (node (ref "LED928") (pin "K") (pinfunction "C_K") (pintype "passive"))
      (node (ref "LED929") (pin "K") (pinfunction "C_K") (pintype "passive"))
      (node (ref "LED930") (pin "K") (pinfunction "C_K") (pintype "passive"))
      (node (ref "LED931") (pin "K") (pinfunction "C_K") (pintype "passive"))
      (node (ref "LED932") (pin "K") (pinfunction "C_K") (pintype "passive"))
      (node (ref "LED933") (pin "K") (pinfunction "C_K") (pintype "passive"))
      (node (ref "LED934") (pin "K") (pinfunction "C_K") (pintype "passive"))
      (node (ref "U$2") (pin "P$11") (pinfunction "P$11_P$11") (pintype "bidirectional"))
    )
    (net (code "89") (name "Net-(LED1044-C)") (class "Default")
      (node (ref "LED1044") (pin "K") (pinfunction "C_K") (pintype "passive"))
      (node (ref "LED935") (pin "K") (pinfunction "C_K") (pintype "passive"))
      (node (ref "LED936") (pin "K") (pinfunction "C_K") (pintype "passive"))
      (node (ref "LED937") (pin "K") (pinfunction "C_K") (pintype "passive"))
      (node (ref "LED938") (pin "K") (pinfunction "C_K") (pintype "passive"))
      (node (ref "LED939") (pin "K") (pinfunction "C_K") (pintype "passive"))
      (node (ref "LED940") (pin "K") (pinfunction "C_K") (pintype "passive"))
      (node (ref "LED941") (pin "K") (pinfunction "C_K") (pintype "passive"))
      (node (ref "LED942") (pin "K") (pinfunction "C_K") (pintype "passive"))
      (node (ref "U$2") (pin "P$10") (pinfunction "P$10_P$10") (pintype "bidirectional"))
    )
    (net (code "90") (name "Net-(LED1045-C)") (class "Default")
      (node (ref "LED1045") (pin "K") (pinfunction "C_K") (pintype "passive"))
      (node (ref "LED943") (pin "K") (pinfunction "C_K") (pintype "passive"))
      (node (ref "LED944") (pin "K") (pinfunction "C_K") (pintype "passive"))
      (node (ref "LED945") (pin "K") (pinfunction "C_K") (pintype "passive"))
      (node (ref "LED946") (pin "K") (pinfunction "C_K") (pintype "passive"))
      (node (ref "LED947") (pin "K") (pinfunction "C_K") (pintype "passive"))
      (node (ref "LED948") (pin "K") (pinfunction "C_K") (pintype "passive"))
      (node (ref "LED949") (pin "K") (pinfunction "C_K") (pintype "passive"))
      (node (ref "LED950") (pin "K") (pinfunction "C_K") (pintype "passive"))
      (node (ref "U$2") (pin "P$9") (pinfunction "P$9_P$9") (pintype "bidirectional"))
    )
    (net (code "91") (name "Net-(LED1046-C)") (class "Default")
      (node (ref "LED1046") (pin "K") (pinfunction "C_K") (pintype "passive"))
      (node (ref "LED951") (pin "K") (pinfunction "C_K") (pintype "passive"))
      (node (ref "LED952") (pin "K") (pinfunction "C_K") (pintype "passive"))
      (node (ref "LED953") (pin "K") (pinfunction "C_K") (pintype "passive"))
      (node (ref "LED954") (pin "K") (pinfunction "C_K") (pintype "passive"))
      (node (ref "LED955") (pin "K") (pinfunction "C_K") (pintype "passive"))
      (node (ref "LED956") (pin "K") (pinfunction "C_K") (pintype "passive"))
      (node (ref "LED957") (pin "K") (pinfunction "C_K") (pintype "passive"))
      (node (ref "LED958") (pin "K") (pinfunction "C_K") (pintype "passive"))
      (node (ref "U$2") (pin "P$8") (pinfunction "P$8_P$8") (pintype "bidirectional"))
    )
    (net (code "92") (name "Net-(LED1047-C)") (class "Default")
      (node (ref "LED1047") (pin "K") (pinfunction "C_K") (pintype "passive"))
      (node (ref "LED959") (pin "K") (pinfunction "C_K") (pintype "passive"))
      (node (ref "LED960") (pin "K") (pinfunction "C_K") (pintype "passive"))
      (node (ref "LED961") (pin "K") (pinfunction "C_K") (pintype "passive"))
      (node (ref "LED962") (pin "K") (pinfunction "C_K") (pintype "passive"))
      (node (ref "LED963") (pin "K") (pinfunction "C_K") (pintype "passive"))
      (node (ref "LED964") (pin "K") (pinfunction "C_K") (pintype "passive"))
      (node (ref "LED965") (pin "K") (pinfunction "C_K") (pintype "passive"))
      (node (ref "LED966") (pin "K") (pinfunction "C_K") (pintype "passive"))
      (node (ref "U$2") (pin "P$7") (pinfunction "P$7_P$7") (pintype "bidirectional"))
    )
    (net (code "93") (name "Net-(LED1048-C)") (class "Default")
      (node (ref "LED1048") (pin "K") (pinfunction "C_K") (pintype "passive"))
      (node (ref "LED967") (pin "K") (pinfunction "C_K") (pintype "passive"))
      (node (ref "LED968") (pin "K") (pinfunction "C_K") (pintype "passive"))
      (node (ref "LED969") (pin "K") (pinfunction "C_K") (pintype "passive"))
      (node (ref "LED970") (pin "K") (pinfunction "C_K") (pintype "passive"))
      (node (ref "LED971") (pin "K") (pinfunction "C_K") (pintype "passive"))
      (node (ref "LED972") (pin "K") (pinfunction "C_K") (pintype "passive"))
      (node (ref "LED973") (pin "K") (pinfunction "C_K") (pintype "passive"))
      (node (ref "LED974") (pin "K") (pinfunction "C_K") (pintype "passive"))
      (node (ref "U$2") (pin "P$6") (pinfunction "P$6_P$6") (pintype "bidirectional"))
    )
    (net (code "94") (name "Net-(LED1049-C)") (class "Default")
      (node (ref "LED1049") (pin "K") (pinfunction "C_K") (pintype "passive"))
      (node (ref "LED975") (pin "K") (pinfunction "C_K") (pintype "passive"))
      (node (ref "LED976") (pin "K") (pinfunction "C_K") (pintype "passive"))
      (node (ref "LED977") (pin "K") (pinfunction "C_K") (pintype "passive"))
      (node (ref "LED978") (pin "K") (pinfunction "C_K") (pintype "passive"))
      (node (ref "LED979") (pin "K") (pinfunction "C_K") (pintype "passive"))
      (node (ref "LED980") (pin "K") (pinfunction "C_K") (pintype "passive"))
      (node (ref "LED981") (pin "K") (pinfunction "C_K") (pintype "passive"))
      (node (ref "LED982") (pin "K") (pinfunction "C_K") (pintype "passive"))
      (node (ref "U$2") (pin "P$5") (pinfunction "P$5_P$5") (pintype "bidirectional"))
    )
    (net (code "95") (name "Net-(LED1050-C)") (class "Default")
      (node (ref "LED1050") (pin "K") (pinfunction "C_K") (pintype "passive"))
      (node (ref "LED983") (pin "K") (pinfunction "C_K") (pintype "passive"))
      (node (ref "LED984") (pin "K") (pinfunction "C_K") (pintype "passive"))
      (node (ref "LED985") (pin "K") (pinfunction "C_K") (pintype "passive"))
      (node (ref "LED986") (pin "K") (pinfunction "C_K") (pintype "passive"))
      (node (ref "LED987") (pin "K") (pinfunction "C_K") (pintype "passive"))
      (node (ref "LED988") (pin "K") (pinfunction "C_K") (pintype "passive"))
      (node (ref "LED989") (pin "K") (pinfunction "C_K") (pintype "passive"))
      (node (ref "LED990") (pin "K") (pinfunction "C_K") (pintype "passive"))
      (node (ref "U$2") (pin "P$4") (pinfunction "P$4_P$4") (pintype "bidirectional"))
    )
    (net (code "96") (name "Net-(LED1051-C)") (class "Default")
      (node (ref "LED1051") (pin "K") (pinfunction "C_K") (pintype "passive"))
      (node (ref "LED991") (pin "K") (pinfunction "C_K") (pintype "passive"))
      (node (ref "LED992") (pin "K") (pinfunction "C_K") (pintype "passive"))
      (node (ref "LED993") (pin "K") (pinfunction "C_K") (pintype "passive"))
      (node (ref "LED994") (pin "K") (pinfunction "C_K") (pintype "passive"))
      (node (ref "LED995") (pin "K") (pinfunction "C_K") (pintype "passive"))
      (node (ref "LED996") (pin "K") (pinfunction "C_K") (pintype "passive"))
      (node (ref "LED997") (pin "K") (pinfunction "C_K") (pintype "passive"))
      (node (ref "LED998") (pin "K") (pinfunction "C_K") (pintype "passive"))
      (node (ref "U$2") (pin "P$3") (pinfunction "P$3_P$3") (pintype "bidirectional"))
    )
    (net (code "97") (name "unconnected-(U$1-PadP$28)") (class "Default")
      (node (ref "U$1") (pin "P$28") (pinfunction "P$28_P$28") (pintype "bidirectional"))
    )
  )
)
